# Top.net
KiCad netlist of a schematic drawn in Altium Designer
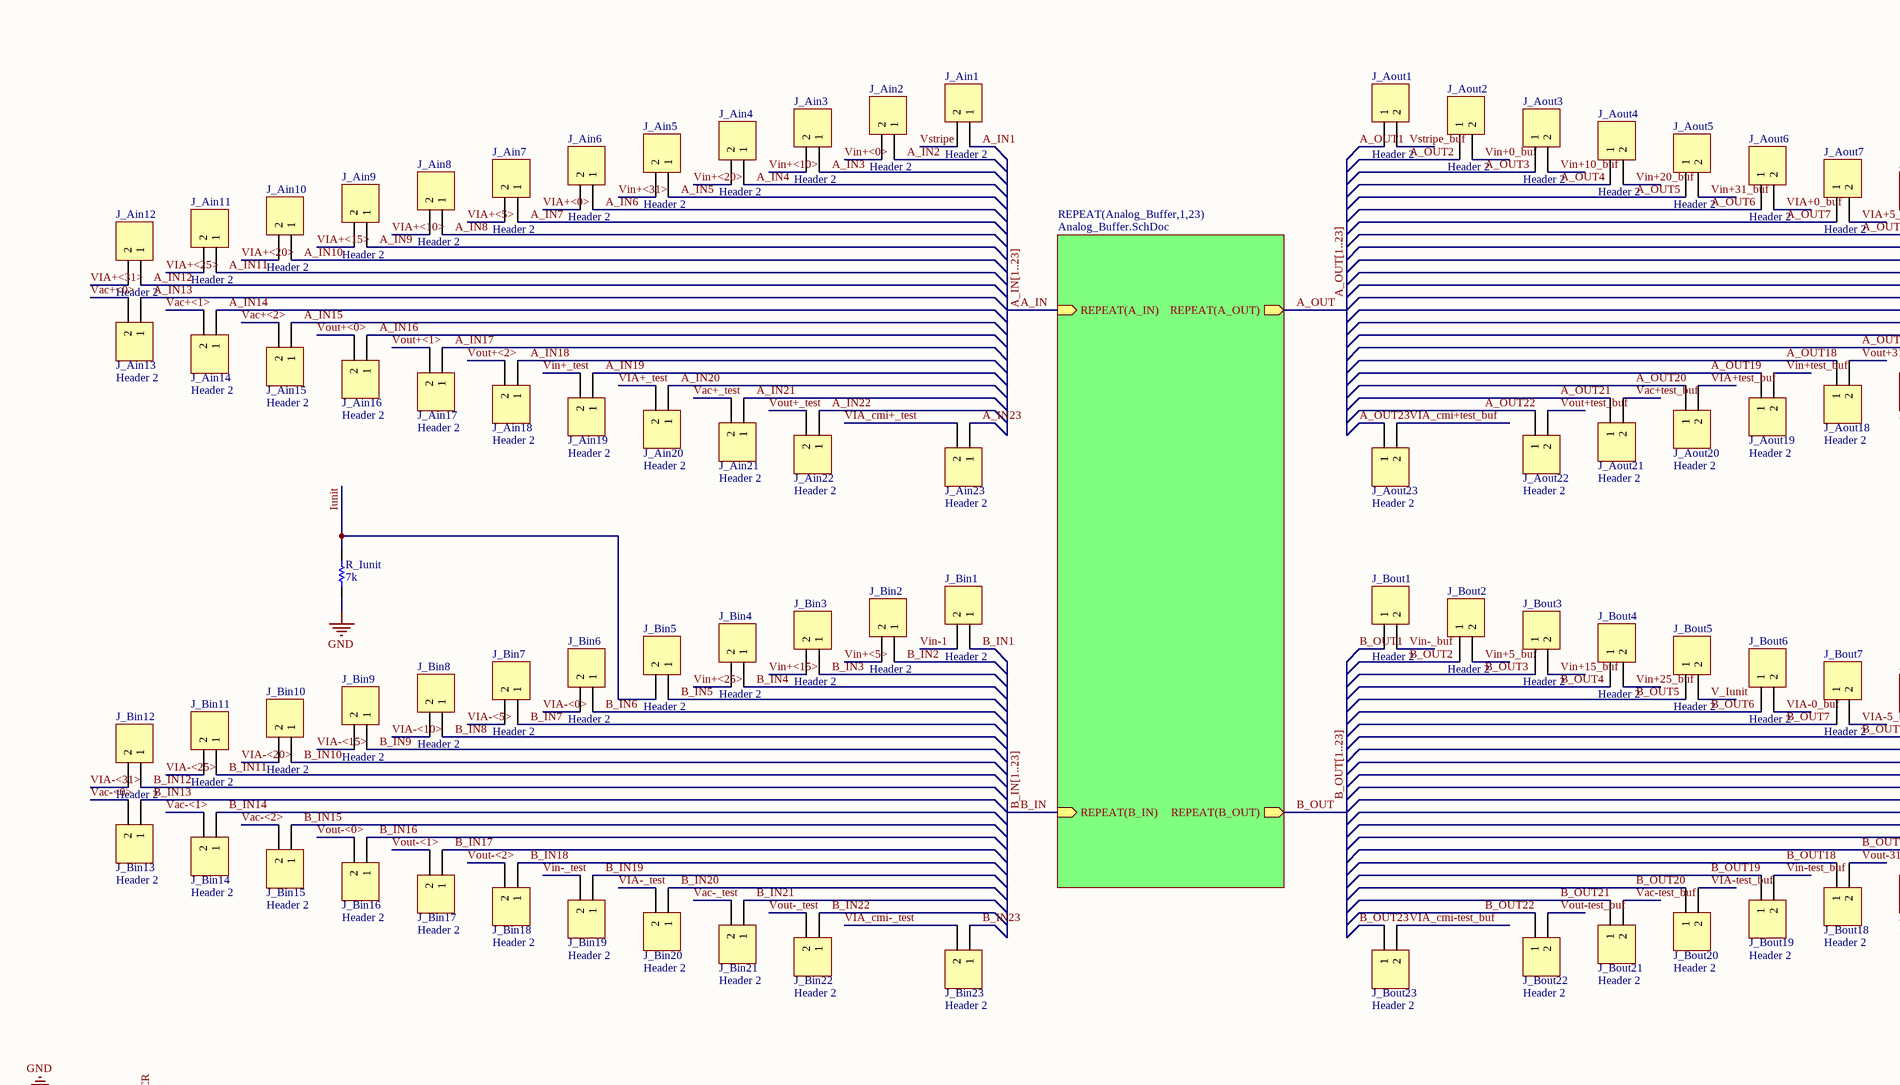
[diagram p0: Top.SchDoc, top left]
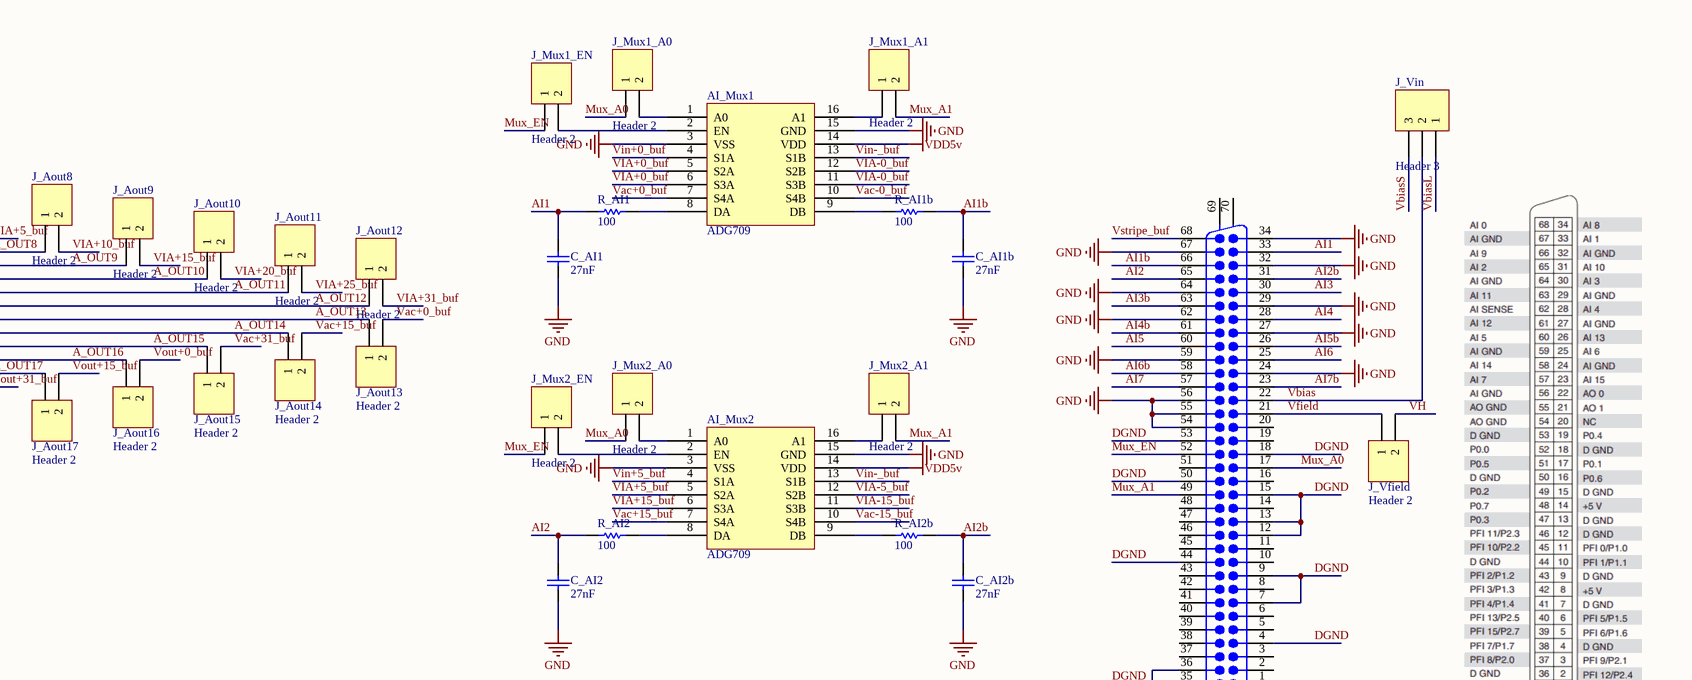
[diagram p1: Top.SchDoc, top right]
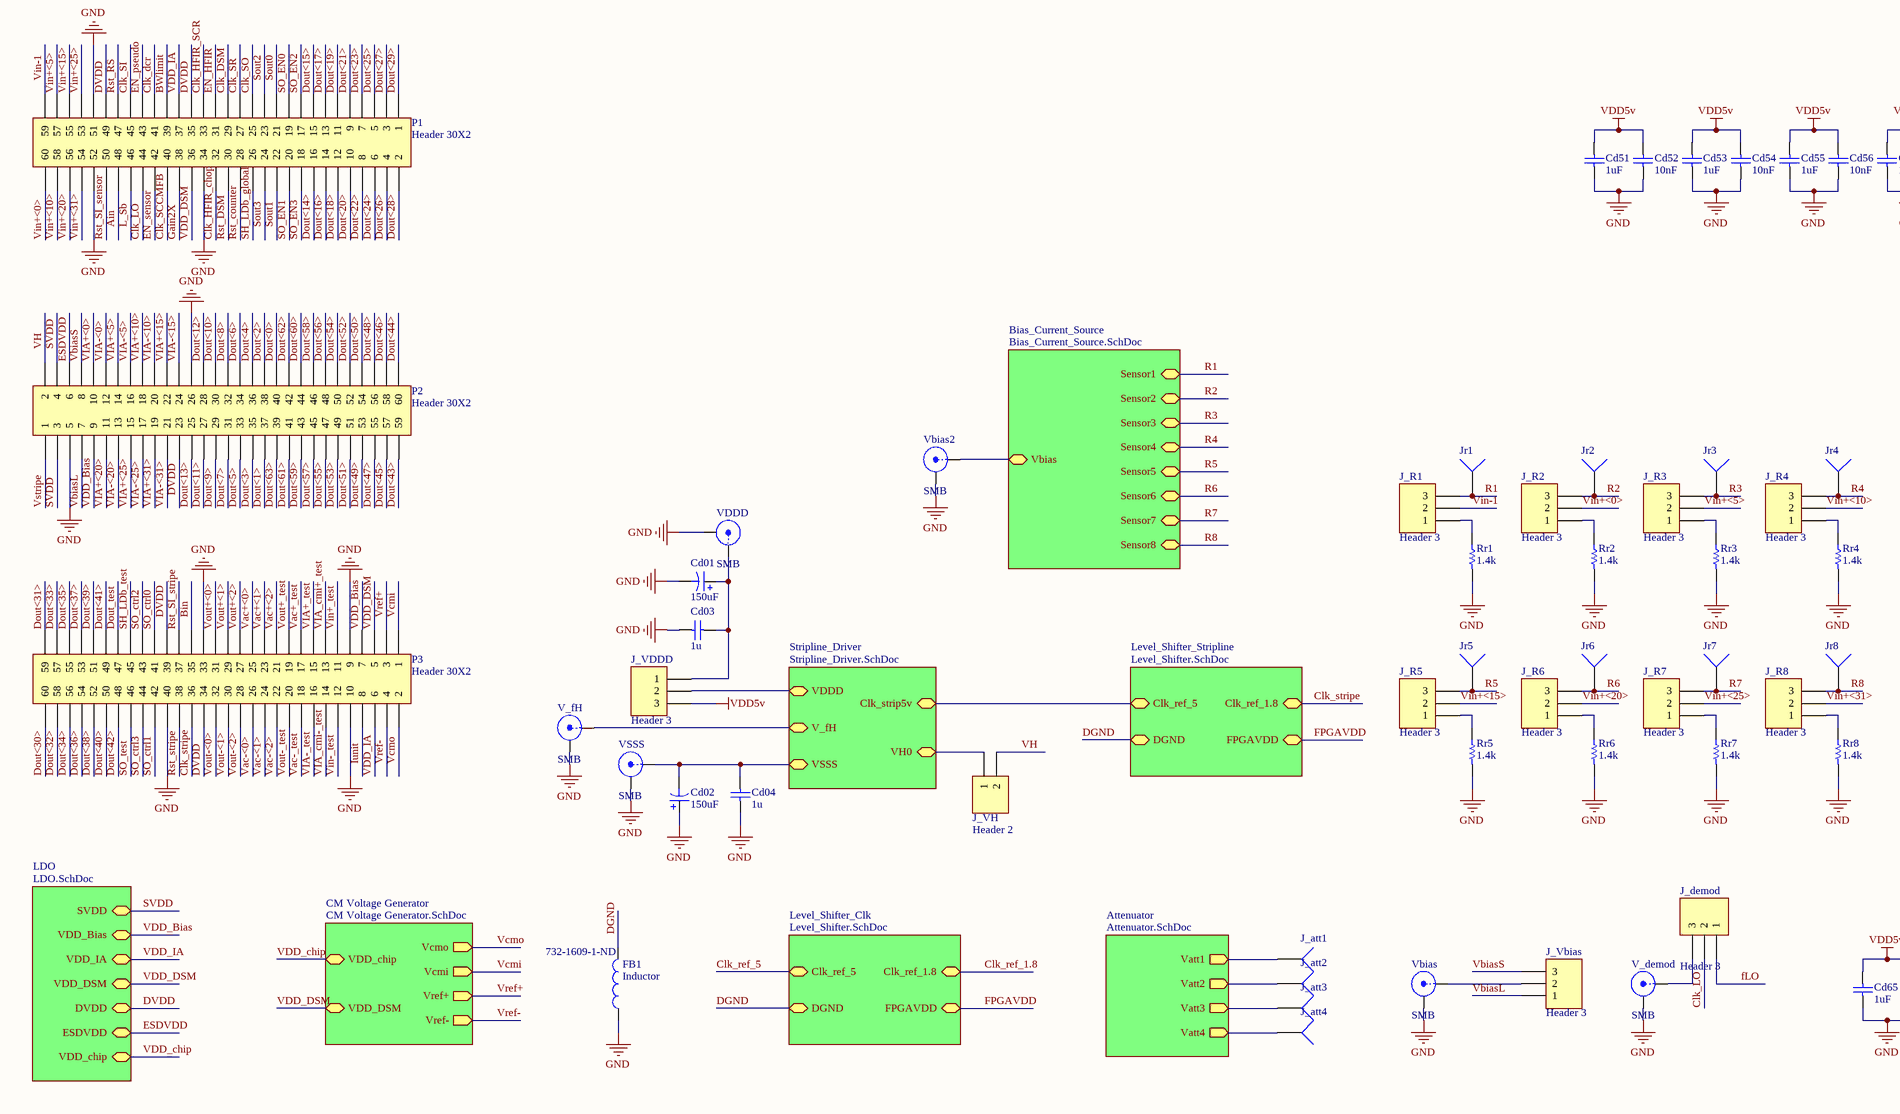
[diagram p2: Top.SchDoc, bottom left]
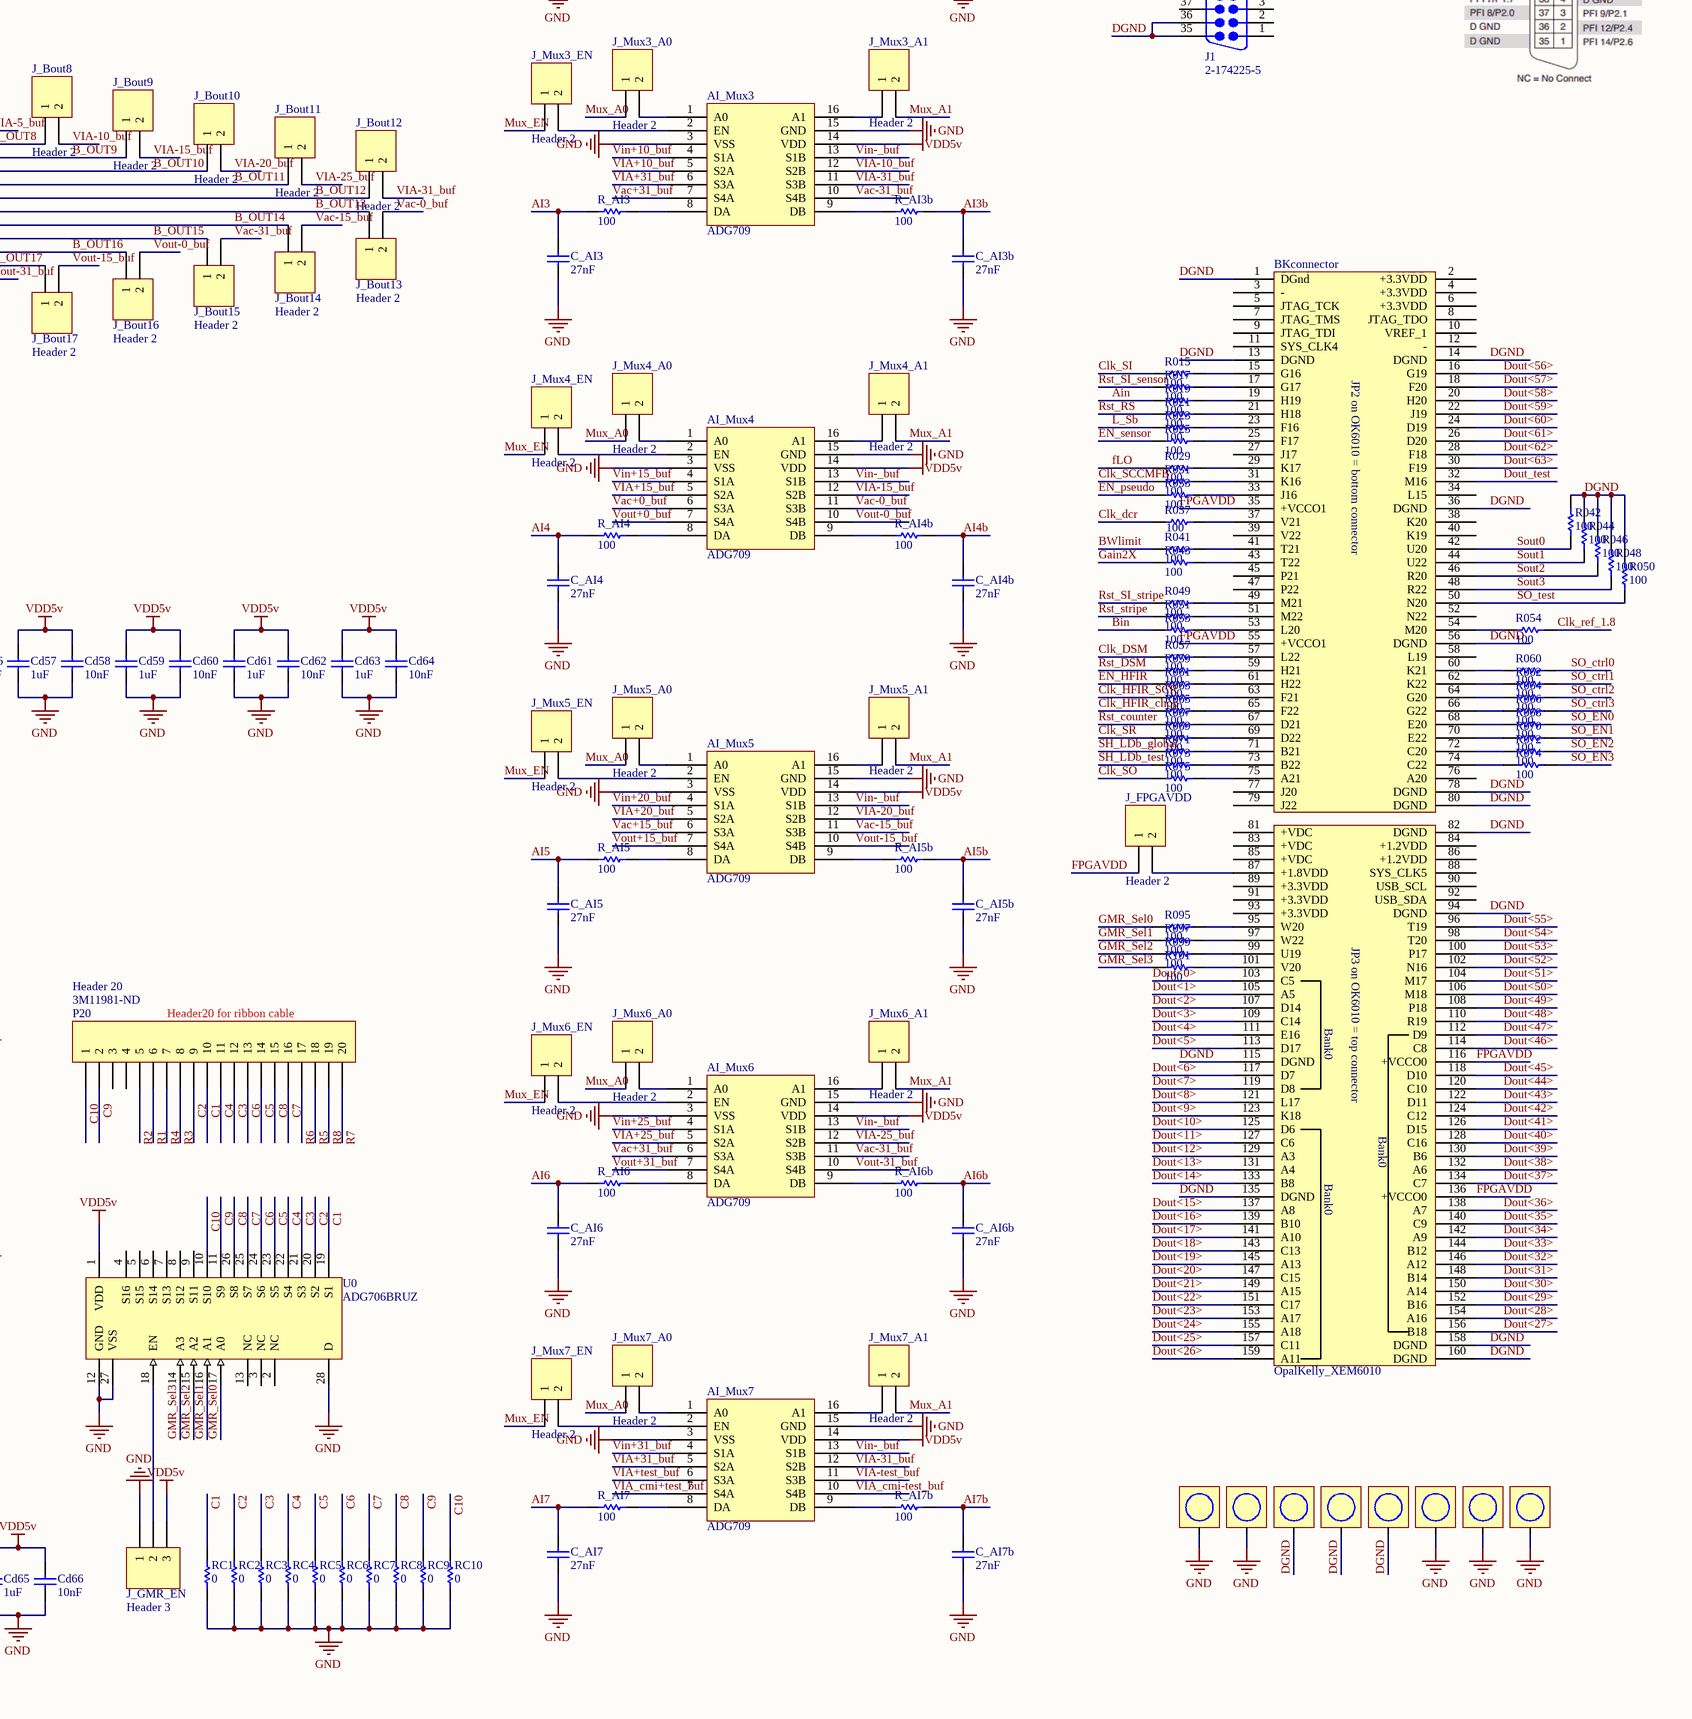
[diagram p3: Top.SchDoc, bottom right]

(export (version "E")
  (design (tool "Eeschema 10.0.6"))
  (components
    (comp (ref "AI_Mux1") (value "ADG709") (footprint "RU-16") (libsource (lib "custom") (part "ADG709")))
    (comp (ref "AI_Mux2") (value "ADG709") (footprint "RU-16") (libsource (lib "custom") (part "ADG709")))
    (comp (ref "AI_Mux3") (value "ADG709") (footprint "RU-16") (libsource (lib "custom") (part "ADG709")))
    (comp (ref "AI_Mux4") (value "ADG709") (footprint "RU-16") (libsource (lib "custom") (part "ADG709")))
    (comp (ref "AI_Mux5") (value "ADG709") (footprint "RU-16") (libsource (lib "custom") (part "ADG709")))
    (comp (ref "AI_Mux6") (value "ADG709") (footprint "RU-16") (libsource (lib "custom") (part "ADG709")))
    (comp (ref "AI_Mux7") (value "ADG709") (footprint "RU-16") (libsource (lib "custom") (part "ADG709")))
    (comp (ref "BKconnector")
      (value "OpalKelly_XEM6010")
      (footprint "OpalKelly_XEM6010")
      (libsource (lib "IBL Parts") (part "OpalKelly_XEM6010"))
    )
    (comp (ref "Cd01")
      (value "150uF")
      (footprint "C1210_M")
      (description "Polarized Capacitor (Radial)")
      (fields (field (name "Comment") "Cap Pol1") (field (name "PUBLISHER") "Altium Limited"))
      (libsource (lib "Miscellaneous Devices") (part "Cap Pol1"))
    )
    (comp (ref "Cd02")
      (value "150uF")
      (footprint "C1210_M")
      (description "Polarized Capacitor (Radial)")
      (fields (field (name "Comment") "Cap Pol1") (field (name "PUBLISHER") "Altium Limited"))
      (libsource (lib "Miscellaneous Devices") (part "Cap Pol1"))
    )
    (comp (ref "Cd03")
      (value "1u")
      (footprint "6-0805_M")
      (description "Capacitor")
      (fields (field (name "Comment") "Cap") (field (name "PUBLISHER") "Altium Limited"))
      (libsource (lib "Miscellaneous Devices") (part "Cap"))
    )
    (comp (ref "Cd04")
      (value "1u")
      (footprint "6-0805_M")
      (description "Capacitor")
      (fields (field (name "Comment") "Cap") (field (name "PUBLISHER") "Altium Limited"))
      (libsource (lib "Miscellaneous Devices") (part "Cap"))
    )
    (comp (ref "Cd51")
      (value "1uF")
      (footprint "1608[0603]")
      (description "Capacitor")
      (fields (field (name "Comment") "Cap") (field (name "PUBLISHER") "Altium Limited"))
      (libsource (lib "Miscellaneous Devices") (part "Cap"))
    )
    (comp (ref "Cd52")
      (value "10nF")
      (footprint "1608[0603]")
      (description "Capacitor")
      (fields (field (name "Comment") "Cap") (field (name "PUBLISHER") "Altium Limited"))
      (libsource (lib "Miscellaneous Devices") (part "Cap"))
    )
    (comp (ref "Cd53")
      (value "1uF")
      (footprint "1608[0603]")
      (description "Capacitor")
      (fields (field (name "Comment") "Cap") (field (name "PUBLISHER") "Altium Limited"))
      (libsource (lib "Miscellaneous Devices") (part "Cap"))
    )
    (comp (ref "Cd54")
      (value "10nF")
      (footprint "1608[0603]")
      (description "Capacitor")
      (fields (field (name "Comment") "Cap") (field (name "PUBLISHER") "Altium Limited"))
      (libsource (lib "Miscellaneous Devices") (part "Cap"))
    )
    (comp (ref "Cd55")
      (value "1uF")
      (footprint "1608[0603]")
      (description "Capacitor")
      (fields (field (name "Comment") "Cap") (field (name "PUBLISHER") "Altium Limited"))
      (libsource (lib "Miscellaneous Devices") (part "Cap"))
    )
    (comp (ref "Cd56")
      (value "10nF")
      (footprint "1608[0603]")
      (description "Capacitor")
      (fields (field (name "Comment") "Cap") (field (name "PUBLISHER") "Altium Limited"))
      (libsource (lib "Miscellaneous Devices") (part "Cap"))
    )
    (comp (ref "Cd57")
      (value "1uF")
      (footprint "1608[0603]")
      (description "Capacitor")
      (fields (field (name "Comment") "Cap") (field (name "PUBLISHER") "Altium Limited"))
      (libsource (lib "Miscellaneous Devices") (part "Cap"))
    )
    (comp (ref "Cd58")
      (value "10nF")
      (footprint "1608[0603]")
      (description "Capacitor")
      (fields (field (name "Comment") "Cap") (field (name "PUBLISHER") "Altium Limited"))
      (libsource (lib "Miscellaneous Devices") (part "Cap"))
    )
    (comp (ref "Cd59")
      (value "1uF")
      (footprint "1608[0603]")
      (description "Capacitor")
      (fields (field (name "Comment") "Cap") (field (name "PUBLISHER") "Altium Limited"))
      (libsource (lib "Miscellaneous Devices") (part "Cap"))
    )
    (comp (ref "Cd60")
      (value "10nF")
      (footprint "1608[0603]")
      (description "Capacitor")
      (fields (field (name "Comment") "Cap") (field (name "PUBLISHER") "Altium Limited"))
      (libsource (lib "Miscellaneous Devices") (part "Cap"))
    )
    (comp (ref "Cd61")
      (value "1uF")
      (footprint "1608[0603]")
      (description "Capacitor")
      (fields (field (name "Comment") "Cap") (field (name "PUBLISHER") "Altium Limited"))
      (libsource (lib "Miscellaneous Devices") (part "Cap"))
    )
    (comp (ref "Cd62")
      (value "10nF")
      (footprint "1608[0603]")
      (description "Capacitor")
      (fields (field (name "Comment") "Cap") (field (name "PUBLISHER") "Altium Limited"))
      (libsource (lib "Miscellaneous Devices") (part "Cap"))
    )
    (comp (ref "Cd63")
      (value "1uF")
      (footprint "1608[0603]")
      (description "Capacitor")
      (fields (field (name "Comment") "Cap") (field (name "PUBLISHER") "Altium Limited"))
      (libsource (lib "Miscellaneous Devices") (part "Cap"))
    )
    (comp (ref "Cd64")
      (value "10nF")
      (footprint "1608[0603]")
      (description "Capacitor")
      (fields (field (name "Comment") "Cap") (field (name "PUBLISHER") "Altium Limited"))
      (libsource (lib "Miscellaneous Devices") (part "Cap"))
    )
    (comp (ref "Cd65")
      (value "1uF")
      (footprint "1608[0603]")
      (description "Capacitor")
      (fields (field (name "Comment") "Cap") (field (name "PUBLISHER") "Altium Limited"))
      (libsource (lib "Miscellaneous Devices") (part "Cap"))
    )
    (comp (ref "Cd66")
      (value "10nF")
      (footprint "1608[0603]")
      (description "Capacitor")
      (fields (field (name "Comment") "Cap") (field (name "PUBLISHER") "Altium Limited"))
      (libsource (lib "Miscellaneous Devices") (part "Cap"))
    )
    (comp (ref "C_AI1")
      (value "27nF")
      (footprint "1608[0603]")
      (description "Capacitor")
      (fields (field (name "Comment") "Cap") (field (name "PUBLISHER") "Altium Limited"))
      (libsource (lib "Miscellaneous Devices") (part "Cap"))
    )
    (comp (ref "C_AI1b")
      (value "27nF")
      (footprint "1608[0603]")
      (description "Capacitor")
      (fields (field (name "Comment") "Cap") (field (name "PUBLISHER") "Altium Limited"))
      (libsource (lib "Miscellaneous Devices") (part "Cap"))
    )
    (comp (ref "C_AI2")
      (value "27nF")
      (footprint "1608[0603]")
      (description "Capacitor")
      (fields (field (name "Comment") "Cap") (field (name "PUBLISHER") "Altium Limited"))
      (libsource (lib "Miscellaneous Devices") (part "Cap"))
    )
    (comp (ref "C_AI2b")
      (value "27nF")
      (footprint "1608[0603]")
      (description "Capacitor")
      (fields (field (name "Comment") "Cap") (field (name "PUBLISHER") "Altium Limited"))
      (libsource (lib "Miscellaneous Devices") (part "Cap"))
    )
    (comp (ref "C_AI3")
      (value "27nF")
      (footprint "1608[0603]")
      (description "Capacitor")
      (fields (field (name "Comment") "Cap") (field (name "PUBLISHER") "Altium Limited"))
      (libsource (lib "Miscellaneous Devices") (part "Cap"))
    )
    (comp (ref "C_AI3b")
      (value "27nF")
      (footprint "1608[0603]")
      (description "Capacitor")
      (fields (field (name "Comment") "Cap") (field (name "PUBLISHER") "Altium Limited"))
      (libsource (lib "Miscellaneous Devices") (part "Cap"))
    )
    (comp (ref "C_AI4")
      (value "27nF")
      (footprint "1608[0603]")
      (description "Capacitor")
      (fields (field (name "Comment") "Cap") (field (name "PUBLISHER") "Altium Limited"))
      (libsource (lib "Miscellaneous Devices") (part "Cap"))
    )
    (comp (ref "C_AI4b")
      (value "27nF")
      (footprint "1608[0603]")
      (description "Capacitor")
      (fields (field (name "Comment") "Cap") (field (name "PUBLISHER") "Altium Limited"))
      (libsource (lib "Miscellaneous Devices") (part "Cap"))
    )
    (comp (ref "C_AI5")
      (value "27nF")
      (footprint "1608[0603]")
      (description "Capacitor")
      (fields (field (name "Comment") "Cap") (field (name "PUBLISHER") "Altium Limited"))
      (libsource (lib "Miscellaneous Devices") (part "Cap"))
    )
    (comp (ref "C_AI5b")
      (value "27nF")
      (footprint "1608[0603]")
      (description "Capacitor")
      (fields (field (name "Comment") "Cap") (field (name "PUBLISHER") "Altium Limited"))
      (libsource (lib "Miscellaneous Devices") (part "Cap"))
    )
    (comp (ref "C_AI6")
      (value "27nF")
      (footprint "1608[0603]")
      (description "Capacitor")
      (fields (field (name "Comment") "Cap") (field (name "PUBLISHER") "Altium Limited"))
      (libsource (lib "Miscellaneous Devices") (part "Cap"))
    )
    (comp (ref "C_AI6b")
      (value "27nF")
      (footprint "1608[0603]")
      (description "Capacitor")
      (fields (field (name "Comment") "Cap") (field (name "PUBLISHER") "Altium Limited"))
      (libsource (lib "Miscellaneous Devices") (part "Cap"))
    )
    (comp (ref "C_AI7")
      (value "27nF")
      (footprint "1608[0603]")
      (description "Capacitor")
      (fields (field (name "Comment") "Cap") (field (name "PUBLISHER") "Altium Limited"))
      (libsource (lib "Miscellaneous Devices") (part "Cap"))
    )
    (comp (ref "C_AI7b")
      (value "27nF")
      (footprint "1608[0603]")
      (description "Capacitor")
      (fields (field (name "Comment") "Cap") (field (name "PUBLISHER") "Altium Limited"))
      (libsource (lib "Miscellaneous Devices") (part "Cap"))
    )
    (comp (ref "FB1")
      (value "Inductor")
      (footprint "C0805")
      (fields
        (field (name "SUPPLIER PART NUMBER 1") "732-1609-1-ND")
        (field (name "MANUFACTURER") "Wurth Electronics Inc")
        (field (name "MANUFACTURER PART NUMBER") "742792093")
        (field (name "PUBLISHER") "Altium Limited")
      )
      (libsource (lib "Miscellaneous Devices") (part "Inductor"))
    )
    (comp (ref "H1")
      (value "Mounting Hole")
      (footprint "MTHole")
      (libsource (lib "IBL Parts") (part "MTHole"))
    )
    (comp (ref "H2")
      (value "Mounting Hole")
      (footprint "MTHole")
      (libsource (lib "IBL Parts") (part "MTHole"))
    )
    (comp (ref "H3")
      (value "Mounting Hole")
      (footprint "MTHole")
      (libsource (lib "IBL Parts") (part "MTHole"))
    )
    (comp (ref "H4")
      (value "Mounting Hole")
      (footprint "MTHole")
      (libsource (lib "IBL Parts") (part "MTHole"))
    )
    (comp (ref "H5")
      (value "Mounting Hole")
      (footprint "MTHole")
      (libsource (lib "IBL Parts") (part "MTHole"))
    )
    (comp (ref "H6")
      (value "Mounting Hole")
      (footprint "MTHole")
      (libsource (lib "IBL Parts") (part "MTHole"))
    )
    (comp (ref "H7")
      (value "Mounting Hole")
      (footprint "MTHole")
      (libsource (lib "IBL Parts") (part "MTHole"))
    )
    (comp (ref "H8")
      (value "Mounting Hole")
      (footprint "MTHole")
      (libsource (lib "IBL Parts") (part "MTHole"))
    )
    (comp (ref "J1")
      (value "2-174225-5")
      (footprint "2-174225-5")
      (description "Cap Header, Right Angle /M2.5 AMPLIMITE 050 Series II")
      (fields (field (name "PUBLISHER") "Altium Limited"))
      (libsource (lib "AMP D Subminiature 050 Series") (part "2-174225-5"))
    )
    (comp (ref "Jr1")
      (value "Socket")
      (footprint "PIN1")
      (fields (field (name "PUBLISHER") "Altium Limited"))
      (libsource (lib "Miscellaneous Connectors") (part "Socket"))
    )
    (comp (ref "Jr2")
      (value "Socket")
      (footprint "PIN1")
      (fields (field (name "PUBLISHER") "Altium Limited"))
      (libsource (lib "Miscellaneous Connectors") (part "Socket"))
    )
    (comp (ref "Jr3")
      (value "Socket")
      (footprint "PIN1")
      (fields (field (name "PUBLISHER") "Altium Limited"))
      (libsource (lib "Miscellaneous Connectors") (part "Socket"))
    )
    (comp (ref "Jr4")
      (value "Socket")
      (footprint "PIN1")
      (fields (field (name "PUBLISHER") "Altium Limited"))
      (libsource (lib "Miscellaneous Connectors") (part "Socket"))
    )
    (comp (ref "Jr5")
      (value "Socket")
      (footprint "PIN1")
      (fields (field (name "PUBLISHER") "Altium Limited"))
      (libsource (lib "Miscellaneous Connectors") (part "Socket"))
    )
    (comp (ref "Jr6")
      (value "Socket")
      (footprint "PIN1")
      (fields (field (name "PUBLISHER") "Altium Limited"))
      (libsource (lib "Miscellaneous Connectors") (part "Socket"))
    )
    (comp (ref "Jr7")
      (value "Socket")
      (footprint "PIN1")
      (fields (field (name "PUBLISHER") "Altium Limited"))
      (libsource (lib "Miscellaneous Connectors") (part "Socket"))
    )
    (comp (ref "Jr8")
      (value "Socket")
      (footprint "PIN1")
      (fields (field (name "PUBLISHER") "Altium Limited"))
      (libsource (lib "Miscellaneous Connectors") (part "Socket"))
    )
    (comp (ref "J_Ain1")
      (value "Header 2")
      (footprint "HDR1X2")
      (description "Header, 2-Pin")
      (fields (field (name "PUBLISHER") "Altium Limited"))
      (libsource (lib "") (part "Header 2_2"))
    )
    (comp (ref "J_Ain2")
      (value "Header 2")
      (footprint "HDR1X2")
      (description "Header, 2-Pin")
      (fields (field (name "PUBLISHER") "Altium Limited"))
      (libsource (lib "") (part "Header 2_2"))
    )
    (comp (ref "J_Ain3")
      (value "Header 2")
      (footprint "HDR1X2")
      (description "Header, 2-Pin")
      (fields (field (name "PUBLISHER") "Altium Limited"))
      (libsource (lib "") (part "Header 2_2"))
    )
    (comp (ref "J_Ain4")
      (value "Header 2")
      (footprint "HDR1X2")
      (description "Header, 2-Pin")
      (fields (field (name "PUBLISHER") "Altium Limited"))
      (libsource (lib "") (part "Header 2_2"))
    )
    (comp (ref "J_Ain5")
      (value "Header 2")
      (footprint "HDR1X2")
      (description "Header, 2-Pin")
      (fields (field (name "PUBLISHER") "Altium Limited"))
      (libsource (lib "") (part "Header 2_2"))
    )
    (comp (ref "J_Ain6")
      (value "Header 2")
      (footprint "HDR1X2")
      (description "Header, 2-Pin")
      (fields (field (name "PUBLISHER") "Altium Limited"))
      (libsource (lib "") (part "Header 2_2"))
    )
    (comp (ref "J_Ain7")
      (value "Header 2")
      (footprint "HDR1X2")
      (description "Header, 2-Pin")
      (fields (field (name "PUBLISHER") "Altium Limited"))
      (libsource (lib "") (part "Header 2_2"))
    )
    (comp (ref "J_Ain8")
      (value "Header 2")
      (footprint "HDR1X2")
      (description "Header, 2-Pin")
      (fields (field (name "PUBLISHER") "Altium Limited"))
      (libsource (lib "") (part "Header 2_2"))
    )
    (comp (ref "J_Ain9")
      (value "Header 2")
      (footprint "HDR1X2")
      (description "Header, 2-Pin")
      (fields (field (name "PUBLISHER") "Altium Limited"))
      (libsource (lib "") (part "Header 2_2"))
    )
    (comp (ref "J_Ain10")
      (value "Header 2")
      (footprint "HDR1X2")
      (description "Header, 2-Pin")
      (fields (field (name "PUBLISHER") "Altium Limited"))
      (libsource (lib "") (part "Header 2_2"))
    )
    (comp (ref "J_Ain11")
      (value "Header 2")
      (footprint "HDR1X2")
      (description "Header, 2-Pin")
      (fields (field (name "PUBLISHER") "Altium Limited"))
      (libsource (lib "") (part "Header 2_2"))
    )
    (comp (ref "J_Ain12")
      (value "Header 2")
      (footprint "HDR1X2")
      (description "Header, 2-Pin")
      (fields (field (name "PUBLISHER") "Altium Limited"))
      (libsource (lib "") (part "Header 2_2"))
    )
    (comp (ref "J_Ain13")
      (value "Header 2")
      (footprint "HDR1X2")
      (description "Header, 2-Pin")
      (fields (field (name "PUBLISHER") "Altium Limited"))
      (libsource (lib "") (part "Header 2_1"))
    )
    (comp (ref "J_Ain14")
      (value "Header 2")
      (footprint "HDR1X2")
      (description "Header, 2-Pin")
      (fields (field (name "PUBLISHER") "Altium Limited"))
      (libsource (lib "") (part "Header 2_1"))
    )
    (comp (ref "J_Ain15")
      (value "Header 2")
      (footprint "HDR1X2")
      (description "Header, 2-Pin")
      (fields (field (name "PUBLISHER") "Altium Limited"))
      (libsource (lib "") (part "Header 2_1"))
    )
    (comp (ref "J_Ain16")
      (value "Header 2")
      (footprint "HDR1X2")
      (description "Header, 2-Pin")
      (fields (field (name "PUBLISHER") "Altium Limited"))
      (libsource (lib "") (part "Header 2_1"))
    )
    (comp (ref "J_Ain17")
      (value "Header 2")
      (footprint "HDR1X2")
      (description "Header, 2-Pin")
      (fields (field (name "PUBLISHER") "Altium Limited"))
      (libsource (lib "") (part "Header 2_1"))
    )
    (comp (ref "J_Ain18")
      (value "Header 2")
      (footprint "HDR1X2")
      (description "Header, 2-Pin")
      (fields (field (name "PUBLISHER") "Altium Limited"))
      (libsource (lib "") (part "Header 2_1"))
    )
    (comp (ref "J_Ain19")
      (value "Header 2")
      (footprint "HDR1X2")
      (description "Header, 2-Pin")
      (fields (field (name "PUBLISHER") "Altium Limited"))
      (libsource (lib "") (part "Header 2_1"))
    )
    (comp (ref "J_Ain20")
      (value "Header 2")
      (footprint "HDR1X2")
      (description "Header, 2-Pin")
      (fields (field (name "PUBLISHER") "Altium Limited"))
      (libsource (lib "") (part "Header 2_1"))
    )
    (comp (ref "J_Ain21")
      (value "Header 2")
      (footprint "HDR1X2")
      (description "Header, 2-Pin")
      (fields (field (name "PUBLISHER") "Altium Limited"))
      (libsource (lib "") (part "Header 2_1"))
    )
    (comp (ref "J_Ain22")
      (value "Header 2")
      (footprint "HDR1X2")
      (description "Header, 2-Pin")
      (fields (field (name "PUBLISHER") "Altium Limited"))
      (libsource (lib "") (part "Header 2_1"))
    )
    (comp (ref "J_Ain23")
      (value "Header 2")
      (footprint "HDR1X2")
      (description "Header, 2-Pin")
      (fields (field (name "PUBLISHER") "Altium Limited"))
      (libsource (lib "") (part "Header 2_1"))
    )
    (comp (ref "J_Aout1")
      (value "Header 2")
      (footprint "HDR1X2")
      (description "Header, 2-Pin")
      (fields (field (name "PUBLISHER") "Altium Limited"))
      (libsource (lib "Miscellaneous Connectors") (part "Header 2"))
    )
    (comp (ref "J_Aout2")
      (value "Header 2")
      (footprint "HDR1X2")
      (description "Header, 2-Pin")
      (fields (field (name "PUBLISHER") "Altium Limited"))
      (libsource (lib "Miscellaneous Connectors") (part "Header 2"))
    )
    (comp (ref "J_Aout3")
      (value "Header 2")
      (footprint "HDR1X2")
      (description "Header, 2-Pin")
      (fields (field (name "PUBLISHER") "Altium Limited"))
      (libsource (lib "Miscellaneous Connectors") (part "Header 2"))
    )
    (comp (ref "J_Aout4")
      (value "Header 2")
      (footprint "HDR1X2")
      (description "Header, 2-Pin")
      (fields (field (name "PUBLISHER") "Altium Limited"))
      (libsource (lib "Miscellaneous Connectors") (part "Header 2"))
    )
    (comp (ref "J_Aout5")
      (value "Header 2")
      (footprint "HDR1X2")
      (description "Header, 2-Pin")
      (fields (field (name "PUBLISHER") "Altium Limited"))
      (libsource (lib "Miscellaneous Connectors") (part "Header 2"))
    )
    (comp (ref "J_Aout6")
      (value "Header 2")
      (footprint "HDR1X2")
      (description "Header, 2-Pin")
      (fields (field (name "PUBLISHER") "Altium Limited"))
      (libsource (lib "Miscellaneous Connectors") (part "Header 2"))
    )
    (comp (ref "J_Aout7")
      (value "Header 2")
      (footprint "HDR1X2")
      (description "Header, 2-Pin")
      (fields (field (name "PUBLISHER") "Altium Limited"))
      (libsource (lib "Miscellaneous Connectors") (part "Header 2"))
    )
    (comp (ref "J_Aout8")
      (value "Header 2")
      (footprint "HDR1X2")
      (description "Header, 2-Pin")
      (fields (field (name "PUBLISHER") "Altium Limited"))
      (libsource (lib "Miscellaneous Connectors") (part "Header 2"))
    )
    (comp (ref "J_Aout9")
      (value "Header 2")
      (footprint "HDR1X2")
      (description "Header, 2-Pin")
      (fields (field (name "PUBLISHER") "Altium Limited"))
      (libsource (lib "Miscellaneous Connectors") (part "Header 2"))
    )
    (comp (ref "J_Aout10")
      (value "Header 2")
      (footprint "HDR1X2")
      (description "Header, 2-Pin")
      (fields (field (name "PUBLISHER") "Altium Limited"))
      (libsource (lib "Miscellaneous Connectors") (part "Header 2"))
    )
    (comp (ref "J_Aout11")
      (value "Header 2")
      (footprint "HDR1X2")
      (description "Header, 2-Pin")
      (fields (field (name "PUBLISHER") "Altium Limited"))
      (libsource (lib "Miscellaneous Connectors") (part "Header 2"))
    )
    (comp (ref "J_Aout12")
      (value "Header 2")
      (footprint "HDR1X2")
      (description "Header, 2-Pin")
      (fields (field (name "PUBLISHER") "Altium Limited"))
      (libsource (lib "Miscellaneous Connectors") (part "Header 2"))
    )
    (comp (ref "J_Aout13")
      (value "Header 2")
      (footprint "HDR1X2")
      (description "Header, 2-Pin")
      (fields (field (name "PUBLISHER") "Altium Limited"))
      (libsource (lib "") (part "Header 2_3"))
    )
    (comp (ref "J_Aout14")
      (value "Header 2")
      (footprint "HDR1X2")
      (description "Header, 2-Pin")
      (fields (field (name "PUBLISHER") "Altium Limited"))
      (libsource (lib "") (part "Header 2_3"))
    )
    (comp (ref "J_Aout15")
      (value "Header 2")
      (footprint "HDR1X2")
      (description "Header, 2-Pin")
      (fields (field (name "PUBLISHER") "Altium Limited"))
      (libsource (lib "") (part "Header 2_3"))
    )
    (comp (ref "J_Aout16")
      (value "Header 2")
      (footprint "HDR1X2")
      (description "Header, 2-Pin")
      (fields (field (name "PUBLISHER") "Altium Limited"))
      (libsource (lib "") (part "Header 2_3"))
    )
    (comp (ref "J_Aout17")
      (value "Header 2")
      (footprint "HDR1X2")
      (description "Header, 2-Pin")
      (fields (field (name "PUBLISHER") "Altium Limited"))
      (libsource (lib "") (part "Header 2_3"))
    )
    (comp (ref "J_Aout18")
      (value "Header 2")
      (footprint "HDR1X2")
      (description "Header, 2-Pin")
      (fields (field (name "PUBLISHER") "Altium Limited"))
      (libsource (lib "") (part "Header 2_3"))
    )
    (comp (ref "J_Aout19")
      (value "Header 2")
      (footprint "HDR1X2")
      (description "Header, 2-Pin")
      (fields (field (name "PUBLISHER") "Altium Limited"))
      (libsource (lib "") (part "Header 2_3"))
    )
    (comp (ref "J_Aout20")
      (value "Header 2")
      (footprint "HDR1X2")
      (description "Header, 2-Pin")
      (fields (field (name "PUBLISHER") "Altium Limited"))
      (libsource (lib "") (part "Header 2_3"))
    )
    (comp (ref "J_Aout21")
      (value "Header 2")
      (footprint "HDR1X2")
      (description "Header, 2-Pin")
      (fields (field (name "PUBLISHER") "Altium Limited"))
      (libsource (lib "") (part "Header 2_3"))
    )
    (comp (ref "J_Aout22")
      (value "Header 2")
      (footprint "HDR1X2")
      (description "Header, 2-Pin")
      (fields (field (name "PUBLISHER") "Altium Limited"))
      (libsource (lib "") (part "Header 2_3"))
    )
    (comp (ref "J_Aout23")
      (value "Header 2")
      (footprint "HDR1X2")
      (description "Header, 2-Pin")
      (fields (field (name "PUBLISHER") "Altium Limited"))
      (libsource (lib "") (part "Header 2_3"))
    )
    (comp (ref "J_att1")
      (value "Socket")
      (footprint "PIN1")
      (fields (field (name "PUBLISHER") "Altium Limited"))
      (libsource (lib "Miscellaneous Connectors") (part "Socket"))
    )
    (comp (ref "J_att2")
      (value "Socket")
      (footprint "PIN1")
      (fields (field (name "PUBLISHER") "Altium Limited"))
      (libsource (lib "Miscellaneous Connectors") (part "Socket"))
    )
    (comp (ref "J_att3")
      (value "Socket")
      (footprint "PIN1")
      (fields (field (name "PUBLISHER") "Altium Limited"))
      (libsource (lib "Miscellaneous Connectors") (part "Socket"))
    )
    (comp (ref "J_att4")
      (value "Socket")
      (footprint "PIN1")
      (fields (field (name "PUBLISHER") "Altium Limited"))
      (libsource (lib "Miscellaneous Connectors") (part "Socket"))
    )
    (comp (ref "J_Bin1")
      (value "Header 2")
      (footprint "HDR1X2")
      (description "Header, 2-Pin")
      (fields (field (name "PUBLISHER") "Altium Limited"))
      (libsource (lib "") (part "Header 2_2"))
    )
    (comp (ref "J_Bin2")
      (value "Header 2")
      (footprint "HDR1X2")
      (description "Header, 2-Pin")
      (fields (field (name "PUBLISHER") "Altium Limited"))
      (libsource (lib "") (part "Header 2_2"))
    )
    (comp (ref "J_Bin3")
      (value "Header 2")
      (footprint "HDR1X2")
      (description "Header, 2-Pin")
      (fields (field (name "PUBLISHER") "Altium Limited"))
      (libsource (lib "") (part "Header 2_2"))
    )
    (comp (ref "J_Bin4")
      (value "Header 2")
      (footprint "HDR1X2")
      (description "Header, 2-Pin")
      (fields (field (name "PUBLISHER") "Altium Limited"))
      (libsource (lib "") (part "Header 2_2"))
    )
    (comp (ref "J_Bin5")
      (value "Header 2")
      (footprint "HDR1X2")
      (description "Header, 2-Pin")
      (fields (field (name "PUBLISHER") "Altium Limited"))
      (libsource (lib "") (part "Header 2_2"))
    )
    (comp (ref "J_Bin6")
      (value "Header 2")
      (footprint "HDR1X2")
      (description "Header, 2-Pin")
      (fields (field (name "PUBLISHER") "Altium Limited"))
      (libsource (lib "") (part "Header 2_2"))
    )
    (comp (ref "J_Bin7")
      (value "Header 2")
      (footprint "HDR1X2")
      (description "Header, 2-Pin")
      (fields (field (name "PUBLISHER") "Altium Limited"))
      (libsource (lib "") (part "Header 2_2"))
    )
    (comp (ref "J_Bin8")
      (value "Header 2")
      (footprint "HDR1X2")
      (description "Header, 2-Pin")
      (fields (field (name "PUBLISHER") "Altium Limited"))
      (libsource (lib "") (part "Header 2_2"))
    )
    (comp (ref "J_Bin9")
      (value "Header 2")
      (footprint "HDR1X2")
      (description "Header, 2-Pin")
      (fields (field (name "PUBLISHER") "Altium Limited"))
      (libsource (lib "") (part "Header 2_2"))
    )
    (comp (ref "J_Bin10")
      (value "Header 2")
      (footprint "HDR1X2")
      (description "Header, 2-Pin")
      (fields (field (name "PUBLISHER") "Altium Limited"))
      (libsource (lib "") (part "Header 2_2"))
    )
    (comp (ref "J_Bin11")
      (value "Header 2")
      (footprint "HDR1X2")
      (description "Header, 2-Pin")
      (fields (field (name "PUBLISHER") "Altium Limited"))
      (libsource (lib "") (part "Header 2_2"))
    )
    (comp (ref "J_Bin12")
      (value "Header 2")
      (footprint "HDR1X2")
      (description "Header, 2-Pin")
      (fields (field (name "PUBLISHER") "Altium Limited"))
      (libsource (lib "") (part "Header 2_2"))
    )
    (comp (ref "J_Bin13")
      (value "Header 2")
      (footprint "HDR1X2")
      (description "Header, 2-Pin")
      (fields (field (name "PUBLISHER") "Altium Limited"))
      (libsource (lib "") (part "Header 2_1"))
    )
    (comp (ref "J_Bin14")
      (value "Header 2")
      (footprint "HDR1X2")
      (description "Header, 2-Pin")
      (fields (field (name "PUBLISHER") "Altium Limited"))
      (libsource (lib "") (part "Header 2_1"))
    )
    (comp (ref "J_Bin15")
      (value "Header 2")
      (footprint "HDR1X2")
      (description "Header, 2-Pin")
      (fields (field (name "PUBLISHER") "Altium Limited"))
      (libsource (lib "") (part "Header 2_1"))
    )
    (comp (ref "J_Bin16")
      (value "Header 2")
      (footprint "HDR1X2")
      (description "Header, 2-Pin")
      (fields (field (name "PUBLISHER") "Altium Limited"))
      (libsource (lib "") (part "Header 2_1"))
    )
    (comp (ref "J_Bin17")
      (value "Header 2")
      (footprint "HDR1X2")
      (description "Header, 2-Pin")
      (fields (field (name "PUBLISHER") "Altium Limited"))
      (libsource (lib "") (part "Header 2_1"))
    )
    (comp (ref "J_Bin18")
      (value "Header 2")
      (footprint "HDR1X2")
      (description "Header, 2-Pin")
      (fields (field (name "PUBLISHER") "Altium Limited"))
      (libsource (lib "") (part "Header 2_1"))
    )
    (comp (ref "J_Bin19")
      (value "Header 2")
      (footprint "HDR1X2")
      (description "Header, 2-Pin")
      (fields (field (name "PUBLISHER") "Altium Limited"))
      (libsource (lib "") (part "Header 2_1"))
    )
    (comp (ref "J_Bin20")
      (value "Header 2")
      (footprint "HDR1X2")
      (description "Header, 2-Pin")
      (fields (field (name "PUBLISHER") "Altium Limited"))
      (libsource (lib "") (part "Header 2_1"))
    )
    (comp (ref "J_Bin21")
      (value "Header 2")
      (footprint "HDR1X2")
      (description "Header, 2-Pin")
      (fields (field (name "PUBLISHER") "Altium Limited"))
      (libsource (lib "") (part "Header 2_1"))
    )
    (comp (ref "J_Bin22")
      (value "Header 2")
      (footprint "HDR1X2")
      (description "Header, 2-Pin")
      (fields (field (name "PUBLISHER") "Altium Limited"))
      (libsource (lib "") (part "Header 2_1"))
    )
    (comp (ref "J_Bin23")
      (value "Header 2")
      (footprint "HDR1X2")
      (description "Header, 2-Pin")
      (fields (field (name "PUBLISHER") "Altium Limited"))
      (libsource (lib "") (part "Header 2_1"))
    )
    (comp (ref "J_Bout1")
      (value "Header 2")
      (footprint "HDR1X2")
      (description "Header, 2-Pin")
      (fields (field (name "PUBLISHER") "Altium Limited"))
      (libsource (lib "Miscellaneous Connectors") (part "Header 2"))
    )
    (comp (ref "J_Bout2")
      (value "Header 2")
      (footprint "HDR1X2")
      (description "Header, 2-Pin")
      (fields (field (name "PUBLISHER") "Altium Limited"))
      (libsource (lib "Miscellaneous Connectors") (part "Header 2"))
    )
    (comp (ref "J_Bout3")
      (value "Header 2")
      (footprint "HDR1X2")
      (description "Header, 2-Pin")
      (fields (field (name "PUBLISHER") "Altium Limited"))
      (libsource (lib "Miscellaneous Connectors") (part "Header 2"))
    )
    (comp (ref "J_Bout4")
      (value "Header 2")
      (footprint "HDR1X2")
      (description "Header, 2-Pin")
      (fields (field (name "PUBLISHER") "Altium Limited"))
      (libsource (lib "Miscellaneous Connectors") (part "Header 2"))
    )
    (comp (ref "J_Bout5")
      (value "Header 2")
      (footprint "HDR1X2")
      (description "Header, 2-Pin")
      (fields (field (name "PUBLISHER") "Altium Limited"))
      (libsource (lib "Miscellaneous Connectors") (part "Header 2"))
    )
    (comp (ref "J_Bout6")
      (value "Header 2")
      (footprint "HDR1X2")
      (description "Header, 2-Pin")
      (fields (field (name "PUBLISHER") "Altium Limited"))
      (libsource (lib "Miscellaneous Connectors") (part "Header 2"))
    )
    (comp (ref "J_Bout7")
      (value "Header 2")
      (footprint "HDR1X2")
      (description "Header, 2-Pin")
      (fields (field (name "PUBLISHER") "Altium Limited"))
      (libsource (lib "Miscellaneous Connectors") (part "Header 2"))
    )
    (comp (ref "J_Bout8")
      (value "Header 2")
      (footprint "HDR1X2")
      (description "Header, 2-Pin")
      (fields (field (name "PUBLISHER") "Altium Limited"))
      (libsource (lib "Miscellaneous Connectors") (part "Header 2"))
    )
    (comp (ref "J_Bout9")
      (value "Header 2")
      (footprint "HDR1X2")
      (description "Header, 2-Pin")
      (fields (field (name "PUBLISHER") "Altium Limited"))
      (libsource (lib "Miscellaneous Connectors") (part "Header 2"))
    )
    (comp (ref "J_Bout10")
      (value "Header 2")
      (footprint "HDR1X2")
      (description "Header, 2-Pin")
      (fields (field (name "PUBLISHER") "Altium Limited"))
      (libsource (lib "Miscellaneous Connectors") (part "Header 2"))
    )
    (comp (ref "J_Bout11")
      (value "Header 2")
      (footprint "HDR1X2")
      (description "Header, 2-Pin")
      (fields (field (name "PUBLISHER") "Altium Limited"))
      (libsource (lib "Miscellaneous Connectors") (part "Header 2"))
    )
    (comp (ref "J_Bout12")
      (value "Header 2")
      (footprint "HDR1X2")
      (description "Header, 2-Pin")
      (fields (field (name "PUBLISHER") "Altium Limited"))
      (libsource (lib "Miscellaneous Connectors") (part "Header 2"))
    )
    (comp (ref "J_Bout13")
      (value "Header 2")
      (footprint "HDR1X2")
      (description "Header, 2-Pin")
      (fields (field (name "PUBLISHER") "Altium Limited"))
      (libsource (lib "") (part "Header 2_3"))
    )
    (comp (ref "J_Bout14")
      (value "Header 2")
      (footprint "HDR1X2")
      (description "Header, 2-Pin")
      (fields (field (name "PUBLISHER") "Altium Limited"))
      (libsource (lib "") (part "Header 2_3"))
    )
    (comp (ref "J_Bout15")
      (value "Header 2")
      (footprint "HDR1X2")
      (description "Header, 2-Pin")
      (fields (field (name "PUBLISHER") "Altium Limited"))
      (libsource (lib "") (part "Header 2_3"))
    )
    (comp (ref "J_Bout16")
      (value "Header 2")
      (footprint "HDR1X2")
      (description "Header, 2-Pin")
      (fields (field (name "PUBLISHER") "Altium Limited"))
      (libsource (lib "") (part "Header 2_3"))
    )
    (comp (ref "J_Bout17")
      (value "Header 2")
      (footprint "HDR1X2")
      (description "Header, 2-Pin")
      (fields (field (name "PUBLISHER") "Altium Limited"))
      (libsource (lib "") (part "Header 2_3"))
    )
    (comp (ref "J_Bout18")
      (value "Header 2")
      (footprint "HDR1X2")
      (description "Header, 2-Pin")
      (fields (field (name "PUBLISHER") "Altium Limited"))
      (libsource (lib "") (part "Header 2_3"))
    )
    (comp (ref "J_Bout19")
      (value "Header 2")
      (footprint "HDR1X2")
      (description "Header, 2-Pin")
      (fields (field (name "PUBLISHER") "Altium Limited"))
      (libsource (lib "") (part "Header 2_3"))
    )
    (comp (ref "J_Bout20")
      (value "Header 2")
      (footprint "HDR1X2")
      (description "Header, 2-Pin")
      (fields (field (name "PUBLISHER") "Altium Limited"))
      (libsource (lib "") (part "Header 2_3"))
    )
    (comp (ref "J_Bout21")
      (value "Header 2")
      (footprint "HDR1X2")
      (description "Header, 2-Pin")
      (fields (field (name "PUBLISHER") "Altium Limited"))
      (libsource (lib "") (part "Header 2_3"))
    )
    (comp (ref "J_Bout22")
      (value "Header 2")
      (footprint "HDR1X2")
      (description "Header, 2-Pin")
      (fields (field (name "PUBLISHER") "Altium Limited"))
      (libsource (lib "") (part "Header 2_3"))
    )
    (comp (ref "J_Bout23")
      (value "Header 2")
      (footprint "HDR1X2")
      (description "Header, 2-Pin")
      (fields (field (name "PUBLISHER") "Altium Limited"))
      (libsource (lib "") (part "Header 2_3"))
    )
    (comp (ref "J_demod")
      (value "Header 3")
      (footprint "HDR1X3")
      (description "Header, 3-Pin")
      (fields (field (name "PUBLISHER") "Altium Limited"))
      (libsource (lib "") (part "Header 3_3"))
    )
    (comp (ref "J_FPGAVDD")
      (value "Header 2")
      (footprint "HDR1X2")
      (description "Header, 2-Pin")
      (fields (field (name "PUBLISHER") "Altium Limited"))
      (libsource (lib "Miscellaneous Connectors") (part "Header 2"))
    )
    (comp (ref "J_GMR_EN")
      (value "Header 3")
      (footprint "HDR1X3")
      (description "Header, 3-Pin")
      (fields (field (name "PUBLISHER") "Altium Limited"))
      (libsource (lib "Miscellaneous Connectors") (part "Header 3"))
    )
    (comp (ref "J_Mux1_A0")
      (value "Header 2")
      (footprint "HDR1X2")
      (description "Header, 2-Pin")
      (fields (field (name "PUBLISHER") "Altium Limited"))
      (libsource (lib "Miscellaneous Connectors") (part "Header 2"))
    )
    (comp (ref "J_Mux1_A1")
      (value "Header 2")
      (footprint "HDR1X2")
      (description "Header, 2-Pin")
      (fields (field (name "PUBLISHER") "Altium Limited"))
      (libsource (lib "Miscellaneous Connectors") (part "Header 2"))
    )
    (comp (ref "J_Mux1_EN")
      (value "Header 2")
      (footprint "HDR1X2")
      (description "Header, 2-Pin")
      (fields (field (name "PUBLISHER") "Altium Limited"))
      (libsource (lib "Miscellaneous Connectors") (part "Header 2"))
    )
    (comp (ref "J_Mux2_A0")
      (value "Header 2")
      (footprint "HDR1X2")
      (description "Header, 2-Pin")
      (fields (field (name "PUBLISHER") "Altium Limited"))
      (libsource (lib "Miscellaneous Connectors") (part "Header 2"))
    )
    (comp (ref "J_Mux2_A1")
      (value "Header 2")
      (footprint "HDR1X2")
      (description "Header, 2-Pin")
      (fields (field (name "PUBLISHER") "Altium Limited"))
      (libsource (lib "Miscellaneous Connectors") (part "Header 2"))
    )
    (comp (ref "J_Mux2_EN")
      (value "Header 2")
      (footprint "HDR1X2")
      (description "Header, 2-Pin")
      (fields (field (name "PUBLISHER") "Altium Limited"))
      (libsource (lib "Miscellaneous Connectors") (part "Header 2"))
    )
    (comp (ref "J_Mux3_A0")
      (value "Header 2")
      (footprint "HDR1X2")
      (description "Header, 2-Pin")
      (fields (field (name "PUBLISHER") "Altium Limited"))
      (libsource (lib "Miscellaneous Connectors") (part "Header 2"))
    )
    (comp (ref "J_Mux3_A1")
      (value "Header 2")
      (footprint "HDR1X2")
      (description "Header, 2-Pin")
      (fields (field (name "PUBLISHER") "Altium Limited"))
      (libsource (lib "Miscellaneous Connectors") (part "Header 2"))
    )
    (comp (ref "J_Mux3_EN")
      (value "Header 2")
      (footprint "HDR1X2")
      (description "Header, 2-Pin")
      (fields (field (name "PUBLISHER") "Altium Limited"))
      (libsource (lib "Miscellaneous Connectors") (part "Header 2"))
    )
    (comp (ref "J_Mux4_A0")
      (value "Header 2")
      (footprint "HDR1X2")
      (description "Header, 2-Pin")
      (fields (field (name "PUBLISHER") "Altium Limited"))
      (libsource (lib "Miscellaneous Connectors") (part "Header 2"))
    )
    (comp (ref "J_Mux4_A1")
      (value "Header 2")
      (footprint "HDR1X2")
      (description "Header, 2-Pin")
      (fields (field (name "PUBLISHER") "Altium Limited"))
      (libsource (lib "Miscellaneous Connectors") (part "Header 2"))
    )
    (comp (ref "J_Mux4_EN")
      (value "Header 2")
      (footprint "HDR1X2")
      (description "Header, 2-Pin")
      (fields (field (name "PUBLISHER") "Altium Limited"))
      (libsource (lib "Miscellaneous Connectors") (part "Header 2"))
    )
    (comp (ref "J_Mux5_A0")
      (value "Header 2")
      (footprint "HDR1X2")
      (description "Header, 2-Pin")
      (fields (field (name "PUBLISHER") "Altium Limited"))
      (libsource (lib "Miscellaneous Connectors") (part "Header 2"))
    )
    (comp (ref "J_Mux5_A1")
      (value "Header 2")
      (footprint "HDR1X2")
      (description "Header, 2-Pin")
      (fields (field (name "PUBLISHER") "Altium Limited"))
      (libsource (lib "Miscellaneous Connectors") (part "Header 2"))
    )
    (comp (ref "J_Mux5_EN")
      (value "Header 2")
      (footprint "HDR1X2")
      (description "Header, 2-Pin")
      (fields (field (name "PUBLISHER") "Altium Limited"))
      (libsource (lib "Miscellaneous Connectors") (part "Header 2"))
    )
    (comp (ref "J_Mux6_A0")
      (value "Header 2")
      (footprint "HDR1X2")
      (description "Header, 2-Pin")
      (fields (field (name "PUBLISHER") "Altium Limited"))
      (libsource (lib "Miscellaneous Connectors") (part "Header 2"))
    )
    (comp (ref "J_Mux6_A1")
      (value "Header 2")
      (footprint "HDR1X2")
      (description "Header, 2-Pin")
      (fields (field (name "PUBLISHER") "Altium Limited"))
      (libsource (lib "Miscellaneous Connectors") (part "Header 2"))
    )
    (comp (ref "J_Mux6_EN")
      (value "Header 2")
      (footprint "HDR1X2")
      (description "Header, 2-Pin")
      (fields (field (name "PUBLISHER") "Altium Limited"))
      (libsource (lib "Miscellaneous Connectors") (part "Header 2"))
    )
    (comp (ref "J_Mux7_A0")
      (value "Header 2")
      (footprint "HDR1X2")
      (description "Header, 2-Pin")
      (fields (field (name "PUBLISHER") "Altium Limited"))
      (libsource (lib "Miscellaneous Connectors") (part "Header 2"))
    )
    (comp (ref "J_Mux7_A1")
      (value "Header 2")
      (footprint "HDR1X2")
      (description "Header, 2-Pin")
      (fields (field (name "PUBLISHER") "Altium Limited"))
      (libsource (lib "Miscellaneous Connectors") (part "Header 2"))
    )
    (comp (ref "J_Mux7_EN")
      (value "Header 2")
      (footprint "HDR1X2")
      (description "Header, 2-Pin")
      (fields (field (name "PUBLISHER") "Altium Limited"))
      (libsource (lib "Miscellaneous Connectors") (part "Header 2"))
    )
    (comp (ref "J_R1")
      (value "Header 3")
      (footprint "HDR1X3")
      (description "Header, 3-Pin")
      (fields (field (name "PUBLISHER") "Altium Limited"))
      (libsource (lib "Miscellaneous Connectors") (part "Header 3"))
    )
    (comp (ref "J_R2")
      (value "Header 3")
      (footprint "HDR1X3")
      (description "Header, 3-Pin")
      (fields (field (name "PUBLISHER") "Altium Limited"))
      (libsource (lib "Miscellaneous Connectors") (part "Header 3"))
    )
    (comp (ref "J_R3")
      (value "Header 3")
      (footprint "HDR1X3")
      (description "Header, 3-Pin")
      (fields (field (name "PUBLISHER") "Altium Limited"))
      (libsource (lib "Miscellaneous Connectors") (part "Header 3"))
    )
    (comp (ref "J_R4")
      (value "Header 3")
      (footprint "HDR1X3")
      (description "Header, 3-Pin")
      (fields (field (name "PUBLISHER") "Altium Limited"))
      (libsource (lib "Miscellaneous Connectors") (part "Header 3"))
    )
    (comp (ref "J_R5")
      (value "Header 3")
      (footprint "HDR1X3")
      (description "Header, 3-Pin")
      (fields (field (name "PUBLISHER") "Altium Limited"))
      (libsource (lib "Miscellaneous Connectors") (part "Header 3"))
    )
    (comp (ref "J_R6")
      (value "Header 3")
      (footprint "HDR1X3")
      (description "Header, 3-Pin")
      (fields (field (name "PUBLISHER") "Altium Limited"))
      (libsource (lib "Miscellaneous Connectors") (part "Header 3"))
    )
    (comp (ref "J_R7")
      (value "Header 3")
      (footprint "HDR1X3")
      (description "Header, 3-Pin")
      (fields (field (name "PUBLISHER") "Altium Limited"))
      (libsource (lib "Miscellaneous Connectors") (part "Header 3"))
    )
    (comp (ref "J_R8")
      (value "Header 3")
      (footprint "HDR1X3")
      (description "Header, 3-Pin")
      (fields (field (name "PUBLISHER") "Altium Limited"))
      (libsource (lib "Miscellaneous Connectors") (part "Header 3"))
    )
    (comp (ref "J_Vbias")
      (value "Header 3")
      (footprint "HDR1X3")
      (description "Header, 3-Pin")
      (fields (field (name "PUBLISHER") "Altium Limited"))
      (libsource (lib "") (part "Header 3_2"))
    )
    (comp (ref "J_VDDD")
      (value "Header 3")
      (footprint "HDR1X3")
      (description "Header, 3-Pin")
      (fields (field (name "PUBLISHER") "Altium Limited"))
      (libsource (lib "") (part "Header 3_1"))
    )
    (comp (ref "J_Vfield")
      (value "Header 2")
      (footprint "HDR1X2")
      (description "Header, 2-Pin")
      (fields (field (name "PUBLISHER") "Altium Limited"))
      (libsource (lib "") (part "Header 2_3"))
    )
    (comp (ref "J_VH")
      (value "Header 2")
      (footprint "HDR1X2")
      (description "Header, 2-Pin")
      (fields (field (name "PUBLISHER") "Altium Limited"))
      (libsource (lib "") (part "Header 2_3"))
    )
    (comp (ref "J_Vin")
      (value "Header 3")
      (footprint "HDR1X3")
      (description "Header, 3-Pin")
      (fields (field (name "PUBLISHER") "Altium Limited"))
      (libsource (lib "") (part "Header 3_3"))
    )
    (comp (ref "P1")
      (value "Header 30X2")
      (footprint "HDR2X30")
      (description "Header, 30-Pin, Dual row")
      (fields (field (name "PUBLISHER") "Altium Limited"))
      (libsource (lib "Miscellaneous Connectors") (part "Header 30X2"))
    )
    (comp (ref "P2")
      (value "Header 30X2")
      (footprint "HDR2X30")
      (description "Header, 30-Pin, Dual row")
      (fields (field (name "PUBLISHER") "Altium Limited"))
      (libsource (lib "") (part "Header 30X2_1"))
    )
    (comp (ref "P3")
      (value "Header 30X2")
      (footprint "HDR2X30")
      (description "Header, 30-Pin, Dual row")
      (fields (field (name "PUBLISHER") "Altium Limited"))
      (libsource (lib "Miscellaneous Connectors") (part "Header 30X2"))
    )
    (comp (ref "P20")
      (value "Header 20")
      (footprint "Miscellaneous Connectors:HDR2X10")
      (description "Header, 20-Pin")
      (fields
        (field (name "SUPPLIER PART NUMBER 1") "3M11981-ND")
        (field (name "MANUFACTURER") "3M")
        (field (name "MANUFACTURER PART NUMBER") "N3428-6203RB")
        (field (name "PUBLISHER") "Altium Limited")
      )
      (libsource (lib "Miscellaneous Connectors") (part "Header 20"))
    )
    (comp (ref "R015")
      (value "100")
      (footprint "1608[0603]")
      (description "Resistor")
      (fields (field (name "Comment") "Res1") (field (name "PUBLISHER") "Altium Limited"))
      (libsource (lib "Miscellaneous Devices") (part "Res1"))
    )
    (comp (ref "R017")
      (value "100")
      (footprint "1608[0603]")
      (description "Resistor")
      (fields (field (name "Comment") "Res1") (field (name "PUBLISHER") "Altium Limited"))
      (libsource (lib "Miscellaneous Devices") (part "Res1"))
    )
    (comp (ref "R019")
      (value "100")
      (footprint "1608[0603]")
      (description "Resistor")
      (fields (field (name "Comment") "Res1") (field (name "PUBLISHER") "Altium Limited"))
      (libsource (lib "Miscellaneous Devices") (part "Res1"))
    )
    (comp (ref "R021")
      (value "100")
      (footprint "1608[0603]")
      (description "Resistor")
      (fields (field (name "Comment") "Res1") (field (name "PUBLISHER") "Altium Limited"))
      (libsource (lib "Miscellaneous Devices") (part "Res1"))
    )
    (comp (ref "R023")
      (value "100")
      (footprint "1608[0603]")
      (description "Resistor")
      (fields (field (name "Comment") "Res1") (field (name "PUBLISHER") "Altium Limited"))
      (libsource (lib "Miscellaneous Devices") (part "Res1"))
    )
    (comp (ref "R025")
      (value "100")
      (footprint "1608[0603]")
      (description "Resistor")
      (fields (field (name "Comment") "Res1") (field (name "PUBLISHER") "Altium Limited"))
      (libsource (lib "Miscellaneous Devices") (part "Res1"))
    )
    (comp (ref "R029")
      (value "100")
      (footprint "1608[0603]")
      (description "Resistor")
      (fields (field (name "Comment") "Res1") (field (name "PUBLISHER") "Altium Limited"))
      (libsource (lib "Miscellaneous Devices") (part "Res1"))
    )
    (comp (ref "R031")
      (value "100")
      (footprint "1608[0603]")
      (description "Resistor")
      (fields (field (name "Comment") "Res1") (field (name "PUBLISHER") "Altium Limited"))
      (libsource (lib "Miscellaneous Devices") (part "Res1"))
    )
    (comp (ref "R033")
      (value "100")
      (footprint "1608[0603]")
      (description "Resistor")
      (fields (field (name "Comment") "Res1") (field (name "PUBLISHER") "Altium Limited"))
      (libsource (lib "Miscellaneous Devices") (part "Res1"))
    )
    (comp (ref "R037")
      (value "100")
      (footprint "1608[0603]")
      (description "Resistor")
      (fields (field (name "Comment") "Res1") (field (name "PUBLISHER") "Altium Limited"))
      (libsource (lib "Miscellaneous Devices") (part "Res1"))
    )
    (comp (ref "R041")
      (value "100")
      (footprint "1608[0603]")
      (description "Resistor")
      (fields (field (name "Comment") "Res1") (field (name "PUBLISHER") "Altium Limited"))
      (libsource (lib "Miscellaneous Devices") (part "Res1"))
    )
    (comp (ref "R042")
      (value "100")
      (footprint "1608[0603]")
      (description "Resistor")
      (fields (field (name "Comment") "Res1") (field (name "PUBLISHER") "Altium Limited"))
      (libsource (lib "Miscellaneous Devices") (part "Res1"))
    )
    (comp (ref "R043")
      (value "100")
      (footprint "1608[0603]")
      (description "Resistor")
      (fields (field (name "Comment") "Res1") (field (name "PUBLISHER") "Altium Limited"))
      (libsource (lib "Miscellaneous Devices") (part "Res1"))
    )
    (comp (ref "R044")
      (value "100")
      (footprint "1608[0603]")
      (description "Resistor")
      (fields (field (name "Comment") "Res1") (field (name "PUBLISHER") "Altium Limited"))
      (libsource (lib "Miscellaneous Devices") (part "Res1"))
    )
    (comp (ref "R046")
      (value "100")
      (footprint "1608[0603]")
      (description "Resistor")
      (fields (field (name "Comment") "Res1") (field (name "PUBLISHER") "Altium Limited"))
      (libsource (lib "Miscellaneous Devices") (part "Res1"))
    )
    (comp (ref "R048")
      (value "100")
      (footprint "1608[0603]")
      (description "Resistor")
      (fields (field (name "Comment") "Res1") (field (name "PUBLISHER") "Altium Limited"))
      (libsource (lib "Miscellaneous Devices") (part "Res1"))
    )
    (comp (ref "R049")
      (value "100")
      (footprint "1608[0603]")
      (description "Resistor")
      (fields (field (name "Comment") "Res1") (field (name "PUBLISHER") "Altium Limited"))
      (libsource (lib "Miscellaneous Devices") (part "Res1"))
    )
    (comp (ref "R050")
      (value "100")
      (footprint "1608[0603]")
      (description "Resistor")
      (fields (field (name "Comment") "Res1") (field (name "PUBLISHER") "Altium Limited"))
      (libsource (lib "Miscellaneous Devices") (part "Res1"))
    )
    (comp (ref "R051")
      (value "100")
      (footprint "1608[0603]")
      (description "Resistor")
      (fields (field (name "Comment") "Res1") (field (name "PUBLISHER") "Altium Limited"))
      (libsource (lib "Miscellaneous Devices") (part "Res1"))
    )
    (comp (ref "R053")
      (value "100")
      (footprint "1608[0603]")
      (description "Resistor")
      (fields (field (name "Comment") "Res1") (field (name "PUBLISHER") "Altium Limited"))
      (libsource (lib "Miscellaneous Devices") (part "Res1"))
    )
    (comp (ref "R054")
      (value "100")
      (footprint "1608[0603]")
      (description "Resistor")
      (fields (field (name "Comment") "Res1") (field (name "PUBLISHER") "Altium Limited"))
      (libsource (lib "Miscellaneous Devices") (part "Res1"))
    )
    (comp (ref "R057")
      (value "100")
      (footprint "1608[0603]")
      (description "Resistor")
      (fields (field (name "Comment") "Res1") (field (name "PUBLISHER") "Altium Limited"))
      (libsource (lib "Miscellaneous Devices") (part "Res1"))
    )
    (comp (ref "R059")
      (value "100")
      (footprint "1608[0603]")
      (description "Resistor")
      (fields (field (name "Comment") "Res1") (field (name "PUBLISHER") "Altium Limited"))
      (libsource (lib "Miscellaneous Devices") (part "Res1"))
    )
    (comp (ref "R060")
      (value "100")
      (footprint "1608[0603]")
      (description "Resistor")
      (fields (field (name "Comment") "Res1") (field (name "PUBLISHER") "Altium Limited"))
      (libsource (lib "Miscellaneous Devices") (part "Res1"))
    )
    (comp (ref "R061")
      (value "100")
      (footprint "1608[0603]")
      (description "Resistor")
      (fields (field (name "Comment") "Res1") (field (name "PUBLISHER") "Altium Limited"))
      (libsource (lib "Miscellaneous Devices") (part "Res1"))
    )
    (comp (ref "R062")
      (value "100")
      (footprint "1608[0603]")
      (description "Resistor")
      (fields (field (name "Comment") "Res1") (field (name "PUBLISHER") "Altium Limited"))
      (libsource (lib "Miscellaneous Devices") (part "Res1"))
    )
    (comp (ref "R063")
      (value "100")
      (footprint "1608[0603]")
      (description "Resistor")
      (fields (field (name "Comment") "Res1") (field (name "PUBLISHER") "Altium Limited"))
      (libsource (lib "Miscellaneous Devices") (part "Res1"))
    )
    (comp (ref "R064")
      (value "100")
      (footprint "1608[0603]")
      (description "Resistor")
      (fields (field (name "Comment") "Res1") (field (name "PUBLISHER") "Altium Limited"))
      (libsource (lib "Miscellaneous Devices") (part "Res1"))
    )
    (comp (ref "R065")
      (value "100")
      (footprint "1608[0603]")
      (description "Resistor")
      (fields (field (name "Comment") "Res1") (field (name "PUBLISHER") "Altium Limited"))
      (libsource (lib "Miscellaneous Devices") (part "Res1"))
    )
    (comp (ref "R066")
      (value "100")
      (footprint "1608[0603]")
      (description "Resistor")
      (fields (field (name "Comment") "Res1") (field (name "PUBLISHER") "Altium Limited"))
      (libsource (lib "Miscellaneous Devices") (part "Res1"))
    )
    (comp (ref "R067")
      (value "100")
      (footprint "1608[0603]")
      (description "Resistor")
      (fields (field (name "Comment") "Res1") (field (name "PUBLISHER") "Altium Limited"))
      (libsource (lib "Miscellaneous Devices") (part "Res1"))
    )
    (comp (ref "R068")
      (value "100")
      (footprint "1608[0603]")
      (description "Resistor")
      (fields (field (name "Comment") "Res1") (field (name "PUBLISHER") "Altium Limited"))
      (libsource (lib "Miscellaneous Devices") (part "Res1"))
    )
    (comp (ref "R069")
      (value "100")
      (footprint "1608[0603]")
      (description "Resistor")
      (fields (field (name "Comment") "Res1") (field (name "PUBLISHER") "Altium Limited"))
      (libsource (lib "Miscellaneous Devices") (part "Res1"))
    )
    (comp (ref "R070")
      (value "100")
      (footprint "1608[0603]")
      (description "Resistor")
      (fields (field (name "Comment") "Res1") (field (name "PUBLISHER") "Altium Limited"))
      (libsource (lib "Miscellaneous Devices") (part "Res1"))
    )
    (comp (ref "R071")
      (value "100")
      (footprint "1608[0603]")
      (description "Resistor")
      (fields (field (name "Comment") "Res1") (field (name "PUBLISHER") "Altium Limited"))
      (libsource (lib "Miscellaneous Devices") (part "Res1"))
    )
    (comp (ref "R072")
      (value "100")
      (footprint "1608[0603]")
      (description "Resistor")
      (fields (field (name "Comment") "Res1") (field (name "PUBLISHER") "Altium Limited"))
      (libsource (lib "Miscellaneous Devices") (part "Res1"))
    )
    (comp (ref "R073")
      (value "100")
      (footprint "1608[0603]")
      (description "Resistor")
      (fields (field (name "Comment") "Res1") (field (name "PUBLISHER") "Altium Limited"))
      (libsource (lib "Miscellaneous Devices") (part "Res1"))
    )
    (comp (ref "R074")
      (value "100")
      (footprint "1608[0603]")
      (description "Resistor")
      (fields (field (name "Comment") "Res1") (field (name "PUBLISHER") "Altium Limited"))
      (libsource (lib "Miscellaneous Devices") (part "Res1"))
    )
    (comp (ref "R075")
      (value "100")
      (footprint "1608[0603]")
      (description "Resistor")
      (fields (field (name "Comment") "Res1") (field (name "PUBLISHER") "Altium Limited"))
      (libsource (lib "Miscellaneous Devices") (part "Res1"))
    )
    (comp (ref "R095")
      (value "100")
      (footprint "1608[0603]")
      (description "Resistor")
      (fields (field (name "Comment") "Res1") (field (name "PUBLISHER") "Altium Limited"))
      (libsource (lib "Miscellaneous Devices") (part "Res1"))
    )
    (comp (ref "R097")
      (value "100")
      (footprint "1608[0603]")
      (description "Resistor")
      (fields (field (name "Comment") "Res1") (field (name "PUBLISHER") "Altium Limited"))
      (libsource (lib "Miscellaneous Devices") (part "Res1"))
    )
    (comp (ref "R099")
      (value "100")
      (footprint "1608[0603]")
      (description "Resistor")
      (fields (field (name "Comment") "Res1") (field (name "PUBLISHER") "Altium Limited"))
      (libsource (lib "Miscellaneous Devices") (part "Res1"))
    )
    (comp (ref "R101")
      (value "100")
      (footprint "1608[0603]")
      (description "Resistor")
      (fields (field (name "Comment") "Res1") (field (name "PUBLISHER") "Altium Limited"))
      (libsource (lib "Miscellaneous Devices") (part "Res1"))
    )
    (comp (ref "RC1")
      (value "0")
      (footprint "1608[0603]")
      (description "Resistor")
      (fields (field (name "Comment") "Res1") (field (name "PUBLISHER") "Altium Limited"))
      (libsource (lib "Miscellaneous Devices") (part "Res1"))
    )
    (comp (ref "RC2")
      (value "0")
      (footprint "1608[0603]")
      (description "Resistor")
      (fields (field (name "Comment") "Res1") (field (name "PUBLISHER") "Altium Limited"))
      (libsource (lib "Miscellaneous Devices") (part "Res1"))
    )
    (comp (ref "RC3")
      (value "0")
      (footprint "1608[0603]")
      (description "Resistor")
      (fields (field (name "Comment") "Res1") (field (name "PUBLISHER") "Altium Limited"))
      (libsource (lib "Miscellaneous Devices") (part "Res1"))
    )
    (comp (ref "RC4")
      (value "0")
      (footprint "1608[0603]")
      (description "Resistor")
      (fields (field (name "Comment") "Res1") (field (name "PUBLISHER") "Altium Limited"))
      (libsource (lib "Miscellaneous Devices") (part "Res1"))
    )
    (comp (ref "RC5")
      (value "0")
      (footprint "1608[0603]")
      (description "Resistor")
      (fields (field (name "Comment") "Res1") (field (name "PUBLISHER") "Altium Limited"))
      (libsource (lib "Miscellaneous Devices") (part "Res1"))
    )
    (comp (ref "RC6")
      (value "0")
      (footprint "1608[0603]")
      (description "Resistor")
      (fields (field (name "Comment") "Res1") (field (name "PUBLISHER") "Altium Limited"))
      (libsource (lib "Miscellaneous Devices") (part "Res1"))
    )
    (comp (ref "RC7")
      (value "0")
      (footprint "1608[0603]")
      (description "Resistor")
      (fields (field (name "Comment") "Res1") (field (name "PUBLISHER") "Altium Limited"))
      (libsource (lib "Miscellaneous Devices") (part "Res1"))
    )
    (comp (ref "RC8")
      (value "0")
      (footprint "1608[0603]")
      (description "Resistor")
      (fields (field (name "Comment") "Res1") (field (name "PUBLISHER") "Altium Limited"))
      (libsource (lib "Miscellaneous Devices") (part "Res1"))
    )
    (comp (ref "RC9")
      (value "0")
      (footprint "1608[0603]")
      (description "Resistor")
      (fields (field (name "Comment") "Res1") (field (name "PUBLISHER") "Altium Limited"))
      (libsource (lib "Miscellaneous Devices") (part "Res1"))
    )
    (comp (ref "RC10")
      (value "0")
      (footprint "1608[0603]")
      (description "Resistor")
      (fields (field (name "Comment") "Res1") (field (name "PUBLISHER") "Altium Limited"))
      (libsource (lib "Miscellaneous Devices") (part "Res1"))
    )
    (comp (ref "Rr1")
      (value "1.4k")
      (footprint "1608[0603]")
      (description "Resistor")
      (fields (field (name "Comment") "Res1") (field (name "PUBLISHER") "Altium Limited"))
      (libsource (lib "Miscellaneous Devices") (part "Res1"))
    )
    (comp (ref "Rr2")
      (value "1.4k")
      (footprint "1608[0603]")
      (description "Resistor")
      (fields (field (name "Comment") "Res1") (field (name "PUBLISHER") "Altium Limited"))
      (libsource (lib "Miscellaneous Devices") (part "Res1"))
    )
    (comp (ref "Rr3")
      (value "1.4k")
      (footprint "1608[0603]")
      (description "Resistor")
      (fields (field (name "Comment") "Res1") (field (name "PUBLISHER") "Altium Limited"))
      (libsource (lib "Miscellaneous Devices") (part "Res1"))
    )
    (comp (ref "Rr4")
      (value "1.4k")
      (footprint "1608[0603]")
      (description "Resistor")
      (fields (field (name "Comment") "Res1") (field (name "PUBLISHER") "Altium Limited"))
      (libsource (lib "Miscellaneous Devices") (part "Res1"))
    )
    (comp (ref "Rr5")
      (value "1.4k")
      (footprint "1608[0603]")
      (description "Resistor")
      (fields (field (name "Comment") "Res1") (field (name "PUBLISHER") "Altium Limited"))
      (libsource (lib "Miscellaneous Devices") (part "Res1"))
    )
    (comp (ref "Rr6")
      (value "1.4k")
      (footprint "1608[0603]")
      (description "Resistor")
      (fields (field (name "Comment") "Res1") (field (name "PUBLISHER") "Altium Limited"))
      (libsource (lib "Miscellaneous Devices") (part "Res1"))
    )
    (comp (ref "Rr7")
      (value "1.4k")
      (footprint "1608[0603]")
      (description "Resistor")
      (fields (field (name "Comment") "Res1") (field (name "PUBLISHER") "Altium Limited"))
      (libsource (lib "Miscellaneous Devices") (part "Res1"))
    )
    (comp (ref "Rr8")
      (value "1.4k")
      (footprint "1608[0603]")
      (description "Resistor")
      (fields (field (name "Comment") "Res1") (field (name "PUBLISHER") "Altium Limited"))
      (libsource (lib "Miscellaneous Devices") (part "Res1"))
    )
    (comp (ref "R_AI1")
      (value "100")
      (footprint "1608[0603]")
      (description "Resistor")
      (fields (field (name "Comment") "Res1") (field (name "PUBLISHER") "Altium Limited"))
      (libsource (lib "Miscellaneous Devices") (part "Res1"))
    )
    (comp (ref "R_AI1b")
      (value "100")
      (footprint "1608[0603]")
      (description "Resistor")
      (fields (field (name "Comment") "Res1") (field (name "PUBLISHER") "Altium Limited"))
      (libsource (lib "Miscellaneous Devices") (part "Res1"))
    )
    (comp (ref "R_AI2")
      (value "100")
      (footprint "1608[0603]")
      (description "Resistor")
      (fields (field (name "Comment") "Res1") (field (name "PUBLISHER") "Altium Limited"))
      (libsource (lib "Miscellaneous Devices") (part "Res1"))
    )
    (comp (ref "R_AI2b")
      (value "100")
      (footprint "1608[0603]")
      (description "Resistor")
      (fields (field (name "Comment") "Res1") (field (name "PUBLISHER") "Altium Limited"))
      (libsource (lib "Miscellaneous Devices") (part "Res1"))
    )
    (comp (ref "R_AI3")
      (value "100")
      (footprint "1608[0603]")
      (description "Resistor")
      (fields (field (name "Comment") "Res1") (field (name "PUBLISHER") "Altium Limited"))
      (libsource (lib "Miscellaneous Devices") (part "Res1"))
    )
    (comp (ref "R_AI3b")
      (value "100")
      (footprint "1608[0603]")
      (description "Resistor")
      (fields (field (name "Comment") "Res1") (field (name "PUBLISHER") "Altium Limited"))
      (libsource (lib "Miscellaneous Devices") (part "Res1"))
    )
    (comp (ref "R_AI4")
      (value "100")
      (footprint "1608[0603]")
      (description "Resistor")
      (fields (field (name "Comment") "Res1") (field (name "PUBLISHER") "Altium Limited"))
      (libsource (lib "Miscellaneous Devices") (part "Res1"))
    )
    (comp (ref "R_AI4b")
      (value "100")
      (footprint "1608[0603]")
      (description "Resistor")
      (fields (field (name "Comment") "Res1") (field (name "PUBLISHER") "Altium Limited"))
      (libsource (lib "Miscellaneous Devices") (part "Res1"))
    )
    (comp (ref "R_AI5")
      (value "100")
      (footprint "1608[0603]")
      (description "Resistor")
      (fields (field (name "Comment") "Res1") (field (name "PUBLISHER") "Altium Limited"))
      (libsource (lib "Miscellaneous Devices") (part "Res1"))
    )
    (comp (ref "R_AI5b")
      (value "100")
      (footprint "1608[0603]")
      (description "Resistor")
      (fields (field (name "Comment") "Res1") (field (name "PUBLISHER") "Altium Limited"))
      (libsource (lib "Miscellaneous Devices") (part "Res1"))
    )
    (comp (ref "R_AI6")
      (value "100")
      (footprint "1608[0603]")
      (description "Resistor")
      (fields (field (name "Comment") "Res1") (field (name "PUBLISHER") "Altium Limited"))
      (libsource (lib "Miscellaneous Devices") (part "Res1"))
    )
    (comp (ref "R_AI6b")
      (value "100")
      (footprint "1608[0603]")
      (description "Resistor")
      (fields (field (name "Comment") "Res1") (field (name "PUBLISHER") "Altium Limited"))
      (libsource (lib "Miscellaneous Devices") (part "Res1"))
    )
    (comp (ref "R_AI7")
      (value "100")
      (footprint "1608[0603]")
      (description "Resistor")
      (fields (field (name "Comment") "Res1") (field (name "PUBLISHER") "Altium Limited"))
      (libsource (lib "Miscellaneous Devices") (part "Res1"))
    )
    (comp (ref "R_AI7b")
      (value "100")
      (footprint "1608[0603]")
      (description "Resistor")
      (fields (field (name "Comment") "Res1") (field (name "PUBLISHER") "Altium Limited"))
      (libsource (lib "Miscellaneous Devices") (part "Res1"))
    )
    (comp (ref "R_Iunit")
      (value "7k")
      (footprint "1608[0603]")
      (description "Resistor")
      (fields (field (name "Comment") "Res1") (field (name "PUBLISHER") "Altium Limited"))
      (libsource (lib "Miscellaneous Devices") (part "Res1"))
    )
    (comp (ref "U0")
      (value "ADG706BRUZ")
      (footprint "ADI-RU-28_N")
      (fields (field (name "MANUFACTURER") "Analog Devices"))
      (libsource (lib "Analog Devices Switches and Multiplexers Multiplexers (Muxes)") (part "ADG706BRUZ"))
    )
    (comp (ref "Vbias")
      (value "SMB")
      (footprint "SMB_V-RJ45")
      (description "SMB Straight Connector")
      (fields (field (name "PUBLISHER") "Altium Limited"))
      (libsource (lib "Miscellaneous Connectors") (part "SMB"))
    )
    (comp (ref "Vbias2")
      (value "SMB")
      (footprint "SMB_V-RJ45")
      (description "SMB Straight Connector")
      (fields (field (name "PUBLISHER") "Altium Limited"))
      (libsource (lib "Miscellaneous Connectors") (part "SMB"))
    )
    (comp (ref "VDDD")
      (value "SMB")
      (footprint "SMB_V-RJ45")
      (description "SMB Straight Connector")
      (fields (field (name "PUBLISHER") "Altium Limited"))
      (libsource (lib "Miscellaneous Connectors") (part "SMB"))
    )
    (comp (ref "VSSS")
      (value "SMB")
      (footprint "SMB_V-RJ45")
      (description "SMB Straight Connector")
      (fields (field (name "PUBLISHER") "Altium Limited"))
      (libsource (lib "Miscellaneous Connectors") (part "SMB"))
    )
    (comp (ref "V_demod")
      (value "SMB")
      (footprint "SMB_V-RJ45")
      (description "SMB Straight Connector")
      (fields (field (name "PUBLISHER") "Altium Limited"))
      (libsource (lib "Miscellaneous Connectors") (part "SMB"))
    )
    (comp (ref "V_fH")
      (value "SMB")
      (footprint "SMB_V-RJ45")
      (description "SMB Straight Connector")
      (fields (field (name "PUBLISHER") "Altium Limited"))
      (libsource (lib "Miscellaneous Connectors") (part "SMB"))
    )
  )
  (nets
    (net (code "1") (name "/AI1") (class "Default")
      (node (ref "C_AI1") (pin "1") (pinfunction "1_1") (pintype "passive"))
      (node (ref "J1") (pin "33") (pinfunction "33_33") (pintype "passive"))
      (node (ref "R_AI1") (pin "1") (pinfunction "1_1") (pintype "passive"))
    )
    (net (code "2") (name "/AI1b") (class "Default")
      (node (ref "C_AI1b") (pin "1") (pinfunction "1_1") (pintype "passive"))
      (node (ref "J1") (pin "66") (pinfunction "66_66") (pintype "passive"))
      (node (ref "R_AI1b") (pin "2") (pinfunction "2_2") (pintype "passive"))
    )
    (net (code "3") (name "/AI2") (class "Default")
      (node (ref "C_AI2") (pin "1") (pinfunction "1_1") (pintype "passive"))
      (node (ref "J1") (pin "65") (pinfunction "65_65") (pintype "passive"))
      (node (ref "R_AI2") (pin "1") (pinfunction "1_1") (pintype "passive"))
    )
    (net (code "4") (name "/AI2b") (class "Default")
      (node (ref "C_AI2b") (pin "1") (pinfunction "1_1") (pintype "passive"))
      (node (ref "J1") (pin "31") (pinfunction "31_31") (pintype "passive"))
      (node (ref "R_AI2b") (pin "2") (pinfunction "2_2") (pintype "passive"))
    )
    (net (code "5") (name "/AI3") (class "Default")
      (node (ref "C_AI3") (pin "1") (pinfunction "1_1") (pintype "passive"))
      (node (ref "J1") (pin "30") (pinfunction "30_30") (pintype "passive"))
      (node (ref "R_AI3") (pin "1") (pinfunction "1_1") (pintype "passive"))
    )
    (net (code "6") (name "/AI3b") (class "Default")
      (node (ref "C_AI3b") (pin "1") (pinfunction "1_1") (pintype "passive"))
      (node (ref "J1") (pin "63") (pinfunction "63_63") (pintype "passive"))
      (node (ref "R_AI3b") (pin "2") (pinfunction "2_2") (pintype "passive"))
    )
    (net (code "7") (name "/AI4") (class "Default")
      (node (ref "C_AI4") (pin "1") (pinfunction "1_1") (pintype "passive"))
      (node (ref "J1") (pin "28") (pinfunction "28_28") (pintype "passive"))
      (node (ref "R_AI4") (pin "1") (pinfunction "1_1") (pintype "passive"))
    )
    (net (code "8") (name "/AI4b") (class "Default")
      (node (ref "C_AI4b") (pin "1") (pinfunction "1_1") (pintype "passive"))
      (node (ref "J1") (pin "61") (pinfunction "61_61") (pintype "passive"))
      (node (ref "R_AI4b") (pin "2") (pinfunction "2_2") (pintype "passive"))
    )
    (net (code "9") (name "/AI5") (class "Default")
      (node (ref "C_AI5") (pin "1") (pinfunction "1_1") (pintype "passive"))
      (node (ref "J1") (pin "60") (pinfunction "60_60") (pintype "passive"))
      (node (ref "R_AI5") (pin "1") (pinfunction "1_1") (pintype "passive"))
    )
    (net (code "10") (name "/AI5b") (class "Default")
      (node (ref "C_AI5b") (pin "1") (pinfunction "1_1") (pintype "passive"))
      (node (ref "J1") (pin "26") (pinfunction "26_26") (pintype "passive"))
      (node (ref "R_AI5b") (pin "2") (pinfunction "2_2") (pintype "passive"))
    )
    (net (code "11") (name "/AI6") (class "Default")
      (node (ref "C_AI6") (pin "1") (pinfunction "1_1") (pintype "passive"))
      (node (ref "J1") (pin "25") (pinfunction "25_25") (pintype "passive"))
      (node (ref "R_AI6") (pin "1") (pinfunction "1_1") (pintype "passive"))
    )
    (net (code "12") (name "/AI6b") (class "Default")
      (node (ref "C_AI6b") (pin "1") (pinfunction "1_1") (pintype "passive"))
      (node (ref "J1") (pin "58") (pinfunction "58_58") (pintype "passive"))
      (node (ref "R_AI6b") (pin "2") (pinfunction "2_2") (pintype "passive"))
    )
    (net (code "13") (name "/AI7") (class "Default")
      (node (ref "C_AI7") (pin "1") (pinfunction "1_1") (pintype "passive"))
      (node (ref "J1") (pin "57") (pinfunction "57_57") (pintype "passive"))
      (node (ref "R_AI7") (pin "1") (pinfunction "1_1") (pintype "passive"))
    )
    (net (code "14") (name "/AI7b") (class "Default")
      (node (ref "C_AI7b") (pin "1") (pinfunction "1_1") (pintype "passive"))
      (node (ref "J1") (pin "23") (pinfunction "23_23") (pintype "passive"))
      (node (ref "R_AI7b") (pin "2") (pinfunction "2_2") (pintype "passive"))
    )
    (net (code "16") (name "/A_IN1") (class "Default")
      (node (ref "J_Ain1") (pin "1") (pinfunction "1_1") (pintype "passive"))
    )
    (net (code "17") (name "/A_IN2") (class "Default")
      (node (ref "J_Ain2") (pin "1") (pinfunction "1_1") (pintype "passive"))
    )
    (net (code "18") (name "/A_IN3") (class "Default")
      (node (ref "J_Ain3") (pin "1") (pinfunction "1_1") (pintype "passive"))
    )
    (net (code "19") (name "/A_IN4") (class "Default")
      (node (ref "J_Ain4") (pin "1") (pinfunction "1_1") (pintype "passive"))
    )
    (net (code "20") (name "/A_IN5") (class "Default")
      (node (ref "J_Ain5") (pin "1") (pinfunction "1_1") (pintype "passive"))
    )
    (net (code "21") (name "/A_IN6") (class "Default")
      (node (ref "J_Ain6") (pin "1") (pinfunction "1_1") (pintype "passive"))
    )
    (net (code "22") (name "/A_IN7") (class "Default")
      (node (ref "J_Ain7") (pin "1") (pinfunction "1_1") (pintype "passive"))
    )
    (net (code "23") (name "/A_IN8") (class "Default")
      (node (ref "J_Ain8") (pin "1") (pinfunction "1_1") (pintype "passive"))
    )
    (net (code "24") (name "/A_IN9") (class "Default")
      (node (ref "J_Ain9") (pin "1") (pinfunction "1_1") (pintype "passive"))
    )
    (net (code "25") (name "/A_IN10") (class "Default")
      (node (ref "J_Ain10") (pin "1") (pinfunction "1_1") (pintype "passive"))
    )
    (net (code "26") (name "/A_IN11") (class "Default")
      (node (ref "J_Ain11") (pin "1") (pinfunction "1_1") (pintype "passive"))
    )
    (net (code "27") (name "/A_IN12") (class "Default")
      (node (ref "J_Ain12") (pin "1") (pinfunction "1_1") (pintype "passive"))
    )
    (net (code "28") (name "/A_IN13") (class "Default")
      (node (ref "J_Ain13") (pin "1") (pinfunction "1_1") (pintype "passive"))
    )
    (net (code "29") (name "/A_IN14") (class "Default")
      (node (ref "J_Ain14") (pin "1") (pinfunction "1_1") (pintype "passive"))
    )
    (net (code "30") (name "/A_IN15") (class "Default")
      (node (ref "J_Ain15") (pin "1") (pinfunction "1_1") (pintype "passive"))
    )
    (net (code "31") (name "/A_IN16") (class "Default")
      (node (ref "J_Ain16") (pin "1") (pinfunction "1_1") (pintype "passive"))
    )
    (net (code "32") (name "/A_IN17") (class "Default")
      (node (ref "J_Ain17") (pin "1") (pinfunction "1_1") (pintype "passive"))
    )
    (net (code "33") (name "/A_IN18") (class "Default")
      (node (ref "J_Ain18") (pin "1") (pinfunction "1_1") (pintype "passive"))
    )
    (net (code "34") (name "/A_IN19") (class "Default")
      (node (ref "J_Ain19") (pin "1") (pinfunction "1_1") (pintype "passive"))
    )
    (net (code "35") (name "/A_IN20") (class "Default")
      (node (ref "J_Ain20") (pin "1") (pinfunction "1_1") (pintype "passive"))
    )
    (net (code "36") (name "/A_IN21") (class "Default")
      (node (ref "J_Ain21") (pin "1") (pinfunction "1_1") (pintype "passive"))
    )
    (net (code "37") (name "/A_IN22") (class "Default")
      (node (ref "J_Ain22") (pin "1") (pinfunction "1_1") (pintype "passive"))
    )
    (net (code "38") (name "/A_IN23") (class "Default")
      (node (ref "J_Ain23") (pin "1") (pinfunction "1_1") (pintype "passive"))
    )
    (net (code "41") (name "/A_OUT1") (class "Default")
      (node (ref "J_Aout1") (pin "1") (pinfunction "1_1") (pintype "passive"))
    )
    (net (code "42") (name "/A_OUT2") (class "Default")
      (node (ref "J_Aout2") (pin "1") (pinfunction "1_1") (pintype "passive"))
    )
    (net (code "43") (name "/A_OUT3") (class "Default")
      (node (ref "J_Aout3") (pin "1") (pinfunction "1_1") (pintype "passive"))
    )
    (net (code "44") (name "/A_OUT4") (class "Default")
      (node (ref "J_Aout4") (pin "1") (pinfunction "1_1") (pintype "passive"))
    )
    (net (code "45") (name "/A_OUT5") (class "Default")
      (node (ref "J_Aout5") (pin "1") (pinfunction "1_1") (pintype "passive"))
    )
    (net (code "46") (name "/A_OUT6") (class "Default")
      (node (ref "J_Aout6") (pin "1") (pinfunction "1_1") (pintype "passive"))
    )
    (net (code "47") (name "/A_OUT7") (class "Default")
      (node (ref "J_Aout7") (pin "1") (pinfunction "1_1") (pintype "passive"))
    )
    (net (code "48") (name "/A_OUT8") (class "Default")
      (node (ref "J_Aout8") (pin "1") (pinfunction "1_1") (pintype "passive"))
    )
    (net (code "49") (name "/A_OUT9") (class "Default")
      (node (ref "J_Aout9") (pin "1") (pinfunction "1_1") (pintype "passive"))
    )
    (net (code "50") (name "/A_OUT10") (class "Default")
      (node (ref "J_Aout10") (pin "1") (pinfunction "1_1") (pintype "passive"))
    )
    (net (code "51") (name "/A_OUT11") (class "Default")
      (node (ref "J_Aout11") (pin "1") (pinfunction "1_1") (pintype "passive"))
    )
    (net (code "52") (name "/A_OUT12") (class "Default")
      (node (ref "J_Aout12") (pin "1") (pinfunction "1_1") (pintype "passive"))
    )
    (net (code "53") (name "/A_OUT13") (class "Default")
      (node (ref "J_Aout13") (pin "1") (pinfunction "1_1") (pintype "passive"))
    )
    (net (code "54") (name "/A_OUT14") (class "Default")
      (node (ref "J_Aout14") (pin "1") (pinfunction "1_1") (pintype "passive"))
    )
    (net (code "55") (name "/A_OUT15") (class "Default")
      (node (ref "J_Aout15") (pin "1") (pinfunction "1_1") (pintype "passive"))
    )
    (net (code "56") (name "/A_OUT16") (class "Default")
      (node (ref "J_Aout16") (pin "1") (pinfunction "1_1") (pintype "passive"))
    )
    (net (code "57") (name "/A_OUT17") (class "Default")
      (node (ref "J_Aout17") (pin "1") (pinfunction "1_1") (pintype "passive"))
    )
    (net (code "58") (name "/A_OUT18") (class "Default")
      (node (ref "J_Aout18") (pin "1") (pinfunction "1_1") (pintype "passive"))
    )
    (net (code "59") (name "/A_OUT19") (class "Default")
      (node (ref "J_Aout19") (pin "1") (pinfunction "1_1") (pintype "passive"))
    )
    (net (code "60") (name "/A_OUT20") (class "Default")
      (node (ref "J_Aout20") (pin "1") (pinfunction "1_1") (pintype "passive"))
    )
    (net (code "61") (name "/A_OUT21") (class "Default")
      (node (ref "J_Aout21") (pin "1") (pinfunction "1_1") (pintype "passive"))
    )
    (net (code "62") (name "/A_OUT22") (class "Default")
      (node (ref "J_Aout22") (pin "1") (pinfunction "1_1") (pintype "passive"))
    )
    (net (code "63") (name "/A_OUT23") (class "Default")
      (node (ref "J_Aout23") (pin "1") (pinfunction "1_1") (pintype "passive"))
    )
    (net (code "65") (name "/Ain") (class "Default")
      (node (ref "P1") (pin "48") (pinfunction "48_48") (pintype "passive"))
      (node (ref "R019") (pin "1") (pinfunction "1_1") (pintype "passive"))
    )
    (net (code "66") (name "/BWlimit") (class "Default")
      (node (ref "P1") (pin "39") (pinfunction "39_39") (pintype "passive"))
      (node (ref "R041") (pin "1") (pinfunction "1_1") (pintype "passive"))
    )
    (net (code "68") (name "/B_IN1") (class "Default")
      (node (ref "J_Bin1") (pin "1") (pinfunction "1_1") (pintype "passive"))
    )
    (net (code "69") (name "/B_IN2") (class "Default")
      (node (ref "J_Bin2") (pin "1") (pinfunction "1_1") (pintype "passive"))
    )
    (net (code "70") (name "/B_IN3") (class "Default")
      (node (ref "J_Bin3") (pin "1") (pinfunction "1_1") (pintype "passive"))
    )
    (net (code "71") (name "/B_IN4") (class "Default")
      (node (ref "J_Bin4") (pin "1") (pinfunction "1_1") (pintype "passive"))
    )
    (net (code "72") (name "/B_IN5") (class "Default")
      (node (ref "J_Bin5") (pin "1") (pinfunction "1_1") (pintype "passive"))
    )
    (net (code "73") (name "/B_IN6") (class "Default")
      (node (ref "J_Bin6") (pin "1") (pinfunction "1_1") (pintype "passive"))
    )
    (net (code "74") (name "/B_IN7") (class "Default")
      (node (ref "J_Bin7") (pin "1") (pinfunction "1_1") (pintype "passive"))
    )
    (net (code "75") (name "/B_IN8") (class "Default")
      (node (ref "J_Bin8") (pin "1") (pinfunction "1_1") (pintype "passive"))
    )
    (net (code "76") (name "/B_IN9") (class "Default")
      (node (ref "J_Bin9") (pin "1") (pinfunction "1_1") (pintype "passive"))
    )
    (net (code "77") (name "/B_IN10") (class "Default")
      (node (ref "J_Bin10") (pin "1") (pinfunction "1_1") (pintype "passive"))
    )
    (net (code "78") (name "/B_IN11") (class "Default")
      (node (ref "J_Bin11") (pin "1") (pinfunction "1_1") (pintype "passive"))
    )
    (net (code "79") (name "/B_IN12") (class "Default")
      (node (ref "J_Bin12") (pin "1") (pinfunction "1_1") (pintype "passive"))
    )
    (net (code "80") (name "/B_IN13") (class "Default")
      (node (ref "J_Bin13") (pin "1") (pinfunction "1_1") (pintype "passive"))
    )
    (net (code "81") (name "/B_IN14") (class "Default")
      (node (ref "J_Bin14") (pin "1") (pinfunction "1_1") (pintype "passive"))
    )
    (net (code "82") (name "/B_IN15") (class "Default")
      (node (ref "J_Bin15") (pin "1") (pinfunction "1_1") (pintype "passive"))
    )
    (net (code "83") (name "/B_IN16") (class "Default")
      (node (ref "J_Bin16") (pin "1") (pinfunction "1_1") (pintype "passive"))
    )
    (net (code "84") (name "/B_IN17") (class "Default")
      (node (ref "J_Bin17") (pin "1") (pinfunction "1_1") (pintype "passive"))
    )
    (net (code "85") (name "/B_IN18") (class "Default")
      (node (ref "J_Bin18") (pin "1") (pinfunction "1_1") (pintype "passive"))
    )
    (net (code "86") (name "/B_IN19") (class "Default")
      (node (ref "J_Bin19") (pin "1") (pinfunction "1_1") (pintype "passive"))
    )
    (net (code "87") (name "/B_IN20") (class "Default")
      (node (ref "J_Bin20") (pin "1") (pinfunction "1_1") (pintype "passive"))
    )
    (net (code "88") (name "/B_IN21") (class "Default")
      (node (ref "J_Bin21") (pin "1") (pinfunction "1_1") (pintype "passive"))
    )
    (net (code "89") (name "/B_IN22") (class "Default")
      (node (ref "J_Bin22") (pin "1") (pinfunction "1_1") (pintype "passive"))
    )
    (net (code "90") (name "/B_IN23") (class "Default")
      (node (ref "J_Bin23") (pin "1") (pinfunction "1_1") (pintype "passive"))
    )
    (net (code "93") (name "/B_OUT1") (class "Default")
      (node (ref "J_Bout1") (pin "1") (pinfunction "1_1") (pintype "passive"))
    )
    (net (code "94") (name "/B_OUT2") (class "Default")
      (node (ref "J_Bout2") (pin "1") (pinfunction "1_1") (pintype "passive"))
    )
    (net (code "95") (name "/B_OUT3") (class "Default")
      (node (ref "J_Bout3") (pin "1") (pinfunction "1_1") (pintype "passive"))
    )
    (net (code "96") (name "/B_OUT4") (class "Default")
      (node (ref "J_Bout4") (pin "1") (pinfunction "1_1") (pintype "passive"))
    )
    (net (code "97") (name "/B_OUT5") (class "Default")
      (node (ref "J_Bout5") (pin "1") (pinfunction "1_1") (pintype "passive"))
    )
    (net (code "98") (name "/B_OUT6") (class "Default")
      (node (ref "J_Bout6") (pin "1") (pinfunction "1_1") (pintype "passive"))
    )
    (net (code "99") (name "/B_OUT7") (class "Default")
      (node (ref "J_Bout7") (pin "1") (pinfunction "1_1") (pintype "passive"))
    )
    (net (code "100") (name "/B_OUT8") (class "Default")
      (node (ref "J_Bout8") (pin "1") (pinfunction "1_1") (pintype "passive"))
    )
    (net (code "101") (name "/B_OUT9") (class "Default")
      (node (ref "J_Bout9") (pin "1") (pinfunction "1_1") (pintype "passive"))
    )
    (net (code "102") (name "/B_OUT10") (class "Default")
      (node (ref "J_Bout10") (pin "1") (pinfunction "1_1") (pintype "passive"))
    )
    (net (code "103") (name "/B_OUT11") (class "Default")
      (node (ref "J_Bout11") (pin "1") (pinfunction "1_1") (pintype "passive"))
    )
    (net (code "104") (name "/B_OUT12") (class "Default")
      (node (ref "J_Bout12") (pin "1") (pinfunction "1_1") (pintype "passive"))
    )
    (net (code "105") (name "/B_OUT13") (class "Default")
      (node (ref "J_Bout13") (pin "1") (pinfunction "1_1") (pintype "passive"))
    )
    (net (code "106") (name "/B_OUT14") (class "Default")
      (node (ref "J_Bout14") (pin "1") (pinfunction "1_1") (pintype "passive"))
    )
    (net (code "107") (name "/B_OUT15") (class "Default")
      (node (ref "J_Bout15") (pin "1") (pinfunction "1_1") (pintype "passive"))
    )
    (net (code "108") (name "/B_OUT16") (class "Default")
      (node (ref "J_Bout16") (pin "1") (pinfunction "1_1") (pintype "passive"))
    )
    (net (code "109") (name "/B_OUT17") (class "Default")
      (node (ref "J_Bout17") (pin "1") (pinfunction "1_1") (pintype "passive"))
    )
    (net (code "110") (name "/B_OUT18") (class "Default")
      (node (ref "J_Bout18") (pin "1") (pinfunction "1_1") (pintype "passive"))
    )
    (net (code "111") (name "/B_OUT19") (class "Default")
      (node (ref "J_Bout19") (pin "1") (pinfunction "1_1") (pintype "passive"))
    )
    (net (code "112") (name "/B_OUT20") (class "Default")
      (node (ref "J_Bout20") (pin "1") (pinfunction "1_1") (pintype "passive"))
    )
    (net (code "113") (name "/B_OUT21") (class "Default")
      (node (ref "J_Bout21") (pin "1") (pinfunction "1_1") (pintype "passive"))
    )
    (net (code "114") (name "/B_OUT22") (class "Default")
      (node (ref "J_Bout22") (pin "1") (pinfunction "1_1") (pintype "passive"))
    )
    (net (code "115") (name "/B_OUT23") (class "Default")
      (node (ref "J_Bout23") (pin "1") (pinfunction "1_1") (pintype "passive"))
    )
    (net (code "117") (name "/Bin") (class "Default")
      (node (ref "P3") (pin "35") (pinfunction "35_35") (pintype "passive"))
      (node (ref "R053") (pin "1") (pinfunction "1_1") (pintype "passive"))
    )
    (net (code "118") (name "/C1") (class "Default")
      (node (ref "P20") (pin "10") (pinfunction "10_10") (pintype "passive"))
      (node (ref "RC1") (pin "2") (pinfunction "2_2") (pintype "passive"))
      (node (ref "U0") (pin "19") (pinfunction "S1_19") (pintype "passive"))
    )
    (net (code "119") (name "/C2") (class "Default")
      (node (ref "P20") (pin "9") (pinfunction "9_9") (pintype "passive"))
      (node (ref "RC2") (pin "2") (pinfunction "2_2") (pintype "passive"))
      (node (ref "U0") (pin "20") (pinfunction "S2_20") (pintype "passive"))
    )
    (net (code "120") (name "/C3") (class "Default")
      (node (ref "P20") (pin "12") (pinfunction "12_12") (pintype "passive"))
      (node (ref "RC3") (pin "2") (pinfunction "2_2") (pintype "passive"))
      (node (ref "U0") (pin "21") (pinfunction "S3_21") (pintype "passive"))
    )
    (net (code "121") (name "/C4") (class "Default")
      (node (ref "P20") (pin "11") (pinfunction "11_11") (pintype "passive"))
      (node (ref "RC4") (pin "2") (pinfunction "2_2") (pintype "passive"))
      (node (ref "U0") (pin "22") (pinfunction "S4_22") (pintype "passive"))
    )
    (net (code "122") (name "/C5") (class "Default")
      (node (ref "P20") (pin "14") (pinfunction "14_14") (pintype "passive"))
      (node (ref "RC5") (pin "2") (pinfunction "2_2") (pintype "passive"))
      (node (ref "U0") (pin "23") (pinfunction "S5_23") (pintype "passive"))
    )
    (net (code "123") (name "/C6") (class "Default")
      (node (ref "P20") (pin "13") (pinfunction "13_13") (pintype "passive"))
      (node (ref "RC6") (pin "2") (pinfunction "2_2") (pintype "passive"))
      (node (ref "U0") (pin "24") (pinfunction "S6_24") (pintype "passive"))
    )
    (net (code "124") (name "/C7") (class "Default")
      (node (ref "P20") (pin "16") (pinfunction "16_16") (pintype "passive"))
      (node (ref "RC7") (pin "2") (pinfunction "2_2") (pintype "passive"))
      (node (ref "U0") (pin "25") (pinfunction "S7_25") (pintype "passive"))
    )
    (net (code "125") (name "/C8") (class "Default")
      (node (ref "P20") (pin "15") (pinfunction "15_15") (pintype "passive"))
      (node (ref "RC8") (pin "2") (pinfunction "2_2") (pintype "passive"))
      (node (ref "U0") (pin "26") (pinfunction "S8_26") (pintype "passive"))
    )
    (net (code "126") (name "/C9") (class "Default")
      (node (ref "P20") (pin "2") (pinfunction "2_2") (pintype "passive"))
      (node (ref "RC9") (pin "2") (pinfunction "2_2") (pintype "passive"))
      (node (ref "U0") (pin "11") (pinfunction "S9_11") (pintype "passive"))
    )
    (net (code "127") (name "/C10") (class "Default")
      (node (ref "P20") (pin "1") (pinfunction "1_1") (pintype "passive"))
      (node (ref "RC10") (pin "2") (pinfunction "2_2") (pintype "passive"))
      (node (ref "U0") (pin "10") (pinfunction "S10_10") (pintype "passive"))
    )
    (net (code "128") (name "/Clk_DSM") (class "Default")
      (node (ref "P1") (pin "29") (pinfunction "29_29") (pintype "passive"))
      (node (ref "R057") (pin "1") (pinfunction "1_1") (pintype "passive"))
    )
    (net (code "129") (name "/Clk_HFIR_SCR") (class "Default")
      (node (ref "P1") (pin "33") (pinfunction "33_33") (pintype "passive"))
      (node (ref "R063") (pin "1") (pinfunction "1_1") (pintype "passive"))
    )
    (net (code "130") (name "/Clk_HFIR_chop") (class "Default")
      (node (ref "P1") (pin "32") (pinfunction "32_32") (pintype "passive"))
      (node (ref "R065") (pin "1") (pinfunction "1_1") (pintype "passive"))
    )
    (net (code "131") (name "/Clk_LO") (class "Default")
      (node (ref "J_demod") (pin "2") (pinfunction "2_2") (pintype "passive"))
      (node (ref "P1") (pin "44") (pinfunction "44_44") (pintype "passive"))
    )
    (net (code "132") (name "/Clk_SCCMFB") (class "Default")
      (node (ref "P1") (pin "40") (pinfunction "40_40") (pintype "passive"))
      (node (ref "R031") (pin "1") (pinfunction "1_1") (pintype "passive"))
    )
    (net (code "133") (name "/Clk_SI") (class "Default")
      (node (ref "P1") (pin "45") (pinfunction "45_45") (pintype "passive"))
      (node (ref "R015") (pin "1") (pinfunction "1_1") (pintype "passive"))
    )
    (net (code "134") (name "/Clk_SO") (class "Default")
      (node (ref "P1") (pin "25") (pinfunction "25_25") (pintype "passive"))
      (node (ref "R075") (pin "1") (pinfunction "1_1") (pintype "passive"))
    )
    (net (code "135") (name "/Clk_SR") (class "Default")
      (node (ref "P1") (pin "27") (pinfunction "27_27") (pintype "passive"))
      (node (ref "R069") (pin "1") (pinfunction "1_1") (pintype "passive"))
    )
    (net (code "136") (name "/Clk_dcr") (class "Default")
      (node (ref "P1") (pin "41") (pinfunction "41_41") (pintype "passive"))
      (node (ref "R037") (pin "1") (pinfunction "1_1") (pintype "passive"))
    )
    (net (code "137") (name "/Clk_ref_1.8") (class "Default")
      (node (ref "R054") (pin "2") (pinfunction "2_2") (pintype "passive"))
    )
    (net (code "140") (name "/Clk_stripe") (class "Default")
      (node (ref "P3") (pin "36") (pinfunction "36_36") (pintype "passive"))
    )
    (net (code "141") (name "/DGND") (class "Default")
      (node (ref "BKconnector") (pin "1") (pinfunction "DGnd_1") (pintype "passive"))
      (node (ref "BKconnector") (pin "115") (pinfunction "DGND_115") (pintype "passive"))
      (node (ref "BKconnector") (pin "13") (pinfunction "DGND_13") (pintype "passive"))
      (node (ref "BKconnector") (pin "135") (pinfunction "DGND_135") (pintype "passive"))
      (node (ref "BKconnector") (pin "14") (pinfunction "DGND_14") (pintype "passive"))
      (node (ref "BKconnector") (pin "158") (pinfunction "DGND_158") (pintype "passive"))
      (node (ref "BKconnector") (pin "160") (pinfunction "DGND_160") (pintype "passive"))
      (node (ref "BKconnector") (pin "36") (pinfunction "DGND_36") (pintype "passive"))
      (node (ref "BKconnector") (pin "56") (pinfunction "DGND_56") (pintype "passive"))
      (node (ref "BKconnector") (pin "78") (pinfunction "DGND_78") (pintype "passive"))
      (node (ref "BKconnector") (pin "80") (pinfunction "DGND_80") (pintype "passive"))
      (node (ref "BKconnector") (pin "82") (pinfunction "DGND_82") (pintype "passive"))
      (node (ref "BKconnector") (pin "94") (pinfunction "DGND_94") (pintype "passive"))
      (node (ref "FB1") (pin "2") (pinfunction "2_2") (pintype "passive"))
      (node (ref "H3") (pin "1") (pintype "passive"))
      (node (ref "H4") (pin "1") (pintype "passive"))
      (node (ref "H5") (pin "1") (pintype "passive"))
      (node (ref "J1") (pin "12") (pinfunction "12_12") (pintype "passive"))
      (node (ref "J1") (pin "13") (pinfunction "13_13") (pintype "passive"))
      (node (ref "J1") (pin "15") (pinfunction "15_15") (pintype "passive"))
      (node (ref "J1") (pin "18") (pinfunction "18_18") (pintype "passive"))
      (node (ref "J1") (pin "35") (pinfunction "35_35") (pintype "passive"))
      (node (ref "J1") (pin "36") (pinfunction "36_36") (pintype "passive"))
      (node (ref "J1") (pin "4") (pinfunction "4_4") (pintype "passive"))
      (node (ref "J1") (pin "44") (pinfunction "44_44") (pintype "passive"))
      (node (ref "J1") (pin "50") (pinfunction "50_50") (pintype "passive"))
      (node (ref "J1") (pin "53") (pinfunction "53_53") (pintype "passive"))
      (node (ref "J1") (pin "7") (pinfunction "7_7") (pintype "passive"))
      (node (ref "J1") (pin "9") (pinfunction "9_9") (pintype "passive"))
      (node (ref "R042") (pin "2") (pinfunction "2_2") (pintype "passive"))
      (node (ref "R044") (pin "2") (pinfunction "2_2") (pintype "passive"))
      (node (ref "R046") (pin "2") (pinfunction "2_2") (pintype "passive"))
      (node (ref "R048") (pin "2") (pinfunction "2_2") (pintype "passive"))
      (node (ref "R050") (pin "2") (pinfunction "2_2") (pintype "passive"))
    )
    (net (code "142") (name "/DVDD") (class "Default")
      (node (ref "P1") (pin "35") (pinfunction "35_35") (pintype "passive"))
      (node (ref "P1") (pin "49") (pinfunction "49_49") (pintype "passive"))
      (node (ref "P2") (pin "23") (pinfunction "23_23") (pintype "passive"))
      (node (ref "P3") (pin "34") (pinfunction "34_34") (pintype "passive"))
      (node (ref "P3") (pin "39") (pinfunction "39_39") (pintype "passive"))
    )
    (net (code "143") (name "/Dout<0>") (class "Default")
      (node (ref "BKconnector") (pin "103") (pinfunction "C5_103") (pintype "passive"))
      (node (ref "P2") (pin "40") (pinfunction "40_40") (pintype "passive"))
    )
    (net (code "144") (name "/Dout<1>") (class "Default")
      (node (ref "BKconnector") (pin "105") (pinfunction "A5_105") (pintype "passive"))
      (node (ref "P2") (pin "37") (pinfunction "37_37") (pintype "passive"))
    )
    (net (code "145") (name "/Dout<2>") (class "Default")
      (node (ref "BKconnector") (pin "107") (pinfunction "D14_107") (pintype "passive"))
      (node (ref "P2") (pin "38") (pinfunction "38_38") (pintype "passive"))
    )
    (net (code "146") (name "/Dout<3>") (class "Default")
      (node (ref "BKconnector") (pin "109") (pinfunction "C14_109") (pintype "passive"))
      (node (ref "P2") (pin "35") (pinfunction "35_35") (pintype "passive"))
    )
    (net (code "147") (name "/Dout<4>") (class "Default")
      (node (ref "BKconnector") (pin "111") (pinfunction "E16_111") (pintype "passive"))
      (node (ref "P2") (pin "36") (pinfunction "36_36") (pintype "passive"))
    )
    (net (code "148") (name "/Dout<5>") (class "Default")
      (node (ref "BKconnector") (pin "113") (pinfunction "D17_113") (pintype "passive"))
      (node (ref "P2") (pin "33") (pinfunction "33_33") (pintype "passive"))
    )
    (net (code "149") (name "/Dout<6>") (class "Default")
      (node (ref "BKconnector") (pin "117") (pinfunction "D7_117") (pintype "passive"))
      (node (ref "P2") (pin "34") (pinfunction "34_34") (pintype "passive"))
    )
    (net (code "150") (name "/Dout<7>") (class "Default")
      (node (ref "BKconnector") (pin "119") (pinfunction "D8_119") (pintype "passive"))
      (node (ref "P2") (pin "31") (pinfunction "31_31") (pintype "passive"))
    )
    (net (code "151") (name "/Dout<8>") (class "Default")
      (node (ref "BKconnector") (pin "121") (pinfunction "L17_121") (pintype "passive"))
      (node (ref "P2") (pin "32") (pinfunction "32_32") (pintype "passive"))
    )
    (net (code "152") (name "/Dout<9>") (class "Default")
      (node (ref "BKconnector") (pin "123") (pinfunction "K18_123") (pintype "passive"))
      (node (ref "P2") (pin "29") (pinfunction "29_29") (pintype "passive"))
    )
    (net (code "153") (name "/Dout<10>") (class "Default")
      (node (ref "BKconnector") (pin "125") (pinfunction "D6_125") (pintype "passive"))
      (node (ref "P2") (pin "30") (pinfunction "30_30") (pintype "passive"))
    )
    (net (code "154") (name "/Dout<11>") (class "Default")
      (node (ref "BKconnector") (pin "127") (pinfunction "C6_127") (pintype "passive"))
      (node (ref "P2") (pin "27") (pinfunction "27_27") (pintype "passive"))
    )
    (net (code "155") (name "/Dout<12>") (class "Default")
      (node (ref "BKconnector") (pin "129") (pinfunction "A3_129") (pintype "passive"))
      (node (ref "P2") (pin "28") (pinfunction "28_28") (pintype "passive"))
    )
    (net (code "156") (name "/Dout<13>") (class "Default")
      (node (ref "BKconnector") (pin "131") (pinfunction "A4_131") (pintype "passive"))
      (node (ref "P2") (pin "25") (pinfunction "25_25") (pintype "passive"))
    )
    (net (code "157") (name "/Dout<14>") (class "Default")
      (node (ref "BKconnector") (pin "133") (pinfunction "B8_133") (pintype "passive"))
      (node (ref "P1") (pin "16") (pinfunction "16_16") (pintype "passive"))
    )
    (net (code "158") (name "/Dout<15>") (class "Default")
      (node (ref "BKconnector") (pin "137") (pinfunction "A8_137") (pintype "passive"))
      (node (ref "P1") (pin "15") (pinfunction "15_15") (pintype "passive"))
    )
    (net (code "159") (name "/Dout<16>") (class "Default")
      (node (ref "BKconnector") (pin "139") (pinfunction "B10_139") (pintype "passive"))
      (node (ref "P1") (pin "14") (pinfunction "14_14") (pintype "passive"))
    )
    (net (code "160") (name "/Dout<17>") (class "Default")
      (node (ref "BKconnector") (pin "141") (pinfunction "A10_141") (pintype "passive"))
      (node (ref "P1") (pin "13") (pinfunction "13_13") (pintype "passive"))
    )
    (net (code "161") (name "/Dout<18>") (class "Default")
      (node (ref "BKconnector") (pin "143") (pinfunction "C13_143") (pintype "passive"))
      (node (ref "P1") (pin "12") (pinfunction "12_12") (pintype "passive"))
    )
    (net (code "162") (name "/Dout<19>") (class "Default")
      (node (ref "BKconnector") (pin "145") (pinfunction "A13_145") (pintype "passive"))
      (node (ref "P1") (pin "11") (pinfunction "11_11") (pintype "passive"))
    )
    (net (code "163") (name "/Dout<20>") (class "Default")
      (node (ref "BKconnector") (pin "147") (pinfunction "C15_147") (pintype "passive"))
      (node (ref "P1") (pin "10") (pinfunction "10_10") (pintype "passive"))
    )
    (net (code "164") (name "/Dout<21>") (class "Default")
      (node (ref "BKconnector") (pin "149") (pinfunction "A15_149") (pintype "passive"))
      (node (ref "P1") (pin "9") (pinfunction "9_9") (pintype "passive"))
    )
    (net (code "165") (name "/Dout<22>") (class "Default")
      (node (ref "BKconnector") (pin "151") (pinfunction "C17_151") (pintype "passive"))
      (node (ref "P1") (pin "8") (pinfunction "8_8") (pintype "passive"))
    )
    (net (code "166") (name "/Dout<23>") (class "Default")
      (node (ref "BKconnector") (pin "153") (pinfunction "A17_153") (pintype "passive"))
      (node (ref "P1") (pin "7") (pinfunction "7_7") (pintype "passive"))
    )
    (net (code "167") (name "/Dout<24>") (class "Default")
      (node (ref "BKconnector") (pin "155") (pinfunction "A18_155") (pintype "passive"))
      (node (ref "P1") (pin "6") (pinfunction "6_6") (pintype "passive"))
    )
    (net (code "168") (name "/Dout<25>") (class "Default")
      (node (ref "BKconnector") (pin "157") (pinfunction "C11_157") (pintype "passive"))
      (node (ref "P1") (pin "5") (pinfunction "5_5") (pintype "passive"))
    )
    (net (code "169") (name "/Dout<26>") (class "Default")
      (node (ref "BKconnector") (pin "159") (pinfunction "A11_159") (pintype "passive"))
      (node (ref "P1") (pin "4") (pinfunction "4_4") (pintype "passive"))
    )
    (net (code "170") (name "/Dout<27>") (class "Default")
      (node (ref "BKconnector") (pin "156") (pinfunction "B18_156") (pintype "passive"))
      (node (ref "P1") (pin "3") (pinfunction "3_3") (pintype "passive"))
    )
    (net (code "171") (name "/Dout<28>") (class "Default")
      (node (ref "BKconnector") (pin "154") (pinfunction "A16_154") (pintype "passive"))
      (node (ref "P1") (pin "2") (pinfunction "2_2") (pintype "passive"))
    )
    (net (code "172") (name "/Dout<29>") (class "Default")
      (node (ref "BKconnector") (pin "152") (pinfunction "B16_152") (pintype "passive"))
      (node (ref "P1") (pin "1") (pinfunction "1_1") (pintype "passive"))
    )
    (net (code "173") (name "/Dout<30>") (class "Default")
      (node (ref "BKconnector") (pin "150") (pinfunction "A14_150") (pintype "passive"))
      (node (ref "P3") (pin "60") (pinfunction "60_60") (pintype "passive"))
    )
    (net (code "174") (name "/Dout<31>") (class "Default")
      (node (ref "BKconnector") (pin "148") (pinfunction "B14_148") (pintype "passive"))
      (node (ref "P3") (pin "59") (pinfunction "59_59") (pintype "passive"))
    )
    (net (code "175") (name "/Dout<32>") (class "Default")
      (node (ref "BKconnector") (pin "146") (pinfunction "A12_146") (pintype "passive"))
      (node (ref "P3") (pin "58") (pinfunction "58_58") (pintype "passive"))
    )
    (net (code "176") (name "/Dout<33>") (class "Default")
      (node (ref "BKconnector") (pin "144") (pinfunction "B12_144") (pintype "passive"))
      (node (ref "P3") (pin "57") (pinfunction "57_57") (pintype "passive"))
    )
    (net (code "177") (name "/Dout<34>") (class "Default")
      (node (ref "BKconnector") (pin "142") (pinfunction "A9_142") (pintype "passive"))
      (node (ref "P3") (pin "56") (pinfunction "56_56") (pintype "passive"))
    )
    (net (code "178") (name "/Dout<35>") (class "Default")
      (node (ref "BKconnector") (pin "140") (pinfunction "C9_140") (pintype "passive"))
      (node (ref "P3") (pin "55") (pinfunction "55_55") (pintype "passive"))
    )
    (net (code "179") (name "/Dout<36>") (class "Default")
      (node (ref "BKconnector") (pin "138") (pinfunction "A7_138") (pintype "passive"))
      (node (ref "P3") (pin "54") (pinfunction "54_54") (pintype "passive"))
    )
    (net (code "180") (name "/Dout<37>") (class "Default")
      (node (ref "BKconnector") (pin "134") (pinfunction "C7_134") (pintype "passive"))
      (node (ref "P3") (pin "53") (pinfunction "53_53") (pintype "passive"))
    )
    (net (code "181") (name "/Dout<38>") (class "Default")
      (node (ref "BKconnector") (pin "132") (pinfunction "A6_132") (pintype "passive"))
      (node (ref "P3") (pin "52") (pinfunction "52_52") (pintype "passive"))
    )
    (net (code "182") (name "/Dout<39>") (class "Default")
      (node (ref "BKconnector") (pin "130") (pinfunction "B6_130") (pintype "passive"))
      (node (ref "P3") (pin "51") (pinfunction "51_51") (pintype "passive"))
    )
    (net (code "183") (name "/Dout<40>") (class "Default")
      (node (ref "BKconnector") (pin "128") (pinfunction "C16_128") (pintype "passive"))
      (node (ref "P3") (pin "50") (pinfunction "50_50") (pintype "passive"))
    )
    (net (code "184") (name "/Dout<41>") (class "Default")
      (node (ref "BKconnector") (pin "126") (pinfunction "D15_126") (pintype "passive"))
      (node (ref "P3") (pin "49") (pinfunction "49_49") (pintype "passive"))
    )
    (net (code "185") (name "/Dout<42>") (class "Default")
      (node (ref "BKconnector") (pin "124") (pinfunction "C12_124") (pintype "passive"))
      (node (ref "P3") (pin "48") (pinfunction "48_48") (pintype "passive"))
    )
    (net (code "186") (name "/Dout<43>") (class "Default")
      (node (ref "BKconnector") (pin "122") (pinfunction "D11_122") (pintype "passive"))
      (node (ref "P2") (pin "59") (pinfunction "59_59") (pintype "passive"))
    )
    (net (code "187") (name "/Dout<44>") (class "Default")
      (node (ref "BKconnector") (pin "120") (pinfunction "C10_120") (pintype "passive"))
      (node (ref "P2") (pin "60") (pinfunction "60_60") (pintype "passive"))
    )
    (net (code "188") (name "/Dout<45>") (class "Default")
      (node (ref "BKconnector") (pin "118") (pinfunction "D10_118") (pintype "passive"))
      (node (ref "P2") (pin "57") (pinfunction "57_57") (pintype "passive"))
    )
    (net (code "189") (name "/Dout<46>") (class "Default")
      (node (ref "BKconnector") (pin "114") (pinfunction "C8_114") (pintype "passive"))
      (node (ref "P2") (pin "58") (pinfunction "58_58") (pintype "passive"))
    )
    (net (code "190") (name "/Dout<47>") (class "Default")
      (node (ref "BKconnector") (pin "112") (pinfunction "D9_112") (pintype "passive"))
      (node (ref "P2") (pin "55") (pinfunction "55_55") (pintype "passive"))
    )
    (net (code "191") (name "/Dout<48>") (class "Default")
      (node (ref "BKconnector") (pin "110") (pinfunction "R19_110") (pintype "passive"))
      (node (ref "P2") (pin "56") (pinfunction "56_56") (pintype "passive"))
    )
    (net (code "192") (name "/Dout<49>") (class "Default")
      (node (ref "BKconnector") (pin "108") (pinfunction "P18_108") (pintype "passive"))
      (node (ref "P2") (pin "53") (pinfunction "53_53") (pintype "passive"))
    )
    (net (code "193") (name "/Dout<50>") (class "Default")
      (node (ref "BKconnector") (pin "106") (pinfunction "M18_106") (pintype "passive"))
      (node (ref "P2") (pin "54") (pinfunction "54_54") (pintype "passive"))
    )
    (net (code "194") (name "/Dout<51>") (class "Default")
      (node (ref "BKconnector") (pin "104") (pinfunction "M17_104") (pintype "passive"))
      (node (ref "P2") (pin "51") (pinfunction "51_51") (pintype "passive"))
    )
    (net (code "195") (name "/Dout<52>") (class "Default")
      (node (ref "BKconnector") (pin "102") (pinfunction "N16_102") (pintype "passive"))
      (node (ref "P2") (pin "52") (pinfunction "52_52") (pintype "passive"))
    )
    (net (code "196") (name "/Dout<53>") (class "Default")
      (node (ref "BKconnector") (pin "100") (pinfunction "P17_100") (pintype "passive"))
      (node (ref "P2") (pin "49") (pinfunction "49_49") (pintype "passive"))
    )
    (net (code "197") (name "/Dout<54>") (class "Default")
      (node (ref "BKconnector") (pin "98") (pinfunction "T20_98") (pintype "passive"))
      (node (ref "P2") (pin "50") (pinfunction "50_50") (pintype "passive"))
    )
    (net (code "198") (name "/Dout<55>") (class "Default")
      (node (ref "BKconnector") (pin "96") (pinfunction "T19_96") (pintype "passive"))
      (node (ref "P2") (pin "47") (pinfunction "47_47") (pintype "passive"))
    )
    (net (code "199") (name "/Dout<56>") (class "Default")
      (node (ref "BKconnector") (pin "16") (pinfunction "G19_16") (pintype "passive"))
      (node (ref "P2") (pin "48") (pinfunction "48_48") (pintype "passive"))
    )
    (net (code "200") (name "/Dout<57>") (class "Default")
      (node (ref "BKconnector") (pin "18") (pinfunction "F20_18") (pintype "passive"))
      (node (ref "P2") (pin "45") (pinfunction "45_45") (pintype "passive"))
    )
    (net (code "201") (name "/Dout<58>") (class "Default")
      (node (ref "BKconnector") (pin "20") (pinfunction "H20_20") (pintype "passive"))
      (node (ref "P2") (pin "46") (pinfunction "46_46") (pintype "passive"))
    )
    (net (code "202") (name "/Dout<59>") (class "Default")
      (node (ref "BKconnector") (pin "22") (pinfunction "J19_22") (pintype "passive"))
      (node (ref "P2") (pin "43") (pinfunction "43_43") (pintype "passive"))
    )
    (net (code "203") (name "/Dout<60>") (class "Default")
      (node (ref "BKconnector") (pin "24") (pinfunction "D19_24") (pintype "passive"))
      (node (ref "P2") (pin "44") (pinfunction "44_44") (pintype "passive"))
    )
    (net (code "204") (name "/Dout<61>") (class "Default")
      (node (ref "BKconnector") (pin "26") (pinfunction "D20_26") (pintype "passive"))
      (node (ref "P2") (pin "41") (pinfunction "41_41") (pintype "passive"))
    )
    (net (code "205") (name "/Dout<62>") (class "Default")
      (node (ref "BKconnector") (pin "28") (pinfunction "F18_28") (pintype "passive"))
      (node (ref "P2") (pin "42") (pinfunction "42_42") (pintype "passive"))
    )
    (net (code "206") (name "/Dout<63>") (class "Default")
      (node (ref "BKconnector") (pin "30") (pinfunction "F19_30") (pintype "passive"))
      (node (ref "P2") (pin "39") (pinfunction "39_39") (pintype "passive"))
    )
    (net (code "207") (name "/Dout_test") (class "Default")
      (node (ref "BKconnector") (pin "32") (pinfunction "M16_32") (pintype "passive"))
      (node (ref "P3") (pin "47") (pinfunction "47_47") (pintype "passive"))
    )
    (net (code "208") (name "/EN_HFIR") (class "Default")
      (node (ref "P1") (pin "31") (pinfunction "31_31") (pintype "passive"))
      (node (ref "R061") (pin "1") (pinfunction "1_1") (pintype "passive"))
    )
    (net (code "209") (name "/EN_pseudo") (class "Default")
      (node (ref "P1") (pin "43") (pinfunction "43_43") (pintype "passive"))
      (node (ref "R033") (pin "1") (pinfunction "1_1") (pintype "passive"))
    )
    (net (code "210") (name "/EN_sensor") (class "Default")
      (node (ref "P1") (pin "42") (pinfunction "42_42") (pintype "passive"))
      (node (ref "R025") (pin "1") (pinfunction "1_1") (pintype "passive"))
    )
    (net (code "211") (name "/ESDVDD") (class "Default")
      (node (ref "P2") (pin "6") (pinfunction "6_6") (pintype "passive"))
    )
    (net (code "212") (name "/FPGAVDD") (class "Default")
      (node (ref "BKconnector") (pin "116") (pinfunction "+VCCO0_116") (pintype "passive"))
      (node (ref "BKconnector") (pin "136") (pinfunction "+VCCO0_136") (pintype "passive"))
      (node (ref "BKconnector") (pin "35") (pinfunction "+VCCO1_35") (pintype "passive"))
      (node (ref "BKconnector") (pin "55") (pinfunction "+VCCO1_55") (pintype "passive"))
      (node (ref "J_FPGAVDD") (pin "1") (pinfunction "1_1") (pintype "passive"))
    )
    (net (code "213") (name "/GMR_Sel0") (class "Default")
      (node (ref "R095") (pin "1") (pinfunction "1_1") (pintype "passive"))
      (node (ref "U0") (pin "17") (pinfunction "A0_17") (pintype "input"))
    )
    (net (code "214") (name "/GMR_Sel1") (class "Default")
      (node (ref "R097") (pin "1") (pinfunction "1_1") (pintype "passive"))
      (node (ref "U0") (pin "16") (pinfunction "A1_16") (pintype "input"))
    )
    (net (code "215") (name "/GMR_Sel2") (class "Default")
      (node (ref "R099") (pin "1") (pinfunction "1_1") (pintype "passive"))
      (node (ref "U0") (pin "15") (pinfunction "A2_15") (pintype "input"))
    )
    (net (code "216") (name "/GMR_Sel3") (class "Default")
      (node (ref "R101") (pin "1") (pinfunction "1_1") (pintype "passive"))
      (node (ref "U0") (pin "14") (pinfunction "A3_14") (pintype "input"))
    )
    (net (code "217") (name "/Gain2X") (class "Default")
      (node (ref "P1") (pin "38") (pinfunction "38_38") (pintype "passive"))
      (node (ref "R043") (pin "1") (pinfunction "1_1") (pintype "passive"))
    )
    (net (code "218") (name "/Iunit") (class "Default")
      (node (ref "J_Bin5") (pin "2") (pinfunction "2_2") (pintype "passive"))
      (node (ref "P3") (pin "8") (pinfunction "8_8") (pintype "passive"))
      (node (ref "R_Iunit") (pin "1") (pinfunction "1_1") (pintype "passive"))
    )
    (net (code "219") (name "/L_Sb") (class "Default")
      (node (ref "P1") (pin "46") (pinfunction "46_46") (pintype "passive"))
      (node (ref "R023") (pin "1") (pinfunction "1_1") (pintype "passive"))
    )
    (net (code "220") (name "/Mux_A0") (class "Default")
      (node (ref "J1") (pin "17") (pinfunction "17_17") (pintype "passive"))
      (node (ref "J_Mux1_A0") (pin "1") (pinfunction "1_1") (pintype "passive"))
      (node (ref "J_Mux2_A0") (pin "1") (pinfunction "1_1") (pintype "passive"))
      (node (ref "J_Mux3_A0") (pin "1") (pinfunction "1_1") (pintype "passive"))
      (node (ref "J_Mux4_A0") (pin "1") (pinfunction "1_1") (pintype "passive"))
      (node (ref "J_Mux5_A0") (pin "1") (pinfunction "1_1") (pintype "passive"))
      (node (ref "J_Mux6_A0") (pin "1") (pinfunction "1_1") (pintype "passive"))
      (node (ref "J_Mux7_A0") (pin "1") (pinfunction "1_1") (pintype "passive"))
    )
    (net (code "221") (name "/Mux_A1") (class "Default")
      (node (ref "J1") (pin "49") (pinfunction "49_49") (pintype "passive"))
      (node (ref "J_Mux1_A1") (pin "2") (pinfunction "2_2") (pintype "passive"))
      (node (ref "J_Mux2_A1") (pin "2") (pinfunction "2_2") (pintype "passive"))
      (node (ref "J_Mux3_A1") (pin "2") (pinfunction "2_2") (pintype "passive"))
      (node (ref "J_Mux4_A1") (pin "2") (pinfunction "2_2") (pintype "passive"))
      (node (ref "J_Mux5_A1") (pin "2") (pinfunction "2_2") (pintype "passive"))
      (node (ref "J_Mux6_A1") (pin "2") (pinfunction "2_2") (pintype "passive"))
      (node (ref "J_Mux7_A1") (pin "2") (pinfunction "2_2") (pintype "passive"))
    )
    (net (code "222") (name "/Mux_EN") (class "Default")
      (node (ref "J1") (pin "52") (pinfunction "52_52") (pintype "passive"))
      (node (ref "J_Mux1_EN") (pin "1") (pinfunction "1_1") (pintype "passive"))
      (node (ref "J_Mux2_EN") (pin "1") (pinfunction "1_1") (pintype "passive"))
      (node (ref "J_Mux3_EN") (pin "1") (pinfunction "1_1") (pintype "passive"))
      (node (ref "J_Mux4_EN") (pin "1") (pinfunction "1_1") (pintype "passive"))
      (node (ref "J_Mux5_EN") (pin "1") (pinfunction "1_1") (pintype "passive"))
      (node (ref "J_Mux6_EN") (pin "1") (pinfunction "1_1") (pintype "passive"))
      (node (ref "J_Mux7_EN") (pin "1") (pinfunction "1_1") (pintype "passive"))
    )
    (net (code "223") (name "/R1") (class "Default")
      (node (ref "J_R1") (pin "3") (pinfunction "3_3") (pintype "passive"))
      (node (ref "Jr1") (pin "1") (pinfunction "1_1") (pintype "passive"))
      (node (ref "P20") (pin "6") (pinfunction "6_6") (pintype "passive"))
    )
    (net (code "224") (name "/R2") (class "Default")
      (node (ref "J_R2") (pin "3") (pinfunction "3_3") (pintype "passive"))
      (node (ref "Jr2") (pin "1") (pinfunction "1_1") (pintype "passive"))
      (node (ref "P20") (pin "5") (pinfunction "5_5") (pintype "passive"))
    )
    (net (code "225") (name "/R3") (class "Default")
      (node (ref "J_R3") (pin "3") (pinfunction "3_3") (pintype "passive"))
      (node (ref "Jr3") (pin "1") (pinfunction "1_1") (pintype "passive"))
      (node (ref "P20") (pin "8") (pinfunction "8_8") (pintype "passive"))
    )
    (net (code "226") (name "/R4") (class "Default")
      (node (ref "J_R4") (pin "3") (pinfunction "3_3") (pintype "passive"))
      (node (ref "Jr4") (pin "1") (pinfunction "1_1") (pintype "passive"))
      (node (ref "P20") (pin "7") (pinfunction "7_7") (pintype "passive"))
    )
    (net (code "227") (name "/R5") (class "Default")
      (node (ref "J_R5") (pin "3") (pinfunction "3_3") (pintype "passive"))
      (node (ref "Jr5") (pin "1") (pinfunction "1_1") (pintype "passive"))
      (node (ref "P20") (pin "18") (pinfunction "18_18") (pintype "passive"))
    )
    (net (code "228") (name "/R6") (class "Default")
      (node (ref "J_R6") (pin "3") (pinfunction "3_3") (pintype "passive"))
      (node (ref "Jr6") (pin "1") (pinfunction "1_1") (pintype "passive"))
      (node (ref "P20") (pin "17") (pinfunction "17_17") (pintype "passive"))
    )
    (net (code "229") (name "/R7") (class "Default")
      (node (ref "J_R7") (pin "3") (pinfunction "3_3") (pintype "passive"))
      (node (ref "Jr7") (pin "1") (pinfunction "1_1") (pintype "passive"))
      (node (ref "P20") (pin "20") (pinfunction "20_20") (pintype "passive"))
    )
    (net (code "230") (name "/R8") (class "Default")
      (node (ref "J_R8") (pin "3") (pinfunction "3_3") (pintype "passive"))
      (node (ref "Jr8") (pin "1") (pinfunction "1_1") (pintype "passive"))
      (node (ref "P20") (pin "19") (pinfunction "19_19") (pintype "passive"))
    )
    (net (code "231") (name "/Rst_DSM") (class "Default")
      (node (ref "P1") (pin "30") (pinfunction "30_30") (pintype "passive"))
      (node (ref "R059") (pin "1") (pinfunction "1_1") (pintype "passive"))
    )
    (net (code "232") (name "/Rst_RS") (class "Default")
      (node (ref "P1") (pin "47") (pinfunction "47_47") (pintype "passive"))
      (node (ref "R021") (pin "1") (pinfunction "1_1") (pintype "passive"))
    )
    (net (code "233") (name "/Rst_SI_sensor") (class "Default")
      (node (ref "P1") (pin "50") (pinfunction "50_50") (pintype "passive"))
      (node (ref "R017") (pin "1") (pinfunction "1_1") (pintype "passive"))
    )
    (net (code "234") (name "/Rst_SI_stripe") (class "Default")
      (node (ref "P3") (pin "37") (pinfunction "37_37") (pintype "passive"))
      (node (ref "R049") (pin "1") (pinfunction "1_1") (pintype "passive"))
    )
    (net (code "235") (name "/Rst_counter") (class "Default")
      (node (ref "P1") (pin "28") (pinfunction "28_28") (pintype "passive"))
      (node (ref "R067") (pin "1") (pinfunction "1_1") (pintype "passive"))
    )
    (net (code "236") (name "/Rst_stripe") (class "Default")
      (node (ref "P3") (pin "38") (pinfunction "38_38") (pintype "passive"))
      (node (ref "R051") (pin "1") (pinfunction "1_1") (pintype "passive"))
    )
    (net (code "237") (name "/SH_LDb_global") (class "Default")
      (node (ref "P1") (pin "26") (pinfunction "26_26") (pintype "passive"))
      (node (ref "R071") (pin "1") (pinfunction "1_1") (pintype "passive"))
    )
    (net (code "238") (name "/SH_LDb_test") (class "Default")
      (node (ref "P3") (pin "45") (pinfunction "45_45") (pintype "passive"))
      (node (ref "R073") (pin "1") (pinfunction "1_1") (pintype "passive"))
    )
    (net (code "239") (name "/SO_EN0") (class "Default")
      (node (ref "P1") (pin "19") (pinfunction "19_19") (pintype "passive"))
      (node (ref "R068") (pin "2") (pinfunction "2_2") (pintype "passive"))
    )
    (net (code "240") (name "/SO_EN1") (class "Default")
      (node (ref "P1") (pin "20") (pinfunction "20_20") (pintype "passive"))
      (node (ref "R070") (pin "2") (pinfunction "2_2") (pintype "passive"))
    )
    (net (code "241") (name "/SO_EN2") (class "Default")
      (node (ref "P1") (pin "17") (pinfunction "17_17") (pintype "passive"))
      (node (ref "R072") (pin "2") (pinfunction "2_2") (pintype "passive"))
    )
    (net (code "242") (name "/SO_EN3") (class "Default")
      (node (ref "P1") (pin "18") (pinfunction "18_18") (pintype "passive"))
      (node (ref "R074") (pin "2") (pinfunction "2_2") (pintype "passive"))
    )
    (net (code "243") (name "/SO_ctrl0") (class "Default")
      (node (ref "P3") (pin "41") (pinfunction "41_41") (pintype "passive"))
      (node (ref "R060") (pin "2") (pinfunction "2_2") (pintype "passive"))
    )
    (net (code "244") (name "/SO_ctrl1") (class "Default")
      (node (ref "P3") (pin "42") (pinfunction "42_42") (pintype "passive"))
      (node (ref "R062") (pin "2") (pinfunction "2_2") (pintype "passive"))
    )
    (net (code "245") (name "/SO_ctrl2") (class "Default")
      (node (ref "P3") (pin "43") (pinfunction "43_43") (pintype "passive"))
      (node (ref "R064") (pin "2") (pinfunction "2_2") (pintype "passive"))
    )
    (net (code "246") (name "/SO_ctrl3") (class "Default")
      (node (ref "P3") (pin "44") (pinfunction "44_44") (pintype "passive"))
      (node (ref "R066") (pin "2") (pinfunction "2_2") (pintype "passive"))
    )
    (net (code "247") (name "/SO_test") (class "Default")
      (node (ref "BKconnector") (pin "50") (pinfunction "N20_50") (pintype "passive"))
      (node (ref "P3") (pin "46") (pinfunction "46_46") (pintype "passive"))
      (node (ref "R050") (pin "1") (pinfunction "1_1") (pintype "passive"))
    )
    (net (code "248") (name "/SVDD") (class "Default")
      (node (ref "P2") (pin "3") (pinfunction "3_3") (pintype "passive"))
      (node (ref "P2") (pin "4") (pinfunction "4_4") (pintype "passive"))
    )
    (net (code "249") (name "/Sout0") (class "Default")
      (node (ref "BKconnector") (pin "42") (pinfunction "U20_42") (pintype "passive"))
      (node (ref "P1") (pin "21") (pinfunction "21_21") (pintype "passive"))
      (node (ref "R042") (pin "1") (pinfunction "1_1") (pintype "passive"))
    )
    (net (code "250") (name "/Sout1") (class "Default")
      (node (ref "BKconnector") (pin "44") (pinfunction "U22_44") (pintype "passive"))
      (node (ref "P1") (pin "22") (pinfunction "22_22") (pintype "passive"))
      (node (ref "R044") (pin "1") (pinfunction "1_1") (pintype "passive"))
    )
    (net (code "251") (name "/Sout2") (class "Default")
      (node (ref "BKconnector") (pin "46") (pinfunction "R20_46") (pintype "passive"))
      (node (ref "P1") (pin "23") (pinfunction "23_23") (pintype "passive"))
      (node (ref "R046") (pin "1") (pinfunction "1_1") (pintype "passive"))
    )
    (net (code "252") (name "/Sout3") (class "Default")
      (node (ref "BKconnector") (pin "48") (pinfunction "R22_48") (pintype "passive"))
      (node (ref "P1") (pin "24") (pinfunction "24_24") (pintype "passive"))
      (node (ref "R048") (pin "1") (pinfunction "1_1") (pintype "passive"))
    )
    (net (code "253") (name "/VDDD") (class "Default")
      (node (ref "J_VDDD") (pin "2") (pinfunction "2_2") (pintype "passive"))
    )
    (net (code "254") (name "/VDD_Bias") (class "Default")
      (node (ref "P2") (pin "9") (pinfunction "9_9") (pintype "passive"))
      (node (ref "P3") (pin "7") (pinfunction "7_7") (pintype "passive"))
    )
    (net (code "255") (name "/VDD_DSM") (class "Default")
      (node (ref "P1") (pin "36") (pinfunction "36_36") (pintype "passive"))
      (node (ref "P3") (pin "5") (pinfunction "5_5") (pintype "passive"))
    )
    (net (code "256") (name "/VDD_IA") (class "Default")
      (node (ref "P1") (pin "37") (pinfunction "37_37") (pintype "passive"))
      (node (ref "P3") (pin "6") (pinfunction "6_6") (pintype "passive"))
    )
    (net (code "258") (name "/VH") (class "Default")
      (node (ref "J_VH") (pin "2") (pinfunction "2_2") (pintype "passive"))
      (node (ref "J_Vfield") (pin "2") (pinfunction "2_2") (pintype "passive"))
      (node (ref "P2") (pin "2") (pinfunction "2_2") (pintype "passive"))
    )
    (net (code "259") (name "/VH0") (class "Default")
      (node (ref "J_VH") (pin "1") (pinfunction "1_1") (pintype "passive"))
    )
    (net (code "260") (name "/VIA+0_buf") (class "Default")
      (node (ref "AI_Mux1") (pin "5") (pinfunction "S2A_5") (pintype "passive"))
      (node (ref "AI_Mux1") (pin "6") (pinfunction "S3A_6") (pintype "passive"))
      (node (ref "J_Aout6") (pin "2") (pinfunction "2_2") (pintype "passive"))
    )
    (net (code "261") (name "/VIA+5_buf") (class "Default")
      (node (ref "AI_Mux2") (pin "5") (pinfunction "S2A_5") (pintype "passive"))
      (node (ref "J_Aout7") (pin "2") (pinfunction "2_2") (pintype "passive"))
    )
    (net (code "262") (name "/VIA+10_buf") (class "Default")
      (node (ref "AI_Mux3") (pin "5") (pinfunction "S2A_5") (pintype "passive"))
      (node (ref "J_Aout8") (pin "2") (pinfunction "2_2") (pintype "passive"))
    )
    (net (code "263") (name "/VIA+15_buf") (class "Default")
      (node (ref "AI_Mux2") (pin "6") (pinfunction "S3A_6") (pintype "passive"))
      (node (ref "AI_Mux4") (pin "5") (pinfunction "S2A_5") (pintype "passive"))
      (node (ref "J_Aout9") (pin "2") (pinfunction "2_2") (pintype "passive"))
    )
    (net (code "264") (name "/VIA+20_buf") (class "Default")
      (node (ref "AI_Mux5") (pin "5") (pinfunction "S2A_5") (pintype "passive"))
      (node (ref "J_Aout10") (pin "2") (pinfunction "2_2") (pintype "passive"))
    )
    (net (code "265") (name "/VIA+25_buf") (class "Default")
      (node (ref "AI_Mux6") (pin "5") (pinfunction "S2A_5") (pintype "passive"))
      (node (ref "J_Aout11") (pin "2") (pinfunction "2_2") (pintype "passive"))
    )
    (net (code "266") (name "/VIA+31_buf") (class "Default")
      (node (ref "AI_Mux3") (pin "6") (pinfunction "S3A_6") (pintype "passive"))
      (node (ref "AI_Mux7") (pin "5") (pinfunction "S2A_5") (pintype "passive"))
      (node (ref "J_Aout12") (pin "2") (pinfunction "2_2") (pintype "passive"))
    )
    (net (code "267") (name "/VIA+<0>") (class "Default")
      (node (ref "J_Ain6") (pin "2") (pinfunction "2_2") (pintype "passive"))
      (node (ref "P2") (pin "10") (pinfunction "10_10") (pintype "passive"))
    )
    (net (code "268") (name "/VIA+<5>") (class "Default")
      (node (ref "J_Ain7") (pin "2") (pinfunction "2_2") (pintype "passive"))
      (node (ref "P2") (pin "14") (pinfunction "14_14") (pintype "passive"))
    )
    (net (code "269") (name "/VIA+<10>") (class "Default")
      (node (ref "J_Ain8") (pin "2") (pinfunction "2_2") (pintype "passive"))
      (node (ref "P2") (pin "18") (pinfunction "18_18") (pintype "passive"))
    )
    (net (code "270") (name "/VIA+<15>") (class "Default")
      (node (ref "J_Ain9") (pin "2") (pinfunction "2_2") (pintype "passive"))
      (node (ref "P2") (pin "22") (pinfunction "22_22") (pintype "passive"))
    )
    (net (code "271") (name "/VIA+<20>") (class "Default")
      (node (ref "J_Ain10") (pin "2") (pinfunction "2_2") (pintype "passive"))
      (node (ref "P2") (pin "11") (pinfunction "11_11") (pintype "passive"))
    )
    (net (code "272") (name "/VIA+<25>") (class "Default")
      (node (ref "J_Ain11") (pin "2") (pinfunction "2_2") (pintype "passive"))
      (node (ref "P2") (pin "15") (pinfunction "15_15") (pintype "passive"))
    )
    (net (code "273") (name "/VIA+<31>") (class "Default")
      (node (ref "J_Ain12") (pin "2") (pinfunction "2_2") (pintype "passive"))
      (node (ref "P2") (pin "19") (pinfunction "19_19") (pintype "passive"))
    )
    (net (code "274") (name "/VIA+_test") (class "Default")
      (node (ref "J_Ain20") (pin "2") (pinfunction "2_2") (pintype "passive"))
      (node (ref "P3") (pin "15") (pinfunction "15_15") (pintype "passive"))
    )
    (net (code "275") (name "/VIA+test_buf") (class "Default")
      (node (ref "AI_Mux7") (pin "6") (pinfunction "S3A_6") (pintype "passive"))
      (node (ref "J_Aout20") (pin "2") (pinfunction "2_2") (pintype "passive"))
    )
    (net (code "276") (name "/VIA-0_buf") (class "Default")
      (node (ref "AI_Mux1") (pin "11") (pinfunction "S3B_11") (pintype "passive"))
      (node (ref "AI_Mux1") (pin "12") (pinfunction "S2B_12") (pintype "passive"))
      (node (ref "J_Bout6") (pin "2") (pinfunction "2_2") (pintype "passive"))
    )
    (net (code "277") (name "/VIA-5_buf") (class "Default")
      (node (ref "AI_Mux2") (pin "12") (pinfunction "S2B_12") (pintype "passive"))
      (node (ref "J_Bout7") (pin "2") (pinfunction "2_2") (pintype "passive"))
    )
    (net (code "278") (name "/VIA-10_buf") (class "Default")
      (node (ref "AI_Mux3") (pin "12") (pinfunction "S2B_12") (pintype "passive"))
      (node (ref "J_Bout8") (pin "2") (pinfunction "2_2") (pintype "passive"))
    )
    (net (code "279") (name "/VIA-15_buf") (class "Default")
      (node (ref "AI_Mux2") (pin "11") (pinfunction "S3B_11") (pintype "passive"))
      (node (ref "AI_Mux4") (pin "12") (pinfunction "S2B_12") (pintype "passive"))
      (node (ref "J_Bout9") (pin "2") (pinfunction "2_2") (pintype "passive"))
    )
    (net (code "280") (name "/VIA-20_buf") (class "Default")
      (node (ref "AI_Mux5") (pin "12") (pinfunction "S2B_12") (pintype "passive"))
      (node (ref "J_Bout10") (pin "2") (pinfunction "2_2") (pintype "passive"))
    )
    (net (code "281") (name "/VIA-25_buf") (class "Default")
      (node (ref "AI_Mux6") (pin "12") (pinfunction "S2B_12") (pintype "passive"))
      (node (ref "J_Bout11") (pin "2") (pinfunction "2_2") (pintype "passive"))
    )
    (net (code "282") (name "/VIA-31_buf") (class "Default")
      (node (ref "AI_Mux3") (pin "11") (pinfunction "S3B_11") (pintype "passive"))
      (node (ref "AI_Mux7") (pin "12") (pinfunction "S2B_12") (pintype "passive"))
      (node (ref "J_Bout12") (pin "2") (pinfunction "2_2") (pintype "passive"))
    )
    (net (code "283") (name "/VIA-<0>") (class "Default")
      (node (ref "J_Bin6") (pin "2") (pinfunction "2_2") (pintype "passive"))
      (node (ref "P2") (pin "12") (pinfunction "12_12") (pintype "passive"))
    )
    (net (code "284") (name "/VIA-<5>") (class "Default")
      (node (ref "J_Bin7") (pin "2") (pinfunction "2_2") (pintype "passive"))
      (node (ref "P2") (pin "16") (pinfunction "16_16") (pintype "passive"))
    )
    (net (code "285") (name "/VIA-<10>") (class "Default")
      (node (ref "J_Bin8") (pin "2") (pinfunction "2_2") (pintype "passive"))
      (node (ref "P2") (pin "20") (pinfunction "20_20") (pintype "passive"))
    )
    (net (code "286") (name "/VIA-<15>") (class "Default")
      (node (ref "J_Bin9") (pin "2") (pinfunction "2_2") (pintype "passive"))
      (node (ref "P2") (pin "24") (pinfunction "24_24") (pintype "passive"))
    )
    (net (code "287") (name "/VIA-<20>") (class "Default")
      (node (ref "J_Bin10") (pin "2") (pinfunction "2_2") (pintype "passive"))
      (node (ref "P2") (pin "13") (pinfunction "13_13") (pintype "passive"))
    )
    (net (code "288") (name "/VIA-<25>") (class "Default")
      (node (ref "J_Bin11") (pin "2") (pinfunction "2_2") (pintype "passive"))
      (node (ref "P2") (pin "17") (pinfunction "17_17") (pintype "passive"))
    )
    (net (code "289") (name "/VIA-<31>") (class "Default")
      (node (ref "J_Bin12") (pin "2") (pinfunction "2_2") (pintype "passive"))
      (node (ref "P2") (pin "21") (pinfunction "21_21") (pintype "passive"))
    )
    (net (code "290") (name "/VIA-_test") (class "Default")
      (node (ref "J_Bin20") (pin "2") (pinfunction "2_2") (pintype "passive"))
      (node (ref "P3") (pin "16") (pinfunction "16_16") (pintype "passive"))
    )
    (net (code "291") (name "/VIA-test_buf") (class "Default")
      (node (ref "AI_Mux7") (pin "11") (pinfunction "S3B_11") (pintype "passive"))
      (node (ref "J_Bout20") (pin "2") (pinfunction "2_2") (pintype "passive"))
    )
    (net (code "292") (name "/VIA_cmi+_test") (class "Default")
      (node (ref "J_Ain23") (pin "2") (pinfunction "2_2") (pintype "passive"))
      (node (ref "P3") (pin "13") (pinfunction "13_13") (pintype "passive"))
    )
    (net (code "293") (name "/VIA_cmi+test_buf") (class "Default")
      (node (ref "AI_Mux7") (pin "7") (pinfunction "S4A_7") (pintype "passive"))
      (node (ref "J_Aout23") (pin "2") (pinfunction "2_2") (pintype "passive"))
    )
    (net (code "294") (name "/VIA_cmi-_test") (class "Default")
      (node (ref "J_Bin23") (pin "2") (pinfunction "2_2") (pintype "passive"))
      (node (ref "P3") (pin "14") (pinfunction "14_14") (pintype "passive"))
    )
    (net (code "295") (name "/VIA_cmi-test_buf") (class "Default")
      (node (ref "AI_Mux7") (pin "10") (pinfunction "S4B_10") (pintype "passive"))
      (node (ref "J_Bout23") (pin "2") (pinfunction "2_2") (pintype "passive"))
    )
    (net (code "296") (name "/VSSS") (class "Default")
      (node (ref "Cd02") (pin "2") (pinfunction "2_2") (pintype "passive"))
      (node (ref "Cd04") (pin "2") (pinfunction "2_2") (pintype "passive"))
      (node (ref "VSSS") (pin "1") (pinfunction "X_1") (pintype "passive"))
    )
    (net (code "297") (name "/V_Iunit") (class "Default")
      (node (ref "J_Bout5") (pin "2") (pinfunction "2_2") (pintype "passive"))
    )
    (net (code "298") (name "/V_fH") (class "Default")
      (node (ref "V_fH") (pin "1") (pinfunction "X_1") (pintype "passive"))
    )
    (net (code "299") (name "/Vac+0_buf") (class "Default")
      (node (ref "AI_Mux1") (pin "7") (pinfunction "S4A_7") (pintype "passive"))
      (node (ref "AI_Mux4") (pin "6") (pinfunction "S3A_6") (pintype "passive"))
      (node (ref "J_Aout13") (pin "2") (pinfunction "2_2") (pintype "passive"))
    )
    (net (code "300") (name "/Vac+15_buf") (class "Default")
      (node (ref "AI_Mux2") (pin "7") (pinfunction "S4A_7") (pintype "passive"))
      (node (ref "AI_Mux5") (pin "6") (pinfunction "S3A_6") (pintype "passive"))
      (node (ref "J_Aout14") (pin "2") (pinfunction "2_2") (pintype "passive"))
    )
    (net (code "301") (name "/Vac+31_buf") (class "Default")
      (node (ref "AI_Mux3") (pin "7") (pinfunction "S4A_7") (pintype "passive"))
      (node (ref "AI_Mux6") (pin "6") (pinfunction "S3A_6") (pintype "passive"))
      (node (ref "J_Aout15") (pin "2") (pinfunction "2_2") (pintype "passive"))
    )
    (net (code "302") (name "/Vac+<0>") (class "Default")
      (node (ref "J_Ain13") (pin "2") (pinfunction "2_2") (pintype "passive"))
      (node (ref "P3") (pin "25") (pinfunction "25_25") (pintype "passive"))
    )
    (net (code "303") (name "/Vac+<1>") (class "Default")
      (node (ref "J_Ain14") (pin "2") (pinfunction "2_2") (pintype "passive"))
      (node (ref "P3") (pin "23") (pinfunction "23_23") (pintype "passive"))
    )
    (net (code "304") (name "/Vac+<2>") (class "Default")
      (node (ref "J_Ain15") (pin "2") (pinfunction "2_2") (pintype "passive"))
      (node (ref "P3") (pin "21") (pinfunction "21_21") (pintype "passive"))
    )
    (net (code "305") (name "/Vac+_test") (class "Default")
      (node (ref "J_Ain21") (pin "2") (pinfunction "2_2") (pintype "passive"))
      (node (ref "P3") (pin "17") (pinfunction "17_17") (pintype "passive"))
    )
    (net (code "306") (name "/Vac+test_buf") (class "Default")
      (node (ref "J_Aout21") (pin "2") (pinfunction "2_2") (pintype "passive"))
    )
    (net (code "307") (name "/Vac-0_buf") (class "Default")
      (node (ref "AI_Mux1") (pin "10") (pinfunction "S4B_10") (pintype "passive"))
      (node (ref "AI_Mux4") (pin "11") (pinfunction "S3B_11") (pintype "passive"))
      (node (ref "J_Bout13") (pin "2") (pinfunction "2_2") (pintype "passive"))
    )
    (net (code "308") (name "/Vac-15_buf") (class "Default")
      (node (ref "AI_Mux2") (pin "10") (pinfunction "S4B_10") (pintype "passive"))
      (node (ref "AI_Mux5") (pin "11") (pinfunction "S3B_11") (pintype "passive"))
      (node (ref "J_Bout14") (pin "2") (pinfunction "2_2") (pintype "passive"))
    )
    (net (code "309") (name "/Vac-31_buf") (class "Default")
      (node (ref "AI_Mux3") (pin "10") (pinfunction "S4B_10") (pintype "passive"))
      (node (ref "AI_Mux6") (pin "11") (pinfunction "S3B_11") (pintype "passive"))
      (node (ref "J_Bout15") (pin "2") (pinfunction "2_2") (pintype "passive"))
    )
    (net (code "310") (name "/Vac-<0>") (class "Default")
      (node (ref "J_Bin13") (pin "2") (pinfunction "2_2") (pintype "passive"))
      (node (ref "P3") (pin "26") (pinfunction "26_26") (pintype "passive"))
    )
    (net (code "311") (name "/Vac-<1>") (class "Default")
      (node (ref "J_Bin14") (pin "2") (pinfunction "2_2") (pintype "passive"))
      (node (ref "P3") (pin "24") (pinfunction "24_24") (pintype "passive"))
    )
    (net (code "312") (name "/Vac-<2>") (class "Default")
      (node (ref "J_Bin15") (pin "2") (pinfunction "2_2") (pintype "passive"))
      (node (ref "P3") (pin "22") (pinfunction "22_22") (pintype "passive"))
    )
    (net (code "313") (name "/Vac-_test") (class "Default")
      (node (ref "J_Bin21") (pin "2") (pinfunction "2_2") (pintype "passive"))
      (node (ref "P3") (pin "18") (pinfunction "18_18") (pintype "passive"))
    )
    (net (code "314") (name "/Vac-test_buf") (class "Default")
      (node (ref "J_Bout21") (pin "2") (pinfunction "2_2") (pintype "passive"))
    )
    (net (code "315") (name "/Vatt1") (class "Default")
      (node (ref "J_att1") (pin "1") (pinfunction "1_1") (pintype "passive"))
    )
    (net (code "316") (name "/Vatt2") (class "Default")
      (node (ref "J_att2") (pin "1") (pinfunction "1_1") (pintype "passive"))
    )
    (net (code "317") (name "/Vatt3") (class "Default")
      (node (ref "J_att3") (pin "1") (pinfunction "1_1") (pintype "passive"))
    )
    (net (code "318") (name "/Vatt4") (class "Default")
      (node (ref "J_att4") (pin "1") (pinfunction "1_1") (pintype "passive"))
    )
    (net (code "319") (name "/Vbias") (class "Default")
      (node (ref "J1") (pin "22") (pinfunction "22_22") (pintype "passive"))
      (node (ref "J_Vin") (pin "2") (pinfunction "2_2") (pintype "passive"))
    )
    (net (code "320") (name "/VbiasL") (class "Default")
      (node (ref "J_Vbias") (pin "1") (pinfunction "1_1") (pintype "passive"))
      (node (ref "J_Vin") (pin "1") (pinfunction "1_1") (pintype "passive"))
      (node (ref "P2") (pin "7") (pinfunction "7_7") (pintype "passive"))
    )
    (net (code "321") (name "/VbiasS") (class "Default")
      (node (ref "J_Vbias") (pin "3") (pinfunction "3_3") (pintype "passive"))
      (node (ref "J_Vin") (pin "3") (pinfunction "3_3") (pintype "passive"))
      (node (ref "P2") (pin "8") (pinfunction "8_8") (pintype "passive"))
    )
    (net (code "322") (name "/Vbias_1") (class "Default")
      (node (ref "Vbias2") (pin "1") (pinfunction "X_1") (pintype "passive"))
    )
    (net (code "323") (name "/Vcmi") (class "Default")
      (node (ref "P3") (pin "1") (pinfunction "1_1") (pintype "passive"))
    )
    (net (code "324") (name "/Vcmo") (class "Default")
      (node (ref "P3") (pin "2") (pinfunction "2_2") (pintype "passive"))
    )
    (net (code "325") (name "/Vfield") (class "Default")
      (node (ref "J1") (pin "21") (pinfunction "21_21") (pintype "passive"))
      (node (ref "J_Vfield") (pin "1") (pinfunction "1_1") (pintype "passive"))
    )
    (net (code "326") (name "/Vin+0_buf") (class "Default")
      (node (ref "AI_Mux1") (pin "4") (pinfunction "S1A_4") (pintype "passive"))
      (node (ref "J_Aout2") (pin "2") (pinfunction "2_2") (pintype "passive"))
    )
    (net (code "327") (name "/Vin+5_buf") (class "Default")
      (node (ref "AI_Mux2") (pin "4") (pinfunction "S1A_4") (pintype "passive"))
      (node (ref "J_Bout2") (pin "2") (pinfunction "2_2") (pintype "passive"))
    )
    (net (code "328") (name "/Vin+10_buf") (class "Default")
      (node (ref "AI_Mux3") (pin "4") (pinfunction "S1A_4") (pintype "passive"))
      (node (ref "J_Aout3") (pin "2") (pinfunction "2_2") (pintype "passive"))
    )
    (net (code "329") (name "/Vin+15_buf") (class "Default")
      (node (ref "AI_Mux4") (pin "4") (pinfunction "S1A_4") (pintype "passive"))
      (node (ref "J_Bout3") (pin "2") (pinfunction "2_2") (pintype "passive"))
    )
    (net (code "330") (name "/Vin+20_buf") (class "Default")
      (node (ref "AI_Mux5") (pin "4") (pinfunction "S1A_4") (pintype "passive"))
      (node (ref "J_Aout4") (pin "2") (pinfunction "2_2") (pintype "passive"))
    )
    (net (code "331") (name "/Vin+25_buf") (class "Default")
      (node (ref "AI_Mux6") (pin "4") (pinfunction "S1A_4") (pintype "passive"))
      (node (ref "J_Bout4") (pin "2") (pinfunction "2_2") (pintype "passive"))
    )
    (net (code "332") (name "/Vin+31_buf") (class "Default")
      (node (ref "AI_Mux7") (pin "4") (pinfunction "S1A_4") (pintype "passive"))
      (node (ref "J_Aout5") (pin "2") (pinfunction "2_2") (pintype "passive"))
    )
    (net (code "333") (name "/Vin+<0>") (class "Default")
      (node (ref "J_Ain2") (pin "2") (pinfunction "2_2") (pintype "passive"))
      (node (ref "J_R2") (pin "2") (pinfunction "2_2") (pintype "passive"))
      (node (ref "P1") (pin "60") (pinfunction "60_60") (pintype "passive"))
    )
    (net (code "334") (name "/Vin+<5>") (class "Default")
      (node (ref "J_Bin2") (pin "2") (pinfunction "2_2") (pintype "passive"))
      (node (ref "J_R3") (pin "2") (pinfunction "2_2") (pintype "passive"))
      (node (ref "P1") (pin "57") (pinfunction "57_57") (pintype "passive"))
    )
    (net (code "335") (name "/Vin+<10>") (class "Default")
      (node (ref "J_Ain3") (pin "2") (pinfunction "2_2") (pintype "passive"))
      (node (ref "J_R4") (pin "2") (pinfunction "2_2") (pintype "passive"))
      (node (ref "P1") (pin "58") (pinfunction "58_58") (pintype "passive"))
    )
    (net (code "336") (name "/Vin+<15>") (class "Default")
      (node (ref "J_Bin3") (pin "2") (pinfunction "2_2") (pintype "passive"))
      (node (ref "J_R5") (pin "2") (pinfunction "2_2") (pintype "passive"))
      (node (ref "P1") (pin "55") (pinfunction "55_55") (pintype "passive"))
    )
    (net (code "337") (name "/Vin+<20>") (class "Default")
      (node (ref "J_Ain4") (pin "2") (pinfunction "2_2") (pintype "passive"))
      (node (ref "J_R6") (pin "2") (pinfunction "2_2") (pintype "passive"))
      (node (ref "P1") (pin "56") (pinfunction "56_56") (pintype "passive"))
    )
    (net (code "338") (name "/Vin+<25>") (class "Default")
      (node (ref "J_Bin4") (pin "2") (pinfunction "2_2") (pintype "passive"))
      (node (ref "J_R7") (pin "2") (pinfunction "2_2") (pintype "passive"))
      (node (ref "P1") (pin "53") (pinfunction "53_53") (pintype "passive"))
    )
    (net (code "339") (name "/Vin+<31>") (class "Default")
      (node (ref "J_Ain5") (pin "2") (pinfunction "2_2") (pintype "passive"))
      (node (ref "J_R8") (pin "2") (pinfunction "2_2") (pintype "passive"))
      (node (ref "P1") (pin "54") (pinfunction "54_54") (pintype "passive"))
    )
    (net (code "340") (name "/Vin+_test") (class "Default")
      (node (ref "J_Ain19") (pin "2") (pinfunction "2_2") (pintype "passive"))
      (node (ref "P3") (pin "11") (pinfunction "11_11") (pintype "passive"))
    )
    (net (code "341") (name "/Vin+test_buf") (class "Default")
      (node (ref "J_Aout19") (pin "2") (pinfunction "2_2") (pintype "passive"))
    )
    (net (code "342") (name "/Vin-1") (class "Default")
      (node (ref "J_Bin1") (pin "2") (pinfunction "2_2") (pintype "passive"))
      (node (ref "J_R1") (pin "2") (pinfunction "2_2") (pintype "passive"))
      (node (ref "P1") (pin "59") (pinfunction "59_59") (pintype "passive"))
    )
    (net (code "343") (name "/Vin-_buf") (class "Default")
      (node (ref "AI_Mux1") (pin "13") (pinfunction "S1B_13") (pintype "passive"))
      (node (ref "AI_Mux2") (pin "13") (pinfunction "S1B_13") (pintype "passive"))
      (node (ref "AI_Mux3") (pin "13") (pinfunction "S1B_13") (pintype "passive"))
      (node (ref "AI_Mux4") (pin "13") (pinfunction "S1B_13") (pintype "passive"))
      (node (ref "AI_Mux5") (pin "13") (pinfunction "S1B_13") (pintype "passive"))
      (node (ref "AI_Mux6") (pin "13") (pinfunction "S1B_13") (pintype "passive"))
      (node (ref "AI_Mux7") (pin "13") (pinfunction "S1B_13") (pintype "passive"))
      (node (ref "J_Bout1") (pin "2") (pinfunction "2_2") (pintype "passive"))
    )
    (net (code "344") (name "/Vin-_test") (class "Default")
      (node (ref "J_Bin19") (pin "2") (pinfunction "2_2") (pintype "passive"))
      (node (ref "P3") (pin "12") (pinfunction "12_12") (pintype "passive"))
    )
    (net (code "345") (name "/Vin-test_buf") (class "Default")
      (node (ref "J_Bout19") (pin "2") (pinfunction "2_2") (pintype "passive"))
    )
    (net (code "346") (name "/Vout+0_buf") (class "Default")
      (node (ref "AI_Mux4") (pin "7") (pinfunction "S4A_7") (pintype "passive"))
      (node (ref "J_Aout16") (pin "2") (pinfunction "2_2") (pintype "passive"))
    )
    (net (code "347") (name "/Vout+15_buf") (class "Default")
      (node (ref "AI_Mux5") (pin "7") (pinfunction "S4A_7") (pintype "passive"))
      (node (ref "J_Aout17") (pin "2") (pinfunction "2_2") (pintype "passive"))
    )
    (net (code "348") (name "/Vout+31_buf") (class "Default")
      (node (ref "AI_Mux6") (pin "7") (pinfunction "S4A_7") (pintype "passive"))
      (node (ref "J_Aout18") (pin "2") (pinfunction "2_2") (pintype "passive"))
    )
    (net (code "349") (name "/Vout+<0>") (class "Default")
      (node (ref "J_Ain16") (pin "2") (pinfunction "2_2") (pintype "passive"))
      (node (ref "P3") (pin "31") (pinfunction "31_31") (pintype "passive"))
    )
    (net (code "350") (name "/Vout+<1>") (class "Default")
      (node (ref "J_Ain17") (pin "2") (pinfunction "2_2") (pintype "passive"))
      (node (ref "P3") (pin "29") (pinfunction "29_29") (pintype "passive"))
    )
    (net (code "351") (name "/Vout+<2>") (class "Default")
      (node (ref "J_Ain18") (pin "2") (pinfunction "2_2") (pintype "passive"))
      (node (ref "P3") (pin "27") (pinfunction "27_27") (pintype "passive"))
    )
    (net (code "352") (name "/Vout+_test") (class "Default")
      (node (ref "J_Ain22") (pin "2") (pinfunction "2_2") (pintype "passive"))
      (node (ref "P3") (pin "19") (pinfunction "19_19") (pintype "passive"))
    )
    (net (code "353") (name "/Vout+test_buf") (class "Default")
      (node (ref "J_Aout22") (pin "2") (pinfunction "2_2") (pintype "passive"))
    )
    (net (code "354") (name "/Vout-0_buf") (class "Default")
      (node (ref "AI_Mux4") (pin "10") (pinfunction "S4B_10") (pintype "passive"))
      (node (ref "J_Bout16") (pin "2") (pinfunction "2_2") (pintype "passive"))
    )
    (net (code "355") (name "/Vout-15_buf") (class "Default")
      (node (ref "AI_Mux5") (pin "10") (pinfunction "S4B_10") (pintype "passive"))
      (node (ref "J_Bout17") (pin "2") (pinfunction "2_2") (pintype "passive"))
    )
    (net (code "356") (name "/Vout-31_buf") (class "Default")
      (node (ref "AI_Mux6") (pin "10") (pinfunction "S4B_10") (pintype "passive"))
      (node (ref "J_Bout18") (pin "2") (pinfunction "2_2") (pintype "passive"))
    )
    (net (code "357") (name "/Vout-<0>") (class "Default")
      (node (ref "J_Bin16") (pin "2") (pinfunction "2_2") (pintype "passive"))
      (node (ref "P3") (pin "32") (pinfunction "32_32") (pintype "passive"))
    )
    (net (code "358") (name "/Vout-<1>") (class "Default")
      (node (ref "J_Bin17") (pin "2") (pinfunction "2_2") (pintype "passive"))
      (node (ref "P3") (pin "30") (pinfunction "30_30") (pintype "passive"))
    )
    (net (code "359") (name "/Vout-<2>") (class "Default")
      (node (ref "J_Bin18") (pin "2") (pinfunction "2_2") (pintype "passive"))
      (node (ref "P3") (pin "28") (pinfunction "28_28") (pintype "passive"))
    )
    (net (code "360") (name "/Vout-_test") (class "Default")
      (node (ref "J_Bin22") (pin "2") (pinfunction "2_2") (pintype "passive"))
      (node (ref "P3") (pin "20") (pinfunction "20_20") (pintype "passive"))
    )
    (net (code "361") (name "/Vout-test_buf") (class "Default")
      (node (ref "J_Bout22") (pin "2") (pinfunction "2_2") (pintype "passive"))
    )
    (net (code "362") (name "/Vref+") (class "Default")
      (node (ref "P3") (pin "3") (pinfunction "3_3") (pintype "passive"))
    )
    (net (code "363") (name "/Vref-") (class "Default")
      (node (ref "P3") (pin "4") (pinfunction "4_4") (pintype "passive"))
    )
    (net (code "364") (name "/Vstripe") (class "Default")
      (node (ref "J_Ain1") (pin "2") (pinfunction "2_2") (pintype "passive"))
      (node (ref "P2") (pin "1") (pinfunction "1_1") (pintype "passive"))
    )
    (net (code "365") (name "/Vstripe_buf") (class "Default")
      (node (ref "J1") (pin "68") (pinfunction "68_68") (pintype "passive"))
      (node (ref "J_Aout1") (pin "2") (pinfunction "2_2") (pintype "passive"))
    )
    (net (code "366") (name "/fLO") (class "Default")
      (node (ref "J_demod") (pin "1") (pinfunction "1_1") (pintype "passive"))
      (node (ref "R029") (pin "1") (pinfunction "1_1") (pintype "passive"))
    )
    (net (code "367") (name "GND") (class "Default")
      (node (ref "AI_Mux1") (pin "15") (pinfunction "GND_15") (pintype "passive"))
      (node (ref "AI_Mux1") (pin "3") (pinfunction "VSS_3") (pintype "passive"))
      (node (ref "AI_Mux2") (pin "15") (pinfunction "GND_15") (pintype "passive"))
      (node (ref "AI_Mux2") (pin "3") (pinfunction "VSS_3") (pintype "passive"))
      (node (ref "AI_Mux3") (pin "15") (pinfunction "GND_15") (pintype "passive"))
      (node (ref "AI_Mux3") (pin "3") (pinfunction "VSS_3") (pintype "passive"))
      (node (ref "AI_Mux4") (pin "15") (pinfunction "GND_15") (pintype "passive"))
      (node (ref "AI_Mux4") (pin "3") (pinfunction "VSS_3") (pintype "passive"))
      (node (ref "AI_Mux5") (pin "15") (pinfunction "GND_15") (pintype "passive"))
      (node (ref "AI_Mux5") (pin "3") (pinfunction "VSS_3") (pintype "passive"))
      (node (ref "AI_Mux6") (pin "15") (pinfunction "GND_15") (pintype "passive"))
      (node (ref "AI_Mux6") (pin "3") (pinfunction "VSS_3") (pintype "passive"))
      (node (ref "AI_Mux7") (pin "15") (pinfunction "GND_15") (pintype "passive"))
      (node (ref "AI_Mux7") (pin "3") (pinfunction "VSS_3") (pintype "passive"))
      (node (ref "C_AI1") (pin "2") (pinfunction "2_2") (pintype "passive"))
      (node (ref "C_AI1b") (pin "2") (pinfunction "2_2") (pintype "passive"))
      (node (ref "C_AI2") (pin "2") (pinfunction "2_2") (pintype "passive"))
      (node (ref "C_AI2b") (pin "2") (pinfunction "2_2") (pintype "passive"))
      (node (ref "C_AI3") (pin "2") (pinfunction "2_2") (pintype "passive"))
      (node (ref "C_AI3b") (pin "2") (pinfunction "2_2") (pintype "passive"))
      (node (ref "C_AI4") (pin "2") (pinfunction "2_2") (pintype "passive"))
      (node (ref "C_AI4b") (pin "2") (pinfunction "2_2") (pintype "passive"))
      (node (ref "C_AI5") (pin "2") (pinfunction "2_2") (pintype "passive"))
      (node (ref "C_AI5b") (pin "2") (pinfunction "2_2") (pintype "passive"))
      (node (ref "C_AI6") (pin "2") (pinfunction "2_2") (pintype "passive"))
      (node (ref "C_AI6b") (pin "2") (pinfunction "2_2") (pintype "passive"))
      (node (ref "C_AI7") (pin "2") (pinfunction "2_2") (pintype "passive"))
      (node (ref "C_AI7b") (pin "2") (pinfunction "2_2") (pintype "passive"))
      (node (ref "Cd01") (pin "2") (pinfunction "2_2") (pintype "passive"))
      (node (ref "Cd02") (pin "1") (pinfunction "1_1") (pintype "passive"))
      (node (ref "Cd03") (pin "1") (pinfunction "1_1") (pintype "passive"))
      (node (ref "Cd04") (pin "1") (pinfunction "1_1") (pintype "passive"))
      (node (ref "Cd51") (pin "2") (pinfunction "2_2") (pintype "passive"))
      (node (ref "Cd52") (pin "2") (pinfunction "2_2") (pintype "passive"))
      (node (ref "Cd53") (pin "2") (pinfunction "2_2") (pintype "passive"))
      (node (ref "Cd54") (pin "2") (pinfunction "2_2") (pintype "passive"))
      (node (ref "Cd55") (pin "2") (pinfunction "2_2") (pintype "passive"))
      (node (ref "Cd56") (pin "2") (pinfunction "2_2") (pintype "passive"))
      (node (ref "Cd57") (pin "2") (pinfunction "2_2") (pintype "passive"))
      (node (ref "Cd58") (pin "2") (pinfunction "2_2") (pintype "passive"))
      (node (ref "Cd59") (pin "2") (pinfunction "2_2") (pintype "passive"))
      (node (ref "Cd60") (pin "2") (pinfunction "2_2") (pintype "passive"))
      (node (ref "Cd61") (pin "2") (pinfunction "2_2") (pintype "passive"))
      (node (ref "Cd62") (pin "2") (pinfunction "2_2") (pintype "passive"))
      (node (ref "Cd63") (pin "2") (pinfunction "2_2") (pintype "passive"))
      (node (ref "Cd64") (pin "2") (pinfunction "2_2") (pintype "passive"))
      (node (ref "Cd65") (pin "2") (pinfunction "2_2") (pintype "passive"))
      (node (ref "Cd66") (pin "2") (pinfunction "2_2") (pintype "passive"))
      (node (ref "FB1") (pin "1") (pinfunction "1_1") (pintype "passive"))
      (node (ref "H1") (pin "1") (pintype "passive"))
      (node (ref "H2") (pin "1") (pintype "passive"))
      (node (ref "H6") (pin "1") (pintype "passive"))
      (node (ref "H7") (pin "1") (pintype "passive"))
      (node (ref "H8") (pin "1") (pintype "passive"))
      (node (ref "J1") (pin "24") (pinfunction "24_24") (pintype "passive"))
      (node (ref "J1") (pin "27") (pinfunction "27_27") (pintype "passive"))
      (node (ref "J1") (pin "29") (pinfunction "29_29") (pintype "passive"))
      (node (ref "J1") (pin "32") (pinfunction "32_32") (pintype "passive"))
      (node (ref "J1") (pin "34") (pinfunction "34_34") (pintype "passive"))
      (node (ref "J1") (pin "54") (pinfunction "54_54") (pintype "passive"))
      (node (ref "J1") (pin "55") (pinfunction "55_55") (pintype "passive"))
      (node (ref "J1") (pin "56") (pinfunction "56_56") (pintype "passive"))
      (node (ref "J1") (pin "59") (pinfunction "59_59") (pintype "passive"))
      (node (ref "J1") (pin "62") (pinfunction "62_62") (pintype "passive"))
      (node (ref "J1") (pin "64") (pinfunction "64_64") (pintype "passive"))
      (node (ref "J1") (pin "67") (pinfunction "67_67") (pintype "passive"))
      (node (ref "J_GMR_EN") (pin "1") (pinfunction "1_1") (pintype "passive"))
      (node (ref "P1") (pin "34") (pinfunction "34_34") (pintype "passive"))
      (node (ref "P1") (pin "51") (pinfunction "51_51") (pintype "passive"))
      (node (ref "P1") (pin "52") (pinfunction "52_52") (pintype "passive"))
      (node (ref "P2") (pin "26") (pinfunction "26_26") (pintype "passive"))
      (node (ref "P2") (pin "5") (pinfunction "5_5") (pintype "passive"))
      (node (ref "P3") (pin "10") (pinfunction "10_10") (pintype "passive"))
      (node (ref "P3") (pin "33") (pinfunction "33_33") (pintype "passive"))
      (node (ref "P3") (pin "40") (pinfunction "40_40") (pintype "passive"))
      (node (ref "P3") (pin "9") (pinfunction "9_9") (pintype "passive"))
      (node (ref "RC1") (pin "1") (pinfunction "1_1") (pintype "passive"))
      (node (ref "RC10") (pin "1") (pinfunction "1_1") (pintype "passive"))
      (node (ref "RC2") (pin "1") (pinfunction "1_1") (pintype "passive"))
      (node (ref "RC3") (pin "1") (pinfunction "1_1") (pintype "passive"))
      (node (ref "RC4") (pin "1") (pinfunction "1_1") (pintype "passive"))
      (node (ref "RC5") (pin "1") (pinfunction "1_1") (pintype "passive"))
      (node (ref "RC6") (pin "1") (pinfunction "1_1") (pintype "passive"))
      (node (ref "RC7") (pin "1") (pinfunction "1_1") (pintype "passive"))
      (node (ref "RC8") (pin "1") (pinfunction "1_1") (pintype "passive"))
      (node (ref "RC9") (pin "1") (pinfunction "1_1") (pintype "passive"))
      (node (ref "R_Iunit") (pin "2") (pinfunction "2_2") (pintype "passive"))
      (node (ref "Rr1") (pin "2") (pinfunction "2_2") (pintype "passive"))
      (node (ref "Rr2") (pin "2") (pinfunction "2_2") (pintype "passive"))
      (node (ref "Rr3") (pin "2") (pinfunction "2_2") (pintype "passive"))
      (node (ref "Rr4") (pin "2") (pinfunction "2_2") (pintype "passive"))
      (node (ref "Rr5") (pin "2") (pinfunction "2_2") (pintype "passive"))
      (node (ref "Rr6") (pin "2") (pinfunction "2_2") (pintype "passive"))
      (node (ref "Rr7") (pin "2") (pinfunction "2_2") (pintype "passive"))
      (node (ref "Rr8") (pin "2") (pinfunction "2_2") (pintype "passive"))
      (node (ref "U0") (pin "12") (pinfunction "GND_12") (pintype "power_in"))
      (node (ref "U0") (pin "27") (pinfunction "VSS_27") (pintype "power_in"))
      (node (ref "U0") (pin "28") (pinfunction "D_28") (pintype "passive"))
      (node (ref "VDDD") (pin "2") (pinfunction "Y_2") (pintype "passive"))
      (node (ref "VSSS") (pin "2") (pinfunction "Y_2") (pintype "passive"))
      (node (ref "V_demod") (pin "2") (pinfunction "Y_2") (pintype "passive"))
      (node (ref "V_fH") (pin "2") (pinfunction "Y_2") (pintype "passive"))
      (node (ref "Vbias") (pin "2") (pinfunction "Y_2") (pintype "passive"))
      (node (ref "Vbias2") (pin "2") (pinfunction "Y_2") (pintype "passive"))
    )
    (net (code "368") (name "Net-(AI_Mux1-A0)") (class "Default")
      (node (ref "AI_Mux1") (pin "1") (pinfunction "A0_1") (pintype "passive"))
      (node (ref "J_Mux1_A0") (pin "2") (pinfunction "2_2") (pintype "passive"))
    )
    (net (code "369") (name "Net-(AI_Mux1-A1)") (class "Default")
      (node (ref "AI_Mux1") (pin "16") (pinfunction "A1_16") (pintype "passive"))
      (node (ref "J_Mux1_A1") (pin "1") (pinfunction "1_1") (pintype "passive"))
    )
    (net (code "370") (name "Net-(AI_Mux1-DA)") (class "Default")
      (node (ref "AI_Mux1") (pin "8") (pinfunction "DA_8") (pintype "passive"))
      (node (ref "R_AI1") (pin "2") (pinfunction "2_2") (pintype "passive"))
    )
    (net (code "371") (name "Net-(AI_Mux1-DB)") (class "Default")
      (node (ref "AI_Mux1") (pin "9") (pinfunction "DB_9") (pintype "passive"))
      (node (ref "R_AI1b") (pin "1") (pinfunction "1_1") (pintype "passive"))
    )
    (net (code "372") (name "Net-(AI_Mux1-EN)") (class "Default")
      (node (ref "AI_Mux1") (pin "2") (pinfunction "EN_2") (pintype "passive"))
      (node (ref "J_Mux1_EN") (pin "2") (pinfunction "2_2") (pintype "passive"))
    )
    (net (code "373") (name "Net-(AI_Mux2-A0)") (class "Default")
      (node (ref "AI_Mux2") (pin "1") (pinfunction "A0_1") (pintype "passive"))
      (node (ref "J_Mux2_A0") (pin "2") (pinfunction "2_2") (pintype "passive"))
    )
    (net (code "374") (name "Net-(AI_Mux2-A1)") (class "Default")
      (node (ref "AI_Mux2") (pin "16") (pinfunction "A1_16") (pintype "passive"))
      (node (ref "J_Mux2_A1") (pin "1") (pinfunction "1_1") (pintype "passive"))
    )
    (net (code "375") (name "Net-(AI_Mux2-DA)") (class "Default")
      (node (ref "AI_Mux2") (pin "8") (pinfunction "DA_8") (pintype "passive"))
      (node (ref "R_AI2") (pin "2") (pinfunction "2_2") (pintype "passive"))
    )
    (net (code "376") (name "Net-(AI_Mux2-DB)") (class "Default")
      (node (ref "AI_Mux2") (pin "9") (pinfunction "DB_9") (pintype "passive"))
      (node (ref "R_AI2b") (pin "1") (pinfunction "1_1") (pintype "passive"))
    )
    (net (code "377") (name "Net-(AI_Mux2-EN)") (class "Default")
      (node (ref "AI_Mux2") (pin "2") (pinfunction "EN_2") (pintype "passive"))
      (node (ref "J_Mux2_EN") (pin "2") (pinfunction "2_2") (pintype "passive"))
    )
    (net (code "378") (name "Net-(AI_Mux3-A0)") (class "Default")
      (node (ref "AI_Mux3") (pin "1") (pinfunction "A0_1") (pintype "passive"))
      (node (ref "J_Mux3_A0") (pin "2") (pinfunction "2_2") (pintype "passive"))
    )
    (net (code "379") (name "Net-(AI_Mux3-A1)") (class "Default")
      (node (ref "AI_Mux3") (pin "16") (pinfunction "A1_16") (pintype "passive"))
      (node (ref "J_Mux3_A1") (pin "1") (pinfunction "1_1") (pintype "passive"))
    )
    (net (code "380") (name "Net-(AI_Mux3-DA)") (class "Default")
      (node (ref "AI_Mux3") (pin "8") (pinfunction "DA_8") (pintype "passive"))
      (node (ref "R_AI3") (pin "2") (pinfunction "2_2") (pintype "passive"))
    )
    (net (code "381") (name "Net-(AI_Mux3-DB)") (class "Default")
      (node (ref "AI_Mux3") (pin "9") (pinfunction "DB_9") (pintype "passive"))
      (node (ref "R_AI3b") (pin "1") (pinfunction "1_1") (pintype "passive"))
    )
    (net (code "382") (name "Net-(AI_Mux3-EN)") (class "Default")
      (node (ref "AI_Mux3") (pin "2") (pinfunction "EN_2") (pintype "passive"))
      (node (ref "J_Mux3_EN") (pin "2") (pinfunction "2_2") (pintype "passive"))
    )
    (net (code "383") (name "Net-(AI_Mux4-A0)") (class "Default")
      (node (ref "AI_Mux4") (pin "1") (pinfunction "A0_1") (pintype "passive"))
      (node (ref "J_Mux4_A0") (pin "2") (pinfunction "2_2") (pintype "passive"))
    )
    (net (code "384") (name "Net-(AI_Mux4-A1)") (class "Default")
      (node (ref "AI_Mux4") (pin "16") (pinfunction "A1_16") (pintype "passive"))
      (node (ref "J_Mux4_A1") (pin "1") (pinfunction "1_1") (pintype "passive"))
    )
    (net (code "385") (name "Net-(AI_Mux4-DA)") (class "Default")
      (node (ref "AI_Mux4") (pin "8") (pinfunction "DA_8") (pintype "passive"))
      (node (ref "R_AI4") (pin "2") (pinfunction "2_2") (pintype "passive"))
    )
    (net (code "386") (name "Net-(AI_Mux4-DB)") (class "Default")
      (node (ref "AI_Mux4") (pin "9") (pinfunction "DB_9") (pintype "passive"))
      (node (ref "R_AI4b") (pin "1") (pinfunction "1_1") (pintype "passive"))
    )
    (net (code "387") (name "Net-(AI_Mux4-EN)") (class "Default")
      (node (ref "AI_Mux4") (pin "2") (pinfunction "EN_2") (pintype "passive"))
      (node (ref "J_Mux4_EN") (pin "2") (pinfunction "2_2") (pintype "passive"))
    )
    (net (code "388") (name "Net-(AI_Mux5-A0)") (class "Default")
      (node (ref "AI_Mux5") (pin "1") (pinfunction "A0_1") (pintype "passive"))
      (node (ref "J_Mux5_A0") (pin "2") (pinfunction "2_2") (pintype "passive"))
    )
    (net (code "389") (name "Net-(AI_Mux5-A1)") (class "Default")
      (node (ref "AI_Mux5") (pin "16") (pinfunction "A1_16") (pintype "passive"))
      (node (ref "J_Mux5_A1") (pin "1") (pinfunction "1_1") (pintype "passive"))
    )
    (net (code "390") (name "Net-(AI_Mux5-DA)") (class "Default")
      (node (ref "AI_Mux5") (pin "8") (pinfunction "DA_8") (pintype "passive"))
      (node (ref "R_AI5") (pin "2") (pinfunction "2_2") (pintype "passive"))
    )
    (net (code "391") (name "Net-(AI_Mux5-DB)") (class "Default")
      (node (ref "AI_Mux5") (pin "9") (pinfunction "DB_9") (pintype "passive"))
      (node (ref "R_AI5b") (pin "1") (pinfunction "1_1") (pintype "passive"))
    )
    (net (code "392") (name "Net-(AI_Mux5-EN)") (class "Default")
      (node (ref "AI_Mux5") (pin "2") (pinfunction "EN_2") (pintype "passive"))
      (node (ref "J_Mux5_EN") (pin "2") (pinfunction "2_2") (pintype "passive"))
    )
    (net (code "393") (name "Net-(AI_Mux6-A0)") (class "Default")
      (node (ref "AI_Mux6") (pin "1") (pinfunction "A0_1") (pintype "passive"))
      (node (ref "J_Mux6_A0") (pin "2") (pinfunction "2_2") (pintype "passive"))
    )
    (net (code "394") (name "Net-(AI_Mux6-A1)") (class "Default")
      (node (ref "AI_Mux6") (pin "16") (pinfunction "A1_16") (pintype "passive"))
      (node (ref "J_Mux6_A1") (pin "1") (pinfunction "1_1") (pintype "passive"))
    )
    (net (code "395") (name "Net-(AI_Mux6-DA)") (class "Default")
      (node (ref "AI_Mux6") (pin "8") (pinfunction "DA_8") (pintype "passive"))
      (node (ref "R_AI6") (pin "2") (pinfunction "2_2") (pintype "passive"))
    )
    (net (code "396") (name "Net-(AI_Mux6-DB)") (class "Default")
      (node (ref "AI_Mux6") (pin "9") (pinfunction "DB_9") (pintype "passive"))
      (node (ref "R_AI6b") (pin "1") (pinfunction "1_1") (pintype "passive"))
    )
    (net (code "397") (name "Net-(AI_Mux6-EN)") (class "Default")
      (node (ref "AI_Mux6") (pin "2") (pinfunction "EN_2") (pintype "passive"))
      (node (ref "J_Mux6_EN") (pin "2") (pinfunction "2_2") (pintype "passive"))
    )
    (net (code "398") (name "Net-(AI_Mux7-A0)") (class "Default")
      (node (ref "AI_Mux7") (pin "1") (pinfunction "A0_1") (pintype "passive"))
      (node (ref "J_Mux7_A0") (pin "2") (pinfunction "2_2") (pintype "passive"))
    )
    (net (code "399") (name "Net-(AI_Mux7-A1)") (class "Default")
      (node (ref "AI_Mux7") (pin "16") (pinfunction "A1_16") (pintype "passive"))
      (node (ref "J_Mux7_A1") (pin "1") (pinfunction "1_1") (pintype "passive"))
    )
    (net (code "400") (name "Net-(AI_Mux7-DA)") (class "Default")
      (node (ref "AI_Mux7") (pin "8") (pinfunction "DA_8") (pintype "passive"))
      (node (ref "R_AI7") (pin "2") (pinfunction "2_2") (pintype "passive"))
    )
    (net (code "401") (name "Net-(AI_Mux7-DB)") (class "Default")
      (node (ref "AI_Mux7") (pin "9") (pinfunction "DB_9") (pintype "passive"))
      (node (ref "R_AI7b") (pin "1") (pinfunction "1_1") (pintype "passive"))
    )
    (net (code "402") (name "Net-(AI_Mux7-EN)") (class "Default")
      (node (ref "AI_Mux7") (pin "2") (pinfunction "EN_2") (pintype "passive"))
      (node (ref "J_Mux7_EN") (pin "2") (pinfunction "2_2") (pintype "passive"))
    )
    (net (code "403") (name "Net-(BKconnector-+1.8VDD)") (class "Default")
      (node (ref "BKconnector") (pin "87") (pinfunction "+1.8VDD_87") (pintype "passive"))
      (node (ref "J_FPGAVDD") (pin "2") (pinfunction "2_2") (pintype "passive"))
    )
    (net (code "404") (name "Net-(BKconnector-A21)") (class "Default")
      (node (ref "BKconnector") (pin "75") (pinfunction "A21_75") (pintype "passive"))
      (node (ref "R075") (pin "2") (pinfunction "2_2") (pintype "passive"))
    )
    (net (code "405") (name "Net-(BKconnector-B21)") (class "Default")
      (node (ref "BKconnector") (pin "71") (pinfunction "B21_71") (pintype "passive"))
      (node (ref "R071") (pin "2") (pinfunction "2_2") (pintype "passive"))
    )
    (net (code "406") (name "Net-(BKconnector-B22)") (class "Default")
      (node (ref "BKconnector") (pin "73") (pinfunction "B22_73") (pintype "passive"))
      (node (ref "R073") (pin "2") (pinfunction "2_2") (pintype "passive"))
    )
    (net (code "407") (name "Net-(BKconnector-C20)") (class "Default")
      (node (ref "BKconnector") (pin "72") (pinfunction "C20_72") (pintype "passive"))
      (node (ref "R072") (pin "1") (pinfunction "1_1") (pintype "passive"))
    )
    (net (code "408") (name "Net-(BKconnector-C22)") (class "Default")
      (node (ref "BKconnector") (pin "74") (pinfunction "C22_74") (pintype "passive"))
      (node (ref "R074") (pin "1") (pinfunction "1_1") (pintype "passive"))
    )
    (net (code "409") (name "Net-(BKconnector-D21)") (class "Default")
      (node (ref "BKconnector") (pin "67") (pinfunction "D21_67") (pintype "passive"))
      (node (ref "R067") (pin "2") (pinfunction "2_2") (pintype "passive"))
    )
    (net (code "410") (name "Net-(BKconnector-D22)") (class "Default")
      (node (ref "BKconnector") (pin "69") (pinfunction "D22_69") (pintype "passive"))
      (node (ref "R069") (pin "2") (pinfunction "2_2") (pintype "passive"))
    )
    (net (code "411") (name "Net-(BKconnector-E20)") (class "Default")
      (node (ref "BKconnector") (pin "68") (pinfunction "E20_68") (pintype "passive"))
      (node (ref "R068") (pin "1") (pinfunction "1_1") (pintype "passive"))
    )
    (net (code "412") (name "Net-(BKconnector-E22)") (class "Default")
      (node (ref "BKconnector") (pin "70") (pinfunction "E22_70") (pintype "passive"))
      (node (ref "R070") (pin "1") (pinfunction "1_1") (pintype "passive"))
    )
    (net (code "413") (name "Net-(BKconnector-F16)") (class "Default")
      (node (ref "BKconnector") (pin "23") (pinfunction "F16_23") (pintype "passive"))
      (node (ref "R023") (pin "2") (pinfunction "2_2") (pintype "passive"))
    )
    (net (code "414") (name "Net-(BKconnector-F17)") (class "Default")
      (node (ref "BKconnector") (pin "25") (pinfunction "F17_25") (pintype "passive"))
      (node (ref "R025") (pin "2") (pinfunction "2_2") (pintype "passive"))
    )
    (net (code "415") (name "Net-(BKconnector-F21)") (class "Default")
      (node (ref "BKconnector") (pin "63") (pinfunction "F21_63") (pintype "passive"))
      (node (ref "R063") (pin "2") (pinfunction "2_2") (pintype "passive"))
    )
    (net (code "416") (name "Net-(BKconnector-F22)") (class "Default")
      (node (ref "BKconnector") (pin "65") (pinfunction "F22_65") (pintype "passive"))
      (node (ref "R065") (pin "2") (pinfunction "2_2") (pintype "passive"))
    )
    (net (code "417") (name "Net-(BKconnector-G16)") (class "Default")
      (node (ref "BKconnector") (pin "15") (pinfunction "G16_15") (pintype "passive"))
      (node (ref "R015") (pin "2") (pinfunction "2_2") (pintype "passive"))
    )
    (net (code "418") (name "Net-(BKconnector-G17)") (class "Default")
      (node (ref "BKconnector") (pin "17") (pinfunction "G17_17") (pintype "passive"))
      (node (ref "R017") (pin "2") (pinfunction "2_2") (pintype "passive"))
    )
    (net (code "419") (name "Net-(BKconnector-G20)") (class "Default")
      (node (ref "BKconnector") (pin "64") (pinfunction "G20_64") (pintype "passive"))
      (node (ref "R064") (pin "1") (pinfunction "1_1") (pintype "passive"))
    )
    (net (code "420") (name "Net-(BKconnector-G22)") (class "Default")
      (node (ref "BKconnector") (pin "66") (pinfunction "G22_66") (pintype "passive"))
      (node (ref "R066") (pin "1") (pinfunction "1_1") (pintype "passive"))
    )
    (net (code "421") (name "Net-(BKconnector-H18)") (class "Default")
      (node (ref "BKconnector") (pin "21") (pinfunction "H18_21") (pintype "passive"))
      (node (ref "R021") (pin "2") (pinfunction "2_2") (pintype "passive"))
    )
    (net (code "422") (name "Net-(BKconnector-H19)") (class "Default")
      (node (ref "BKconnector") (pin "19") (pinfunction "H19_19") (pintype "passive"))
      (node (ref "R019") (pin "2") (pinfunction "2_2") (pintype "passive"))
    )
    (net (code "423") (name "Net-(BKconnector-H21)") (class "Default")
      (node (ref "BKconnector") (pin "59") (pinfunction "H21_59") (pintype "passive"))
      (node (ref "R059") (pin "2") (pinfunction "2_2") (pintype "passive"))
    )
    (net (code "424") (name "Net-(BKconnector-H22)") (class "Default")
      (node (ref "BKconnector") (pin "61") (pinfunction "H22_61") (pintype "passive"))
      (node (ref "R061") (pin "2") (pinfunction "2_2") (pintype "passive"))
    )
    (net (code "425") (name "Net-(BKconnector-J16)") (class "Default")
      (node (ref "BKconnector") (pin "33") (pinfunction "J16_33") (pintype "passive"))
      (node (ref "R033") (pin "2") (pinfunction "2_2") (pintype "passive"))
    )
    (net (code "426") (name "Net-(BKconnector-K16)") (class "Default")
      (node (ref "BKconnector") (pin "31") (pinfunction "K16_31") (pintype "passive"))
      (node (ref "R031") (pin "2") (pinfunction "2_2") (pintype "passive"))
    )
    (net (code "427") (name "Net-(BKconnector-K17)") (class "Default")
      (node (ref "BKconnector") (pin "29") (pinfunction "K17_29") (pintype "passive"))
      (node (ref "R029") (pin "2") (pinfunction "2_2") (pintype "passive"))
    )
    (net (code "428") (name "Net-(BKconnector-K21)") (class "Default")
      (node (ref "BKconnector") (pin "60") (pinfunction "K21_60") (pintype "passive"))
      (node (ref "R060") (pin "1") (pinfunction "1_1") (pintype "passive"))
    )
    (net (code "429") (name "Net-(BKconnector-K22)") (class "Default")
      (node (ref "BKconnector") (pin "62") (pinfunction "K22_62") (pintype "passive"))
      (node (ref "R062") (pin "1") (pinfunction "1_1") (pintype "passive"))
    )
    (net (code "430") (name "Net-(BKconnector-L20)") (class "Default")
      (node (ref "BKconnector") (pin "53") (pinfunction "L20_53") (pintype "passive"))
      (node (ref "R053") (pin "2") (pinfunction "2_2") (pintype "passive"))
    )
    (net (code "431") (name "Net-(BKconnector-L22)") (class "Default")
      (node (ref "BKconnector") (pin "57") (pinfunction "L22_57") (pintype "passive"))
      (node (ref "R057") (pin "2") (pinfunction "2_2") (pintype "passive"))
    )
    (net (code "432") (name "Net-(BKconnector-M20)") (class "Default")
      (node (ref "BKconnector") (pin "54") (pinfunction "M20_54") (pintype "passive"))
      (node (ref "R054") (pin "1") (pinfunction "1_1") (pintype "passive"))
    )
    (net (code "433") (name "Net-(BKconnector-M21)") (class "Default")
      (node (ref "BKconnector") (pin "49") (pinfunction "M21_49") (pintype "passive"))
      (node (ref "R049") (pin "2") (pinfunction "2_2") (pintype "passive"))
    )
    (net (code "434") (name "Net-(BKconnector-M22)") (class "Default")
      (node (ref "BKconnector") (pin "51") (pinfunction "M22_51") (pintype "passive"))
      (node (ref "R051") (pin "2") (pinfunction "2_2") (pintype "passive"))
    )
    (net (code "435") (name "Net-(BKconnector-T21)") (class "Default")
      (node (ref "BKconnector") (pin "41") (pinfunction "T21_41") (pintype "passive"))
      (node (ref "R041") (pin "2") (pinfunction "2_2") (pintype "passive"))
    )
    (net (code "436") (name "Net-(BKconnector-T22)") (class "Default")
      (node (ref "BKconnector") (pin "43") (pinfunction "T22_43") (pintype "passive"))
      (node (ref "R043") (pin "2") (pinfunction "2_2") (pintype "passive"))
    )
    (net (code "437") (name "Net-(BKconnector-U19)") (class "Default")
      (node (ref "BKconnector") (pin "99") (pinfunction "U19_99") (pintype "passive"))
      (node (ref "R099") (pin "2") (pinfunction "2_2") (pintype "passive"))
    )
    (net (code "438") (name "Net-(BKconnector-V20)") (class "Default")
      (node (ref "BKconnector") (pin "101") (pinfunction "V20_101") (pintype "passive"))
      (node (ref "R101") (pin "2") (pinfunction "2_2") (pintype "passive"))
    )
    (net (code "439") (name "Net-(BKconnector-V21)") (class "Default")
      (node (ref "BKconnector") (pin "37") (pinfunction "V21_37") (pintype "passive"))
      (node (ref "R037") (pin "2") (pinfunction "2_2") (pintype "passive"))
    )
    (net (code "440") (name "Net-(BKconnector-W20)") (class "Default")
      (node (ref "BKconnector") (pin "95") (pinfunction "W20_95") (pintype "passive"))
      (node (ref "R095") (pin "2") (pinfunction "2_2") (pintype "passive"))
    )
    (net (code "441") (name "Net-(BKconnector-W22)") (class "Default")
      (node (ref "BKconnector") (pin "97") (pinfunction "W22_97") (pintype "passive"))
      (node (ref "R097") (pin "2") (pinfunction "2_2") (pintype "passive"))
    )
    (net (code "442") (name "Net-(J_R1-Pad1)") (class "Default")
      (node (ref "J_R1") (pin "1") (pinfunction "1_1") (pintype "passive"))
      (node (ref "Rr1") (pin "1") (pinfunction "1_1") (pintype "passive"))
    )
    (net (code "443") (name "Net-(J_R2-Pad1)") (class "Default")
      (node (ref "J_R2") (pin "1") (pinfunction "1_1") (pintype "passive"))
      (node (ref "Rr2") (pin "1") (pinfunction "1_1") (pintype "passive"))
    )
    (net (code "444") (name "Net-(J_R3-Pad1)") (class "Default")
      (node (ref "J_R3") (pin "1") (pinfunction "1_1") (pintype "passive"))
      (node (ref "Rr3") (pin "1") (pinfunction "1_1") (pintype "passive"))
    )
    (net (code "445") (name "Net-(J_R4-Pad1)") (class "Default")
      (node (ref "J_R4") (pin "1") (pinfunction "1_1") (pintype "passive"))
      (node (ref "Rr4") (pin "1") (pinfunction "1_1") (pintype "passive"))
    )
    (net (code "446") (name "Net-(J_R5-Pad1)") (class "Default")
      (node (ref "J_R5") (pin "1") (pinfunction "1_1") (pintype "passive"))
      (node (ref "Rr5") (pin "1") (pinfunction "1_1") (pintype "passive"))
    )
    (net (code "447") (name "Net-(J_R6-Pad1)") (class "Default")
      (node (ref "J_R6") (pin "1") (pinfunction "1_1") (pintype "passive"))
      (node (ref "Rr6") (pin "1") (pinfunction "1_1") (pintype "passive"))
    )
    (net (code "448") (name "Net-(J_R7-Pad1)") (class "Default")
      (node (ref "J_R7") (pin "1") (pinfunction "1_1") (pintype "passive"))
      (node (ref "Rr7") (pin "1") (pinfunction "1_1") (pintype "passive"))
    )
    (net (code "449") (name "Net-(J_R8-Pad1)") (class "Default")
      (node (ref "J_R8") (pin "1") (pinfunction "1_1") (pintype "passive"))
      (node (ref "Rr8") (pin "1") (pinfunction "1_1") (pintype "passive"))
    )
    (net (code "450") (name "Net-(U0-EN)") (class "Default")
      (node (ref "J_GMR_EN") (pin "2") (pinfunction "2_2") (pintype "passive"))
      (node (ref "U0") (pin "18") (pinfunction "EN_18") (pintype "input"))
    )
    (net (code "451") (name "Net-(VDDD-X)") (class "Default")
      (node (ref "Cd01") (pin "1") (pinfunction "1_1") (pintype "passive"))
      (node (ref "Cd03") (pin "2") (pinfunction "2_2") (pintype "passive"))
      (node (ref "J_VDDD") (pin "1") (pinfunction "1_1") (pintype "passive"))
      (node (ref "VDDD") (pin "1") (pinfunction "X_1") (pintype "passive"))
    )
    (net (code "452") (name "Net-(V_demod-X)") (class "Default")
      (node (ref "J_demod") (pin "3") (pinfunction "3_3") (pintype "passive"))
      (node (ref "V_demod") (pin "1") (pinfunction "X_1") (pintype "passive"))
    )
    (net (code "453") (name "Net-(Vbias-X)") (class "Default")
      (node (ref "J_Vbias") (pin "2") (pinfunction "2_2") (pintype "passive"))
      (node (ref "Vbias") (pin "1") (pinfunction "X_1") (pintype "passive"))
    )
    (net (code "454") (name "VDD5v") (class "Default")
      (node (ref "AI_Mux1") (pin "14") (pinfunction "VDD_14") (pintype "passive"))
      (node (ref "AI_Mux2") (pin "14") (pinfunction "VDD_14") (pintype "passive"))
      (node (ref "AI_Mux3") (pin "14") (pinfunction "VDD_14") (pintype "passive"))
      (node (ref "AI_Mux4") (pin "14") (pinfunction "VDD_14") (pintype "passive"))
      (node (ref "AI_Mux5") (pin "14") (pinfunction "VDD_14") (pintype "passive"))
      (node (ref "AI_Mux6") (pin "14") (pinfunction "VDD_14") (pintype "passive"))
      (node (ref "AI_Mux7") (pin "14") (pinfunction "VDD_14") (pintype "passive"))
      (node (ref "Cd51") (pin "1") (pinfunction "1_1") (pintype "passive"))
      (node (ref "Cd52") (pin "1") (pinfunction "1_1") (pintype "passive"))
      (node (ref "Cd53") (pin "1") (pinfunction "1_1") (pintype "passive"))
      (node (ref "Cd54") (pin "1") (pinfunction "1_1") (pintype "passive"))
      (node (ref "Cd55") (pin "1") (pinfunction "1_1") (pintype "passive"))
      (node (ref "Cd56") (pin "1") (pinfunction "1_1") (pintype "passive"))
      (node (ref "Cd57") (pin "1") (pinfunction "1_1") (pintype "passive"))
      (node (ref "Cd58") (pin "1") (pinfunction "1_1") (pintype "passive"))
      (node (ref "Cd59") (pin "1") (pinfunction "1_1") (pintype "passive"))
      (node (ref "Cd60") (pin "1") (pinfunction "1_1") (pintype "passive"))
      (node (ref "Cd61") (pin "1") (pinfunction "1_1") (pintype "passive"))
      (node (ref "Cd62") (pin "1") (pinfunction "1_1") (pintype "passive"))
      (node (ref "Cd63") (pin "1") (pinfunction "1_1") (pintype "passive"))
      (node (ref "Cd64") (pin "1") (pinfunction "1_1") (pintype "passive"))
      (node (ref "Cd65") (pin "1") (pinfunction "1_1") (pintype "passive"))
      (node (ref "Cd66") (pin "1") (pinfunction "1_1") (pintype "passive"))
      (node (ref "J_GMR_EN") (pin "3") (pinfunction "3_3") (pintype "passive"))
      (node (ref "J_VDDD") (pin "3") (pinfunction "3_3") (pintype "passive"))
      (node (ref "U0") (pin "1") (pinfunction "VDD_1") (pintype "power_in"))
    )
    (net (code "455") (name "unconnected-(BKconnector-+1.2VDD-Pad84)") (class "Default")
      (node (ref "BKconnector") (pin "84") (pinfunction "+1.2VDD_84") (pintype "passive"))
    )
    (net (code "456") (name "unconnected-(BKconnector-+1.2VDD-Pad86)") (class "Default")
      (node (ref "BKconnector") (pin "86") (pinfunction "+1.2VDD_86") (pintype "passive"))
    )
    (net (code "457") (name "unconnected-(BKconnector-+3.3VDD-Pad2)") (class "Default")
      (node (ref "BKconnector") (pin "2") (pinfunction "+3.3VDD_2") (pintype "passive"))
    )
    (net (code "458") (name "unconnected-(BKconnector-+3.3VDD-Pad4)") (class "Default")
      (node (ref "BKconnector") (pin "4") (pinfunction "+3.3VDD_4") (pintype "passive"))
    )
    (net (code "459") (name "unconnected-(BKconnector-+3.3VDD-Pad6)") (class "Default")
      (node (ref "BKconnector") (pin "6") (pinfunction "+3.3VDD_6") (pintype "passive"))
    )
    (net (code "460") (name "unconnected-(BKconnector-+3.3VDD-Pad89)") (class "Default")
      (node (ref "BKconnector") (pin "89") (pinfunction "+3.3VDD_89") (pintype "passive"))
    )
    (net (code "461") (name "unconnected-(BKconnector-+3.3VDD-Pad91)") (class "Default")
      (node (ref "BKconnector") (pin "91") (pinfunction "+3.3VDD_91") (pintype "passive"))
    )
    (net (code "462") (name "unconnected-(BKconnector-+3.3VDD-Pad93)") (class "Default")
      (node (ref "BKconnector") (pin "93") (pinfunction "+3.3VDD_93") (pintype "passive"))
    )
    (net (code "463") (name "unconnected-(BKconnector-+VDC-Pad81)") (class "Default")
      (node (ref "BKconnector") (pin "81") (pinfunction "+VDC_81") (pintype "passive"))
    )
    (net (code "464") (name "unconnected-(BKconnector-+VDC-Pad83)") (class "Default")
      (node (ref "BKconnector") (pin "83") (pinfunction "+VDC_83") (pintype "passive"))
    )
    (net (code "465") (name "unconnected-(BKconnector-+VDC-Pad85)") (class "Default")
      (node (ref "BKconnector") (pin "85") (pinfunction "+VDC_85") (pintype "passive"))
    )
    (net (code "466") (name "unconnected-(BKconnector---Pad3)") (class "Default")
      (node (ref "BKconnector") (pin "3") (pinfunction "-_3") (pintype "passive"))
    )
    (net (code "467") (name "unconnected-(BKconnector---Pad12)") (class "Default")
      (node (ref "BKconnector") (pin "12") (pinfunction "-_12") (pintype "passive"))
    )
    (net (code "468") (name "unconnected-(BKconnector-A20-Pad76)") (class "Default")
      (node (ref "BKconnector") (pin "76") (pinfunction "A20_76") (pintype "passive"))
    )
    (net (code "469") (name "unconnected-(BKconnector-J17-Pad27)") (class "Default")
      (node (ref "BKconnector") (pin "27") (pinfunction "J17_27") (pintype "passive"))
    )
    (net (code "470") (name "unconnected-(BKconnector-J20-Pad77)") (class "Default")
      (node (ref "BKconnector") (pin "77") (pinfunction "J20_77") (pintype "passive"))
    )
    (net (code "471") (name "unconnected-(BKconnector-J22-Pad79)") (class "Default")
      (node (ref "BKconnector") (pin "79") (pinfunction "J22_79") (pintype "passive"))
    )
    (net (code "472") (name "unconnected-(BKconnector-JTAG_TCK-Pad5)") (class "Default")
      (node (ref "BKconnector") (pin "5") (pinfunction "JTAG_TCK_5") (pintype "passive"))
    )
    (net (code "473") (name "unconnected-(BKconnector-JTAG_TDI-Pad9)") (class "Default")
      (node (ref "BKconnector") (pin "9") (pinfunction "JTAG_TDI_9") (pintype "passive"))
    )
    (net (code "474") (name "unconnected-(BKconnector-JTAG_TDO-Pad8)") (class "Default")
      (node (ref "BKconnector") (pin "8") (pinfunction "JTAG_TDO_8") (pintype "passive"))
    )
    (net (code "475") (name "unconnected-(BKconnector-JTAG_TMS-Pad7)") (class "Default")
      (node (ref "BKconnector") (pin "7") (pinfunction "JTAG_TMS_7") (pintype "passive"))
    )
    (net (code "476") (name "unconnected-(BKconnector-K19-Pad40)") (class "Default")
      (node (ref "BKconnector") (pin "40") (pinfunction "K19_40") (pintype "passive"))
    )
    (net (code "477") (name "unconnected-(BKconnector-K20-Pad38)") (class "Default")
      (node (ref "BKconnector") (pin "38") (pinfunction "K20_38") (pintype "passive"))
    )
    (net (code "478") (name "unconnected-(BKconnector-L15-Pad34)") (class "Default")
      (node (ref "BKconnector") (pin "34") (pinfunction "L15_34") (pintype "passive"))
    )
    (net (code "479") (name "unconnected-(BKconnector-L19-Pad58)") (class "Default")
      (node (ref "BKconnector") (pin "58") (pinfunction "L19_58") (pintype "passive"))
    )
    (net (code "480") (name "unconnected-(BKconnector-N22-Pad52)") (class "Default")
      (node (ref "BKconnector") (pin "52") (pinfunction "N22_52") (pintype "passive"))
    )
    (net (code "481") (name "unconnected-(BKconnector-P21-Pad45)") (class "Default")
      (node (ref "BKconnector") (pin "45") (pinfunction "P21_45") (pintype "passive"))
    )
    (net (code "482") (name "unconnected-(BKconnector-P22-Pad47)") (class "Default")
      (node (ref "BKconnector") (pin "47") (pinfunction "P22_47") (pintype "passive"))
    )
    (net (code "483") (name "unconnected-(BKconnector-SYS_CLK4-Pad11)") (class "Default")
      (node (ref "BKconnector") (pin "11") (pinfunction "SYS_CLK4_11") (pintype "passive"))
    )
    (net (code "484") (name "unconnected-(BKconnector-SYS_CLK5-Pad88)") (class "Default")
      (node (ref "BKconnector") (pin "88") (pinfunction "SYS_CLK5_88") (pintype "passive"))
    )
    (net (code "485") (name "unconnected-(BKconnector-USB_SCL-Pad90)") (class "Default")
      (node (ref "BKconnector") (pin "90") (pinfunction "USB_SCL_90") (pintype "passive"))
    )
    (net (code "486") (name "unconnected-(BKconnector-USB_SDA-Pad92)") (class "Default")
      (node (ref "BKconnector") (pin "92") (pinfunction "USB_SDA_92") (pintype "passive"))
    )
    (net (code "487") (name "unconnected-(BKconnector-V22-Pad39)") (class "Default")
      (node (ref "BKconnector") (pin "39") (pinfunction "V22_39") (pintype "passive"))
    )
    (net (code "488") (name "unconnected-(BKconnector-VREF_1-Pad10)") (class "Default")
      (node (ref "BKconnector") (pin "10") (pinfunction "VREF_1_10") (pintype "passive"))
    )
    (net (code "489") (name "unconnected-(J1-MH1-Pad69)") (class "Default")
      (node (ref "J1") (pin "69") (pinfunction "MH1_69") (pintype "passive"))
    )
    (net (code "490") (name "unconnected-(J1-MH2-Pad70)") (class "Default")
      (node (ref "J1") (pin "70") (pinfunction "MH2_70") (pintype "passive"))
    )
    (net (code "491") (name "unconnected-(J1-Pad1)") (class "Default")
      (node (ref "J1") (pin "1") (pinfunction "1_1") (pintype "passive"))
    )
    (net (code "492") (name "unconnected-(J1-Pad2)") (class "Default")
      (node (ref "J1") (pin "2") (pinfunction "2_2") (pintype "passive"))
    )
    (net (code "493") (name "unconnected-(J1-Pad3)") (class "Default")
      (node (ref "J1") (pin "3") (pinfunction "3_3") (pintype "passive"))
    )
    (net (code "494") (name "unconnected-(J1-Pad5)") (class "Default")
      (node (ref "J1") (pin "5") (pinfunction "5_5") (pintype "passive"))
    )
    (net (code "495") (name "unconnected-(J1-Pad6)") (class "Default")
      (node (ref "J1") (pin "6") (pinfunction "6_6") (pintype "passive"))
    )
    (net (code "496") (name "unconnected-(J1-Pad8)") (class "Default")
      (node (ref "J1") (pin "8") (pinfunction "8_8") (pintype "passive"))
    )
    (net (code "497") (name "unconnected-(J1-Pad10)") (class "Default")
      (node (ref "J1") (pin "10") (pinfunction "10_10") (pintype "passive"))
    )
    (net (code "498") (name "unconnected-(J1-Pad11)") (class "Default")
      (node (ref "J1") (pin "11") (pinfunction "11_11") (pintype "passive"))
    )
    (net (code "499") (name "unconnected-(J1-Pad14)") (class "Default")
      (node (ref "J1") (pin "14") (pinfunction "14_14") (pintype "passive"))
    )
    (net (code "500") (name "unconnected-(J1-Pad16)") (class "Default")
      (node (ref "J1") (pin "16") (pinfunction "16_16") (pintype "passive"))
    )
    (net (code "501") (name "unconnected-(J1-Pad19)") (class "Default")
      (node (ref "J1") (pin "19") (pinfunction "19_19") (pintype "passive"))
    )
    (net (code "502") (name "unconnected-(J1-Pad20)") (class "Default")
      (node (ref "J1") (pin "20") (pinfunction "20_20") (pintype "passive"))
    )
    (net (code "503") (name "unconnected-(J1-Pad37)") (class "Default")
      (node (ref "J1") (pin "37") (pinfunction "37_37") (pintype "passive"))
    )
    (net (code "504") (name "unconnected-(J1-Pad38)") (class "Default")
      (node (ref "J1") (pin "38") (pinfunction "38_38") (pintype "passive"))
    )
    (net (code "505") (name "unconnected-(J1-Pad39)") (class "Default")
      (node (ref "J1") (pin "39") (pinfunction "39_39") (pintype "passive"))
    )
    (net (code "506") (name "unconnected-(J1-Pad40)") (class "Default")
      (node (ref "J1") (pin "40") (pinfunction "40_40") (pintype "passive"))
    )
    (net (code "507") (name "unconnected-(J1-Pad41)") (class "Default")
      (node (ref "J1") (pin "41") (pinfunction "41_41") (pintype "passive"))
    )
    (net (code "508") (name "unconnected-(J1-Pad42)") (class "Default")
      (node (ref "J1") (pin "42") (pinfunction "42_42") (pintype "passive"))
    )
    (net (code "509") (name "unconnected-(J1-Pad43)") (class "Default")
      (node (ref "J1") (pin "43") (pinfunction "43_43") (pintype "passive"))
    )
    (net (code "510") (name "unconnected-(J1-Pad45)") (class "Default")
      (node (ref "J1") (pin "45") (pinfunction "45_45") (pintype "passive"))
    )
    (net (code "511") (name "unconnected-(J1-Pad46)") (class "Default")
      (node (ref "J1") (pin "46") (pinfunction "46_46") (pintype "passive"))
    )
    (net (code "512") (name "unconnected-(J1-Pad47)") (class "Default")
      (node (ref "J1") (pin "47") (pinfunction "47_47") (pintype "passive"))
    )
    (net (code "513") (name "unconnected-(J1-Pad48)") (class "Default")
      (node (ref "J1") (pin "48") (pinfunction "48_48") (pintype "passive"))
    )
    (net (code "514") (name "unconnected-(J1-Pad51)") (class "Default")
      (node (ref "J1") (pin "51") (pinfunction "51_51") (pintype "passive"))
    )
    (net (code "515") (name "unconnected-(P20-Pad3)") (class "Default")
      (node (ref "P20") (pin "3") (pinfunction "3_3") (pintype "passive"))
    )
    (net (code "516") (name "unconnected-(P20-Pad4)") (class "Default")
      (node (ref "P20") (pin "4") (pinfunction "4_4") (pintype "passive"))
    )
    (net (code "517") (name "unconnected-(U0-NC-Pad2)") (class "Default")
      (node (ref "U0") (pin "2") (pinfunction "NC_2") (pintype "passive"))
    )
    (net (code "518") (name "unconnected-(U0-NC-Pad3)") (class "Default")
      (node (ref "U0") (pin "3") (pinfunction "NC_3") (pintype "passive"))
    )
    (net (code "519") (name "unconnected-(U0-NC-Pad13)") (class "Default")
      (node (ref "U0") (pin "13") (pinfunction "NC_13") (pintype "passive"))
    )
    (net (code "520") (name "unconnected-(U0-S11-Pad9)") (class "Default")
      (node (ref "U0") (pin "9") (pinfunction "S11_9") (pintype "passive"))
    )
    (net (code "521") (name "unconnected-(U0-S12-Pad8)") (class "Default")
      (node (ref "U0") (pin "8") (pinfunction "S12_8") (pintype "passive"))
    )
    (net (code "522") (name "unconnected-(U0-S13-Pad7)") (class "Default")
      (node (ref "U0") (pin "7") (pinfunction "S13_7") (pintype "passive"))
    )
    (net (code "523") (name "unconnected-(U0-S14-Pad6)") (class "Default")
      (node (ref "U0") (pin "6") (pinfunction "S14_6") (pintype "passive"))
    )
    (net (code "524") (name "unconnected-(U0-S15-Pad5)") (class "Default")
      (node (ref "U0") (pin "5") (pinfunction "S15_5") (pintype "passive"))
    )
    (net (code "525") (name "unconnected-(U0-S16-Pad4)") (class "Default")
      (node (ref "U0") (pin "4") (pinfunction "S16_4") (pintype "passive"))
    )
  )
)
